# LEDSubMatrixHighDensity.net
KiCad netlist of a schematic drawn in EAGLE
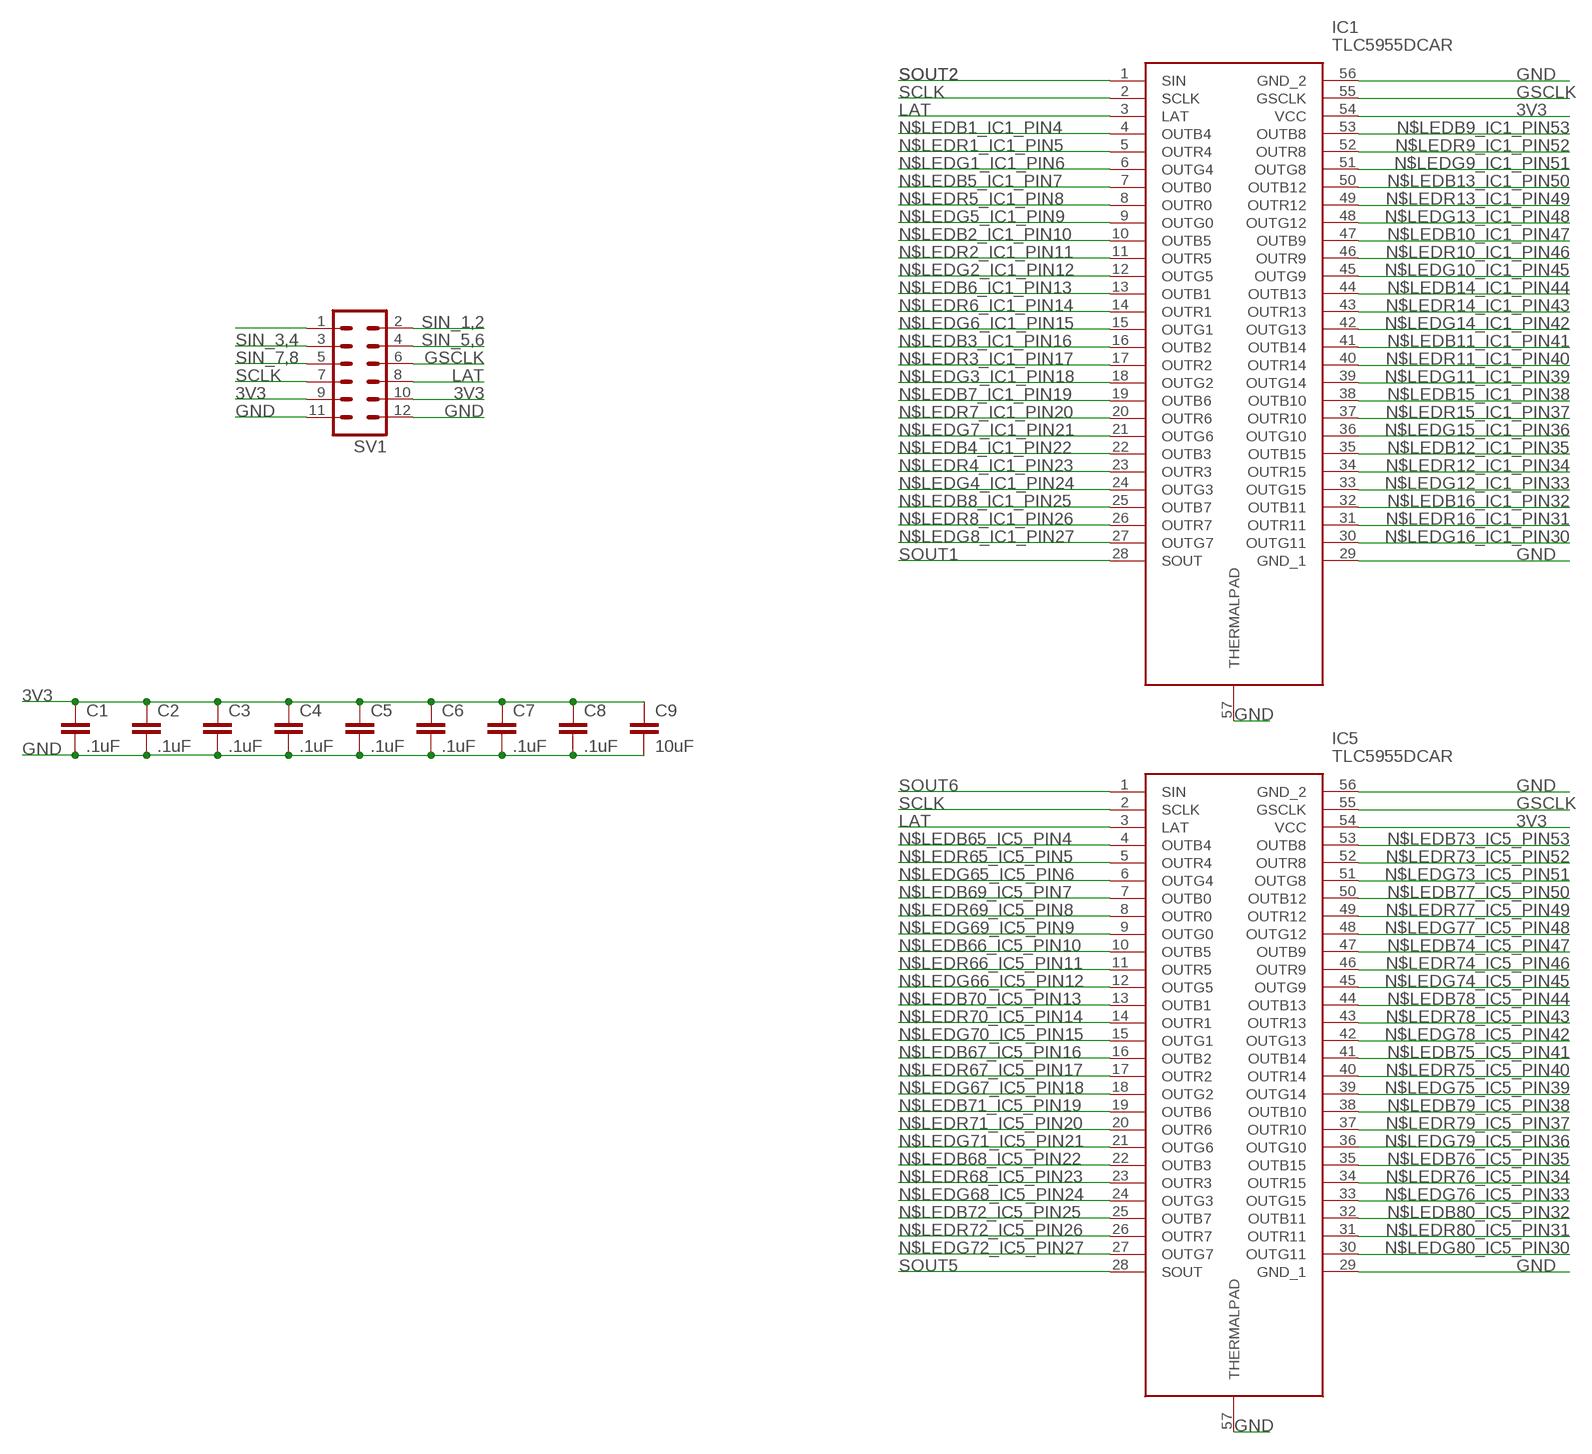
[diagram p0: schematic, sheet 1, part 1 of 3]
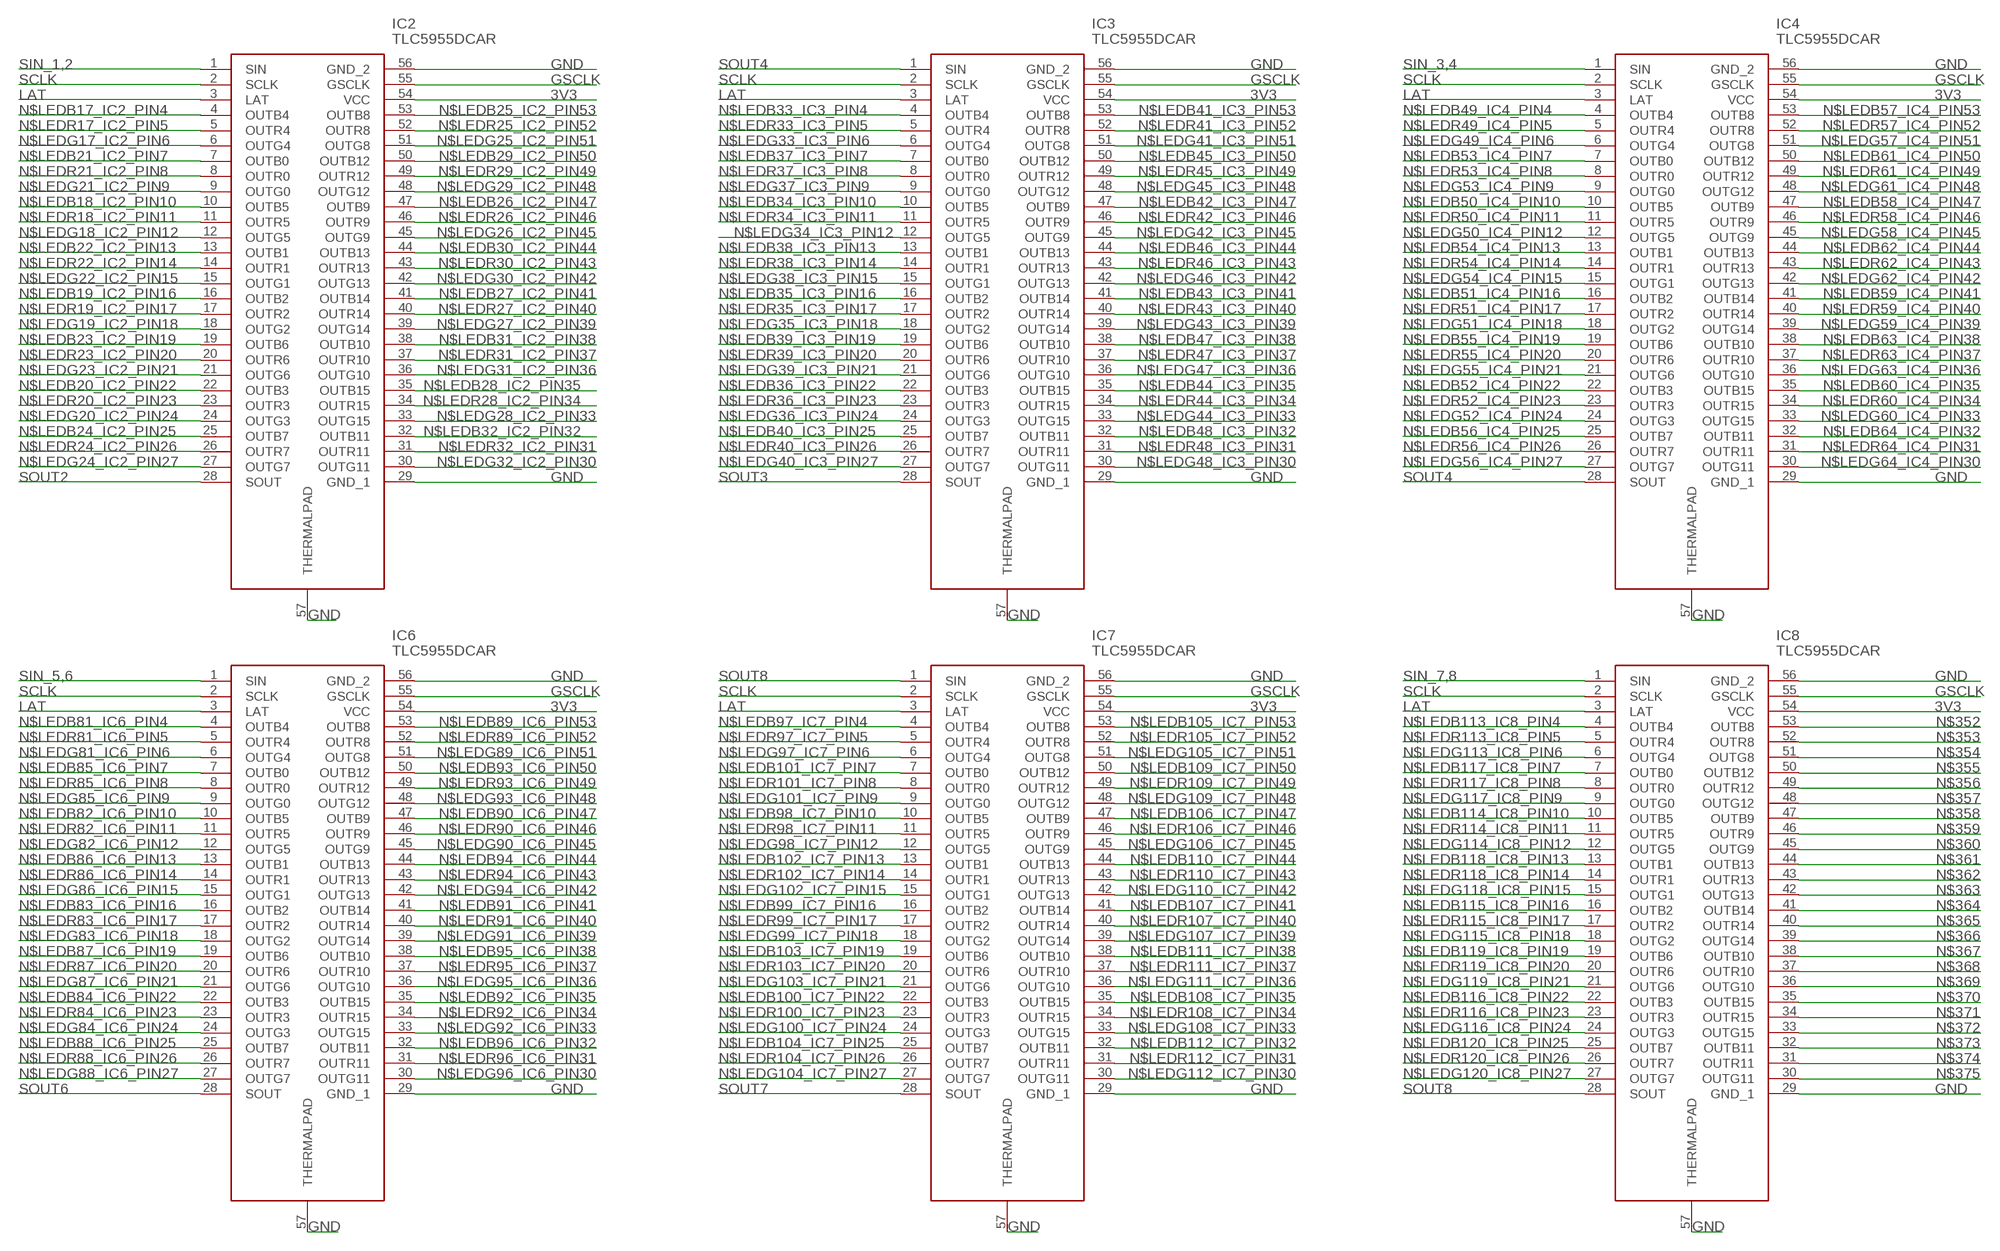
[diagram p1: schematic, sheet 1, part 2 of 3]
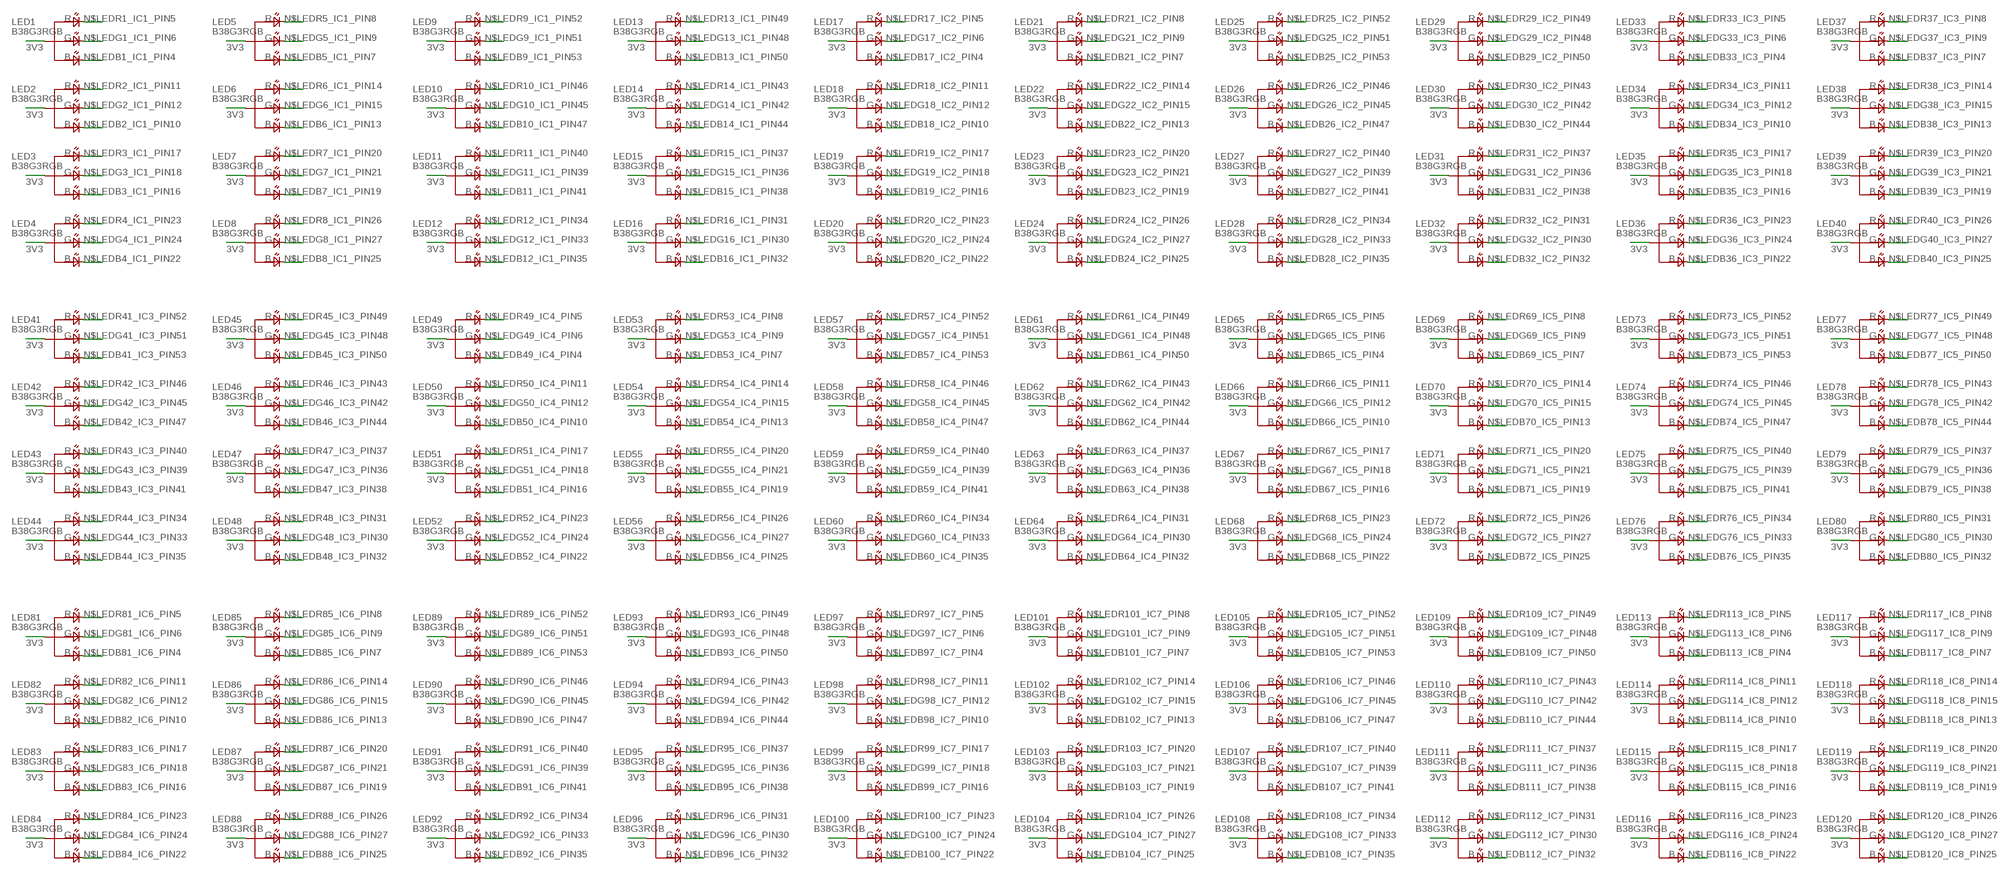
[diagram p2: schematic, sheet 1, part 3 of 3]

(export (version "E")
  (design (tool "Eeschema 10.0.6"))
  (components
    (comp (ref "C1")
      (value ".1uF")
      (footprint "eagle-import:C0603")
      (libsource (lib "eagle-import") (part "C-EUC0603"))
    )
    (comp (ref "C2")
      (value ".1uF")
      (footprint "eagle-import:C0603")
      (libsource (lib "eagle-import") (part "C-EUC0603"))
    )
    (comp (ref "C3")
      (value ".1uF")
      (footprint "eagle-import:C0603")
      (libsource (lib "eagle-import") (part "C-EUC0603"))
    )
    (comp (ref "C4")
      (value ".1uF")
      (footprint "eagle-import:C0603")
      (libsource (lib "eagle-import") (part "C-EUC0603"))
    )
    (comp (ref "C5")
      (value ".1uF")
      (footprint "eagle-import:C0603")
      (libsource (lib "eagle-import") (part "C-EUC0603"))
    )
    (comp (ref "C6")
      (value ".1uF")
      (footprint "eagle-import:C0603")
      (libsource (lib "eagle-import") (part "C-EUC0603"))
    )
    (comp (ref "C7")
      (value ".1uF")
      (footprint "eagle-import:C0603")
      (libsource (lib "eagle-import") (part "C-EUC0603"))
    )
    (comp (ref "C8")
      (value ".1uF")
      (footprint "eagle-import:C0603")
      (libsource (lib "eagle-import") (part "C-EUC0603"))
    )
    (comp (ref "C9")
      (value "10uF")
      (footprint "eagle-import:C0805")
      (libsource (lib "eagle-import") (part "C-EUC0805"))
    )
    (comp (ref "IC1")
      (value "TLC5955DCAR")
      (footprint "eagle-import:SOP50P810X120-57N")
      (fields (field (name "MOUSER_PART_NUMBER") "595-TLC5955DCAR"))
      (libsource (lib "eagle-import") (part "TLC5955DCAR"))
    )
    (comp (ref "IC2")
      (value "TLC5955DCAR")
      (footprint "eagle-import:SOP50P810X120-57N")
      (fields (field (name "MOUSER_PART_NUMBER") "595-TLC5955DCAR"))
      (libsource (lib "eagle-import") (part "TLC5955DCAR"))
    )
    (comp (ref "IC3")
      (value "TLC5955DCAR")
      (footprint "eagle-import:SOP50P810X120-57N")
      (fields (field (name "MOUSER_PART_NUMBER") "595-TLC5955DCAR"))
      (libsource (lib "eagle-import") (part "TLC5955DCAR"))
    )
    (comp (ref "IC4")
      (value "TLC5955DCAR")
      (footprint "eagle-import:SOP50P810X120-57N")
      (fields (field (name "MOUSER_PART_NUMBER") "595-TLC5955DCAR"))
      (libsource (lib "eagle-import") (part "TLC5955DCAR"))
    )
    (comp (ref "IC5")
      (value "TLC5955DCAR")
      (footprint "eagle-import:SOP50P810X120-57N")
      (fields (field (name "MOUSER_PART_NUMBER") "595-TLC5955DCAR"))
      (libsource (lib "eagle-import") (part "TLC5955DCAR"))
    )
    (comp (ref "IC6")
      (value "TLC5955DCAR")
      (footprint "eagle-import:SOP50P810X120-57N")
      (fields (field (name "MOUSER_PART_NUMBER") "595-TLC5955DCAR"))
      (libsource (lib "eagle-import") (part "TLC5955DCAR"))
    )
    (comp (ref "IC7")
      (value "TLC5955DCAR")
      (footprint "eagle-import:SOP50P810X120-57N")
      (fields (field (name "MOUSER_PART_NUMBER") "595-TLC5955DCAR"))
      (libsource (lib "eagle-import") (part "TLC5955DCAR"))
    )
    (comp (ref "IC8")
      (value "TLC5955DCAR")
      (footprint "eagle-import:SOP50P810X120-57N")
      (fields (field (name "MOUSER_PART_NUMBER") "595-TLC5955DCAR"))
      (libsource (lib "eagle-import") (part "TLC5955DCAR"))
    )
    (comp (ref "LED1")
      (value "B38G3RGB")
      (footprint "eagle-import:B38G3RGB")
      (fields
        (field (name "ARROW_PART_NUMBER") "SML-LX0606IGC-TR")
        (field (name "MOUSER_PART_NUMBER") "696-SML-0606IGCTR")
      )
      (libsource (lib "eagle-import") (part "B38G3RGB"))
    )
    (comp (ref "LED2")
      (value "B38G3RGB")
      (footprint "eagle-import:B38G3RGB")
      (fields
        (field (name "ARROW_PART_NUMBER") "SML-LX0606IGC-TR")
        (field (name "MOUSER_PART_NUMBER") "696-SML-0606IGCTR")
      )
      (libsource (lib "eagle-import") (part "B38G3RGB"))
    )
    (comp (ref "LED3")
      (value "B38G3RGB")
      (footprint "eagle-import:B38G3RGB")
      (fields
        (field (name "ARROW_PART_NUMBER") "SML-LX0606IGC-TR")
        (field (name "MOUSER_PART_NUMBER") "696-SML-0606IGCTR")
      )
      (libsource (lib "eagle-import") (part "B38G3RGB"))
    )
    (comp (ref "LED4")
      (value "B38G3RGB")
      (footprint "eagle-import:B38G3RGB")
      (fields
        (field (name "ARROW_PART_NUMBER") "SML-LX0606IGC-TR")
        (field (name "MOUSER_PART_NUMBER") "696-SML-0606IGCTR")
      )
      (libsource (lib "eagle-import") (part "B38G3RGB"))
    )
    (comp (ref "LED5")
      (value "B38G3RGB")
      (footprint "eagle-import:B38G3RGB")
      (fields
        (field (name "ARROW_PART_NUMBER") "SML-LX0606IGC-TR")
        (field (name "MOUSER_PART_NUMBER") "696-SML-0606IGCTR")
      )
      (libsource (lib "eagle-import") (part "B38G3RGB"))
    )
    (comp (ref "LED6")
      (value "B38G3RGB")
      (footprint "eagle-import:B38G3RGB")
      (fields
        (field (name "ARROW_PART_NUMBER") "SML-LX0606IGC-TR")
        (field (name "MOUSER_PART_NUMBER") "696-SML-0606IGCTR")
      )
      (libsource (lib "eagle-import") (part "B38G3RGB"))
    )
    (comp (ref "LED7")
      (value "B38G3RGB")
      (footprint "eagle-import:B38G3RGB")
      (fields
        (field (name "ARROW_PART_NUMBER") "SML-LX0606IGC-TR")
        (field (name "MOUSER_PART_NUMBER") "696-SML-0606IGCTR")
      )
      (libsource (lib "eagle-import") (part "B38G3RGB"))
    )
    (comp (ref "LED8")
      (value "B38G3RGB")
      (footprint "eagle-import:B38G3RGB")
      (fields
        (field (name "ARROW_PART_NUMBER") "SML-LX0606IGC-TR")
        (field (name "MOUSER_PART_NUMBER") "696-SML-0606IGCTR")
      )
      (libsource (lib "eagle-import") (part "B38G3RGB"))
    )
    (comp (ref "LED9")
      (value "B38G3RGB")
      (footprint "eagle-import:B38G3RGB")
      (fields
        (field (name "ARROW_PART_NUMBER") "SML-LX0606IGC-TR")
        (field (name "MOUSER_PART_NUMBER") "696-SML-0606IGCTR")
      )
      (libsource (lib "eagle-import") (part "B38G3RGB"))
    )
    (comp (ref "LED10")
      (value "B38G3RGB")
      (footprint "eagle-import:B38G3RGB")
      (fields
        (field (name "ARROW_PART_NUMBER") "SML-LX0606IGC-TR")
        (field (name "MOUSER_PART_NUMBER") "696-SML-0606IGCTR")
      )
      (libsource (lib "eagle-import") (part "B38G3RGB"))
    )
    (comp (ref "LED11")
      (value "B38G3RGB")
      (footprint "eagle-import:B38G3RGB")
      (fields
        (field (name "ARROW_PART_NUMBER") "SML-LX0606IGC-TR")
        (field (name "MOUSER_PART_NUMBER") "696-SML-0606IGCTR")
      )
      (libsource (lib "eagle-import") (part "B38G3RGB"))
    )
    (comp (ref "LED12")
      (value "B38G3RGB")
      (footprint "eagle-import:B38G3RGB")
      (fields
        (field (name "ARROW_PART_NUMBER") "SML-LX0606IGC-TR")
        (field (name "MOUSER_PART_NUMBER") "696-SML-0606IGCTR")
      )
      (libsource (lib "eagle-import") (part "B38G3RGB"))
    )
    (comp (ref "LED13")
      (value "B38G3RGB")
      (footprint "eagle-import:B38G3RGB")
      (fields
        (field (name "ARROW_PART_NUMBER") "SML-LX0606IGC-TR")
        (field (name "MOUSER_PART_NUMBER") "696-SML-0606IGCTR")
      )
      (libsource (lib "eagle-import") (part "B38G3RGB"))
    )
    (comp (ref "LED14")
      (value "B38G3RGB")
      (footprint "eagle-import:B38G3RGB")
      (fields
        (field (name "ARROW_PART_NUMBER") "SML-LX0606IGC-TR")
        (field (name "MOUSER_PART_NUMBER") "696-SML-0606IGCTR")
      )
      (libsource (lib "eagle-import") (part "B38G3RGB"))
    )
    (comp (ref "LED15")
      (value "B38G3RGB")
      (footprint "eagle-import:B38G3RGB")
      (fields
        (field (name "ARROW_PART_NUMBER") "SML-LX0606IGC-TR")
        (field (name "MOUSER_PART_NUMBER") "696-SML-0606IGCTR")
      )
      (libsource (lib "eagle-import") (part "B38G3RGB"))
    )
    (comp (ref "LED16")
      (value "B38G3RGB")
      (footprint "eagle-import:B38G3RGB")
      (fields
        (field (name "ARROW_PART_NUMBER") "SML-LX0606IGC-TR")
        (field (name "MOUSER_PART_NUMBER") "696-SML-0606IGCTR")
      )
      (libsource (lib "eagle-import") (part "B38G3RGB"))
    )
    (comp (ref "LED17")
      (value "B38G3RGB")
      (footprint "eagle-import:B38G3RGB")
      (fields
        (field (name "ARROW_PART_NUMBER") "SML-LX0606IGC-TR")
        (field (name "MOUSER_PART_NUMBER") "696-SML-0606IGCTR")
      )
      (libsource (lib "eagle-import") (part "B38G3RGB"))
    )
    (comp (ref "LED18")
      (value "B38G3RGB")
      (footprint "eagle-import:B38G3RGB")
      (fields
        (field (name "ARROW_PART_NUMBER") "SML-LX0606IGC-TR")
        (field (name "MOUSER_PART_NUMBER") "696-SML-0606IGCTR")
      )
      (libsource (lib "eagle-import") (part "B38G3RGB"))
    )
    (comp (ref "LED19")
      (value "B38G3RGB")
      (footprint "eagle-import:B38G3RGB")
      (fields
        (field (name "ARROW_PART_NUMBER") "SML-LX0606IGC-TR")
        (field (name "MOUSER_PART_NUMBER") "696-SML-0606IGCTR")
      )
      (libsource (lib "eagle-import") (part "B38G3RGB"))
    )
    (comp (ref "LED20")
      (value "B38G3RGB")
      (footprint "eagle-import:B38G3RGB")
      (fields
        (field (name "ARROW_PART_NUMBER") "SML-LX0606IGC-TR")
        (field (name "MOUSER_PART_NUMBER") "696-SML-0606IGCTR")
      )
      (libsource (lib "eagle-import") (part "B38G3RGB"))
    )
    (comp (ref "LED21")
      (value "B38G3RGB")
      (footprint "eagle-import:B38G3RGB")
      (fields
        (field (name "ARROW_PART_NUMBER") "SML-LX0606IGC-TR")
        (field (name "MOUSER_PART_NUMBER") "696-SML-0606IGCTR")
      )
      (libsource (lib "eagle-import") (part "B38G3RGB"))
    )
    (comp (ref "LED22")
      (value "B38G3RGB")
      (footprint "eagle-import:B38G3RGB")
      (fields
        (field (name "ARROW_PART_NUMBER") "SML-LX0606IGC-TR")
        (field (name "MOUSER_PART_NUMBER") "696-SML-0606IGCTR")
      )
      (libsource (lib "eagle-import") (part "B38G3RGB"))
    )
    (comp (ref "LED23")
      (value "B38G3RGB")
      (footprint "eagle-import:B38G3RGB")
      (fields
        (field (name "ARROW_PART_NUMBER") "SML-LX0606IGC-TR")
        (field (name "MOUSER_PART_NUMBER") "696-SML-0606IGCTR")
      )
      (libsource (lib "eagle-import") (part "B38G3RGB"))
    )
    (comp (ref "LED24")
      (value "B38G3RGB")
      (footprint "eagle-import:B38G3RGB")
      (fields
        (field (name "ARROW_PART_NUMBER") "SML-LX0606IGC-TR")
        (field (name "MOUSER_PART_NUMBER") "696-SML-0606IGCTR")
      )
      (libsource (lib "eagle-import") (part "B38G3RGB"))
    )
    (comp (ref "LED25")
      (value "B38G3RGB")
      (footprint "eagle-import:B38G3RGB")
      (fields
        (field (name "ARROW_PART_NUMBER") "SML-LX0606IGC-TR")
        (field (name "MOUSER_PART_NUMBER") "696-SML-0606IGCTR")
      )
      (libsource (lib "eagle-import") (part "B38G3RGB"))
    )
    (comp (ref "LED26")
      (value "B38G3RGB")
      (footprint "eagle-import:B38G3RGB")
      (fields
        (field (name "ARROW_PART_NUMBER") "SML-LX0606IGC-TR")
        (field (name "MOUSER_PART_NUMBER") "696-SML-0606IGCTR")
      )
      (libsource (lib "eagle-import") (part "B38G3RGB"))
    )
    (comp (ref "LED27")
      (value "B38G3RGB")
      (footprint "eagle-import:B38G3RGB")
      (fields
        (field (name "ARROW_PART_NUMBER") "SML-LX0606IGC-TR")
        (field (name "MOUSER_PART_NUMBER") "696-SML-0606IGCTR")
      )
      (libsource (lib "eagle-import") (part "B38G3RGB"))
    )
    (comp (ref "LED28")
      (value "B38G3RGB")
      (footprint "eagle-import:B38G3RGB")
      (fields
        (field (name "ARROW_PART_NUMBER") "SML-LX0606IGC-TR")
        (field (name "MOUSER_PART_NUMBER") "696-SML-0606IGCTR")
      )
      (libsource (lib "eagle-import") (part "B38G3RGB"))
    )
    (comp (ref "LED29")
      (value "B38G3RGB")
      (footprint "eagle-import:B38G3RGB")
      (fields
        (field (name "ARROW_PART_NUMBER") "SML-LX0606IGC-TR")
        (field (name "MOUSER_PART_NUMBER") "696-SML-0606IGCTR")
      )
      (libsource (lib "eagle-import") (part "B38G3RGB"))
    )
    (comp (ref "LED30")
      (value "B38G3RGB")
      (footprint "eagle-import:B38G3RGB")
      (fields
        (field (name "ARROW_PART_NUMBER") "SML-LX0606IGC-TR")
        (field (name "MOUSER_PART_NUMBER") "696-SML-0606IGCTR")
      )
      (libsource (lib "eagle-import") (part "B38G3RGB"))
    )
    (comp (ref "LED31")
      (value "B38G3RGB")
      (footprint "eagle-import:B38G3RGB")
      (fields
        (field (name "ARROW_PART_NUMBER") "SML-LX0606IGC-TR")
        (field (name "MOUSER_PART_NUMBER") "696-SML-0606IGCTR")
      )
      (libsource (lib "eagle-import") (part "B38G3RGB"))
    )
    (comp (ref "LED32")
      (value "B38G3RGB")
      (footprint "eagle-import:B38G3RGB")
      (fields
        (field (name "ARROW_PART_NUMBER") "SML-LX0606IGC-TR")
        (field (name "MOUSER_PART_NUMBER") "696-SML-0606IGCTR")
      )
      (libsource (lib "eagle-import") (part "B38G3RGB"))
    )
    (comp (ref "LED33")
      (value "B38G3RGB")
      (footprint "eagle-import:B38G3RGB")
      (fields
        (field (name "ARROW_PART_NUMBER") "SML-LX0606IGC-TR")
        (field (name "MOUSER_PART_NUMBER") "696-SML-0606IGCTR")
      )
      (libsource (lib "eagle-import") (part "B38G3RGB"))
    )
    (comp (ref "LED34")
      (value "B38G3RGB")
      (footprint "eagle-import:B38G3RGB")
      (fields
        (field (name "ARROW_PART_NUMBER") "SML-LX0606IGC-TR")
        (field (name "MOUSER_PART_NUMBER") "696-SML-0606IGCTR")
      )
      (libsource (lib "eagle-import") (part "B38G3RGB"))
    )
    (comp (ref "LED35")
      (value "B38G3RGB")
      (footprint "eagle-import:B38G3RGB")
      (fields
        (field (name "ARROW_PART_NUMBER") "SML-LX0606IGC-TR")
        (field (name "MOUSER_PART_NUMBER") "696-SML-0606IGCTR")
      )
      (libsource (lib "eagle-import") (part "B38G3RGB"))
    )
    (comp (ref "LED36")
      (value "B38G3RGB")
      (footprint "eagle-import:B38G3RGB")
      (fields
        (field (name "ARROW_PART_NUMBER") "SML-LX0606IGC-TR")
        (field (name "MOUSER_PART_NUMBER") "696-SML-0606IGCTR")
      )
      (libsource (lib "eagle-import") (part "B38G3RGB"))
    )
    (comp (ref "LED37")
      (value "B38G3RGB")
      (footprint "eagle-import:B38G3RGB")
      (fields
        (field (name "ARROW_PART_NUMBER") "SML-LX0606IGC-TR")
        (field (name "MOUSER_PART_NUMBER") "696-SML-0606IGCTR")
      )
      (libsource (lib "eagle-import") (part "B38G3RGB"))
    )
    (comp (ref "LED38")
      (value "B38G3RGB")
      (footprint "eagle-import:B38G3RGB")
      (fields
        (field (name "ARROW_PART_NUMBER") "SML-LX0606IGC-TR")
        (field (name "MOUSER_PART_NUMBER") "696-SML-0606IGCTR")
      )
      (libsource (lib "eagle-import") (part "B38G3RGB"))
    )
    (comp (ref "LED39")
      (value "B38G3RGB")
      (footprint "eagle-import:B38G3RGB")
      (fields
        (field (name "ARROW_PART_NUMBER") "SML-LX0606IGC-TR")
        (field (name "MOUSER_PART_NUMBER") "696-SML-0606IGCTR")
      )
      (libsource (lib "eagle-import") (part "B38G3RGB"))
    )
    (comp (ref "LED40")
      (value "B38G3RGB")
      (footprint "eagle-import:B38G3RGB")
      (fields
        (field (name "ARROW_PART_NUMBER") "SML-LX0606IGC-TR")
        (field (name "MOUSER_PART_NUMBER") "696-SML-0606IGCTR")
      )
      (libsource (lib "eagle-import") (part "B38G3RGB"))
    )
    (comp (ref "LED41")
      (value "B38G3RGB")
      (footprint "eagle-import:B38G3RGB")
      (fields
        (field (name "ARROW_PART_NUMBER") "SML-LX0606IGC-TR")
        (field (name "MOUSER_PART_NUMBER") "696-SML-0606IGCTR")
      )
      (libsource (lib "eagle-import") (part "B38G3RGB"))
    )
    (comp (ref "LED42")
      (value "B38G3RGB")
      (footprint "eagle-import:B38G3RGB")
      (fields
        (field (name "ARROW_PART_NUMBER") "SML-LX0606IGC-TR")
        (field (name "MOUSER_PART_NUMBER") "696-SML-0606IGCTR")
      )
      (libsource (lib "eagle-import") (part "B38G3RGB"))
    )
    (comp (ref "LED43")
      (value "B38G3RGB")
      (footprint "eagle-import:B38G3RGB")
      (fields
        (field (name "ARROW_PART_NUMBER") "SML-LX0606IGC-TR")
        (field (name "MOUSER_PART_NUMBER") "696-SML-0606IGCTR")
      )
      (libsource (lib "eagle-import") (part "B38G3RGB"))
    )
    (comp (ref "LED44")
      (value "B38G3RGB")
      (footprint "eagle-import:B38G3RGB")
      (fields
        (field (name "ARROW_PART_NUMBER") "SML-LX0606IGC-TR")
        (field (name "MOUSER_PART_NUMBER") "696-SML-0606IGCTR")
      )
      (libsource (lib "eagle-import") (part "B38G3RGB"))
    )
    (comp (ref "LED45")
      (value "B38G3RGB")
      (footprint "eagle-import:B38G3RGB")
      (fields
        (field (name "ARROW_PART_NUMBER") "SML-LX0606IGC-TR")
        (field (name "MOUSER_PART_NUMBER") "696-SML-0606IGCTR")
      )
      (libsource (lib "eagle-import") (part "B38G3RGB"))
    )
    (comp (ref "LED46")
      (value "B38G3RGB")
      (footprint "eagle-import:B38G3RGB")
      (fields
        (field (name "ARROW_PART_NUMBER") "SML-LX0606IGC-TR")
        (field (name "MOUSER_PART_NUMBER") "696-SML-0606IGCTR")
      )
      (libsource (lib "eagle-import") (part "B38G3RGB"))
    )
    (comp (ref "LED47")
      (value "B38G3RGB")
      (footprint "eagle-import:B38G3RGB")
      (fields
        (field (name "ARROW_PART_NUMBER") "SML-LX0606IGC-TR")
        (field (name "MOUSER_PART_NUMBER") "696-SML-0606IGCTR")
      )
      (libsource (lib "eagle-import") (part "B38G3RGB"))
    )
    (comp (ref "LED48")
      (value "B38G3RGB")
      (footprint "eagle-import:B38G3RGB")
      (fields
        (field (name "ARROW_PART_NUMBER") "SML-LX0606IGC-TR")
        (field (name "MOUSER_PART_NUMBER") "696-SML-0606IGCTR")
      )
      (libsource (lib "eagle-import") (part "B38G3RGB"))
    )
    (comp (ref "LED49")
      (value "B38G3RGB")
      (footprint "eagle-import:B38G3RGB")
      (fields
        (field (name "ARROW_PART_NUMBER") "SML-LX0606IGC-TR")
        (field (name "MOUSER_PART_NUMBER") "696-SML-0606IGCTR")
      )
      (libsource (lib "eagle-import") (part "B38G3RGB"))
    )
    (comp (ref "LED50")
      (value "B38G3RGB")
      (footprint "eagle-import:B38G3RGB")
      (fields
        (field (name "ARROW_PART_NUMBER") "SML-LX0606IGC-TR")
        (field (name "MOUSER_PART_NUMBER") "696-SML-0606IGCTR")
      )
      (libsource (lib "eagle-import") (part "B38G3RGB"))
    )
    (comp (ref "LED51")
      (value "B38G3RGB")
      (footprint "eagle-import:B38G3RGB")
      (fields
        (field (name "ARROW_PART_NUMBER") "SML-LX0606IGC-TR")
        (field (name "MOUSER_PART_NUMBER") "696-SML-0606IGCTR")
      )
      (libsource (lib "eagle-import") (part "B38G3RGB"))
    )
    (comp (ref "LED52")
      (value "B38G3RGB")
      (footprint "eagle-import:B38G3RGB")
      (fields
        (field (name "ARROW_PART_NUMBER") "SML-LX0606IGC-TR")
        (field (name "MOUSER_PART_NUMBER") "696-SML-0606IGCTR")
      )
      (libsource (lib "eagle-import") (part "B38G3RGB"))
    )
    (comp (ref "LED53")
      (value "B38G3RGB")
      (footprint "eagle-import:B38G3RGB")
      (fields
        (field (name "ARROW_PART_NUMBER") "SML-LX0606IGC-TR")
        (field (name "MOUSER_PART_NUMBER") "696-SML-0606IGCTR")
      )
      (libsource (lib "eagle-import") (part "B38G3RGB"))
    )
    (comp (ref "LED54")
      (value "B38G3RGB")
      (footprint "eagle-import:B38G3RGB")
      (fields
        (field (name "ARROW_PART_NUMBER") "SML-LX0606IGC-TR")
        (field (name "MOUSER_PART_NUMBER") "696-SML-0606IGCTR")
      )
      (libsource (lib "eagle-import") (part "B38G3RGB"))
    )
    (comp (ref "LED55")
      (value "B38G3RGB")
      (footprint "eagle-import:B38G3RGB")
      (fields
        (field (name "ARROW_PART_NUMBER") "SML-LX0606IGC-TR")
        (field (name "MOUSER_PART_NUMBER") "696-SML-0606IGCTR")
      )
      (libsource (lib "eagle-import") (part "B38G3RGB"))
    )
    (comp (ref "LED56")
      (value "B38G3RGB")
      (footprint "eagle-import:B38G3RGB")
      (fields
        (field (name "ARROW_PART_NUMBER") "SML-LX0606IGC-TR")
        (field (name "MOUSER_PART_NUMBER") "696-SML-0606IGCTR")
      )
      (libsource (lib "eagle-import") (part "B38G3RGB"))
    )
    (comp (ref "LED57")
      (value "B38G3RGB")
      (footprint "eagle-import:B38G3RGB")
      (fields
        (field (name "ARROW_PART_NUMBER") "SML-LX0606IGC-TR")
        (field (name "MOUSER_PART_NUMBER") "696-SML-0606IGCTR")
      )
      (libsource (lib "eagle-import") (part "B38G3RGB"))
    )
    (comp (ref "LED58")
      (value "B38G3RGB")
      (footprint "eagle-import:B38G3RGB")
      (fields
        (field (name "ARROW_PART_NUMBER") "SML-LX0606IGC-TR")
        (field (name "MOUSER_PART_NUMBER") "696-SML-0606IGCTR")
      )
      (libsource (lib "eagle-import") (part "B38G3RGB"))
    )
    (comp (ref "LED59")
      (value "B38G3RGB")
      (footprint "eagle-import:B38G3RGB")
      (fields
        (field (name "ARROW_PART_NUMBER") "SML-LX0606IGC-TR")
        (field (name "MOUSER_PART_NUMBER") "696-SML-0606IGCTR")
      )
      (libsource (lib "eagle-import") (part "B38G3RGB"))
    )
    (comp (ref "LED60")
      (value "B38G3RGB")
      (footprint "eagle-import:B38G3RGB")
      (fields
        (field (name "ARROW_PART_NUMBER") "SML-LX0606IGC-TR")
        (field (name "MOUSER_PART_NUMBER") "696-SML-0606IGCTR")
      )
      (libsource (lib "eagle-import") (part "B38G3RGB"))
    )
    (comp (ref "LED61")
      (value "B38G3RGB")
      (footprint "eagle-import:B38G3RGB")
      (fields
        (field (name "ARROW_PART_NUMBER") "SML-LX0606IGC-TR")
        (field (name "MOUSER_PART_NUMBER") "696-SML-0606IGCTR")
      )
      (libsource (lib "eagle-import") (part "B38G3RGB"))
    )
    (comp (ref "LED62")
      (value "B38G3RGB")
      (footprint "eagle-import:B38G3RGB")
      (fields
        (field (name "ARROW_PART_NUMBER") "SML-LX0606IGC-TR")
        (field (name "MOUSER_PART_NUMBER") "696-SML-0606IGCTR")
      )
      (libsource (lib "eagle-import") (part "B38G3RGB"))
    )
    (comp (ref "LED63")
      (value "B38G3RGB")
      (footprint "eagle-import:B38G3RGB")
      (fields
        (field (name "ARROW_PART_NUMBER") "SML-LX0606IGC-TR")
        (field (name "MOUSER_PART_NUMBER") "696-SML-0606IGCTR")
      )
      (libsource (lib "eagle-import") (part "B38G3RGB"))
    )
    (comp (ref "LED64")
      (value "B38G3RGB")
      (footprint "eagle-import:B38G3RGB")
      (fields
        (field (name "ARROW_PART_NUMBER") "SML-LX0606IGC-TR")
        (field (name "MOUSER_PART_NUMBER") "696-SML-0606IGCTR")
      )
      (libsource (lib "eagle-import") (part "B38G3RGB"))
    )
    (comp (ref "LED65")
      (value "B38G3RGB")
      (footprint "eagle-import:B38G3RGB")
      (fields
        (field (name "ARROW_PART_NUMBER") "SML-LX0606IGC-TR")
        (field (name "MOUSER_PART_NUMBER") "696-SML-0606IGCTR")
      )
      (libsource (lib "eagle-import") (part "B38G3RGB"))
    )
    (comp (ref "LED66")
      (value "B38G3RGB")
      (footprint "eagle-import:B38G3RGB")
      (fields
        (field (name "ARROW_PART_NUMBER") "SML-LX0606IGC-TR")
        (field (name "MOUSER_PART_NUMBER") "696-SML-0606IGCTR")
      )
      (libsource (lib "eagle-import") (part "B38G3RGB"))
    )
    (comp (ref "LED67")
      (value "B38G3RGB")
      (footprint "eagle-import:B38G3RGB")
      (fields
        (field (name "ARROW_PART_NUMBER") "SML-LX0606IGC-TR")
        (field (name "MOUSER_PART_NUMBER") "696-SML-0606IGCTR")
      )
      (libsource (lib "eagle-import") (part "B38G3RGB"))
    )
    (comp (ref "LED68")
      (value "B38G3RGB")
      (footprint "eagle-import:B38G3RGB")
      (fields
        (field (name "ARROW_PART_NUMBER") "SML-LX0606IGC-TR")
        (field (name "MOUSER_PART_NUMBER") "696-SML-0606IGCTR")
      )
      (libsource (lib "eagle-import") (part "B38G3RGB"))
    )
    (comp (ref "LED69")
      (value "B38G3RGB")
      (footprint "eagle-import:B38G3RGB")
      (fields
        (field (name "ARROW_PART_NUMBER") "SML-LX0606IGC-TR")
        (field (name "MOUSER_PART_NUMBER") "696-SML-0606IGCTR")
      )
      (libsource (lib "eagle-import") (part "B38G3RGB"))
    )
    (comp (ref "LED70")
      (value "B38G3RGB")
      (footprint "eagle-import:B38G3RGB")
      (fields
        (field (name "ARROW_PART_NUMBER") "SML-LX0606IGC-TR")
        (field (name "MOUSER_PART_NUMBER") "696-SML-0606IGCTR")
      )
      (libsource (lib "eagle-import") (part "B38G3RGB"))
    )
    (comp (ref "LED71")
      (value "B38G3RGB")
      (footprint "eagle-import:B38G3RGB")
      (fields
        (field (name "ARROW_PART_NUMBER") "SML-LX0606IGC-TR")
        (field (name "MOUSER_PART_NUMBER") "696-SML-0606IGCTR")
      )
      (libsource (lib "eagle-import") (part "B38G3RGB"))
    )
    (comp (ref "LED72")
      (value "B38G3RGB")
      (footprint "eagle-import:B38G3RGB")
      (fields
        (field (name "ARROW_PART_NUMBER") "SML-LX0606IGC-TR")
        (field (name "MOUSER_PART_NUMBER") "696-SML-0606IGCTR")
      )
      (libsource (lib "eagle-import") (part "B38G3RGB"))
    )
    (comp (ref "LED73")
      (value "B38G3RGB")
      (footprint "eagle-import:B38G3RGB")
      (fields
        (field (name "ARROW_PART_NUMBER") "SML-LX0606IGC-TR")
        (field (name "MOUSER_PART_NUMBER") "696-SML-0606IGCTR")
      )
      (libsource (lib "eagle-import") (part "B38G3RGB"))
    )
    (comp (ref "LED74")
      (value "B38G3RGB")
      (footprint "eagle-import:B38G3RGB")
      (fields
        (field (name "ARROW_PART_NUMBER") "SML-LX0606IGC-TR")
        (field (name "MOUSER_PART_NUMBER") "696-SML-0606IGCTR")
      )
      (libsource (lib "eagle-import") (part "B38G3RGB"))
    )
    (comp (ref "LED75")
      (value "B38G3RGB")
      (footprint "eagle-import:B38G3RGB")
      (fields
        (field (name "ARROW_PART_NUMBER") "SML-LX0606IGC-TR")
        (field (name "MOUSER_PART_NUMBER") "696-SML-0606IGCTR")
      )
      (libsource (lib "eagle-import") (part "B38G3RGB"))
    )
    (comp (ref "LED76")
      (value "B38G3RGB")
      (footprint "eagle-import:B38G3RGB")
      (fields
        (field (name "ARROW_PART_NUMBER") "SML-LX0606IGC-TR")
        (field (name "MOUSER_PART_NUMBER") "696-SML-0606IGCTR")
      )
      (libsource (lib "eagle-import") (part "B38G3RGB"))
    )
    (comp (ref "LED77")
      (value "B38G3RGB")
      (footprint "eagle-import:B38G3RGB")
      (fields
        (field (name "ARROW_PART_NUMBER") "SML-LX0606IGC-TR")
        (field (name "MOUSER_PART_NUMBER") "696-SML-0606IGCTR")
      )
      (libsource (lib "eagle-import") (part "B38G3RGB"))
    )
    (comp (ref "LED78")
      (value "B38G3RGB")
      (footprint "eagle-import:B38G3RGB")
      (fields
        (field (name "ARROW_PART_NUMBER") "SML-LX0606IGC-TR")
        (field (name "MOUSER_PART_NUMBER") "696-SML-0606IGCTR")
      )
      (libsource (lib "eagle-import") (part "B38G3RGB"))
    )
    (comp (ref "LED79")
      (value "B38G3RGB")
      (footprint "eagle-import:B38G3RGB")
      (fields
        (field (name "ARROW_PART_NUMBER") "SML-LX0606IGC-TR")
        (field (name "MOUSER_PART_NUMBER") "696-SML-0606IGCTR")
      )
      (libsource (lib "eagle-import") (part "B38G3RGB"))
    )
    (comp (ref "LED80")
      (value "B38G3RGB")
      (footprint "eagle-import:B38G3RGB")
      (fields
        (field (name "ARROW_PART_NUMBER") "SML-LX0606IGC-TR")
        (field (name "MOUSER_PART_NUMBER") "696-SML-0606IGCTR")
      )
      (libsource (lib "eagle-import") (part "B38G3RGB"))
    )
    (comp (ref "LED81")
      (value "B38G3RGB")
      (footprint "eagle-import:B38G3RGB")
      (fields
        (field (name "ARROW_PART_NUMBER") "SML-LX0606IGC-TR")
        (field (name "MOUSER_PART_NUMBER") "696-SML-0606IGCTR")
      )
      (libsource (lib "eagle-import") (part "B38G3RGB"))
    )
    (comp (ref "LED82")
      (value "B38G3RGB")
      (footprint "eagle-import:B38G3RGB")
      (fields
        (field (name "ARROW_PART_NUMBER") "SML-LX0606IGC-TR")
        (field (name "MOUSER_PART_NUMBER") "696-SML-0606IGCTR")
      )
      (libsource (lib "eagle-import") (part "B38G3RGB"))
    )
    (comp (ref "LED83")
      (value "B38G3RGB")
      (footprint "eagle-import:B38G3RGB")
      (fields
        (field (name "ARROW_PART_NUMBER") "SML-LX0606IGC-TR")
        (field (name "MOUSER_PART_NUMBER") "696-SML-0606IGCTR")
      )
      (libsource (lib "eagle-import") (part "B38G3RGB"))
    )
    (comp (ref "LED84")
      (value "B38G3RGB")
      (footprint "eagle-import:B38G3RGB")
      (fields
        (field (name "ARROW_PART_NUMBER") "SML-LX0606IGC-TR")
        (field (name "MOUSER_PART_NUMBER") "696-SML-0606IGCTR")
      )
      (libsource (lib "eagle-import") (part "B38G3RGB"))
    )
    (comp (ref "LED85")
      (value "B38G3RGB")
      (footprint "eagle-import:B38G3RGB")
      (fields
        (field (name "ARROW_PART_NUMBER") "SML-LX0606IGC-TR")
        (field (name "MOUSER_PART_NUMBER") "696-SML-0606IGCTR")
      )
      (libsource (lib "eagle-import") (part "B38G3RGB"))
    )
    (comp (ref "LED86")
      (value "B38G3RGB")
      (footprint "eagle-import:B38G3RGB")
      (fields
        (field (name "ARROW_PART_NUMBER") "SML-LX0606IGC-TR")
        (field (name "MOUSER_PART_NUMBER") "696-SML-0606IGCTR")
      )
      (libsource (lib "eagle-import") (part "B38G3RGB"))
    )
    (comp (ref "LED87")
      (value "B38G3RGB")
      (footprint "eagle-import:B38G3RGB")
      (fields
        (field (name "ARROW_PART_NUMBER") "SML-LX0606IGC-TR")
        (field (name "MOUSER_PART_NUMBER") "696-SML-0606IGCTR")
      )
      (libsource (lib "eagle-import") (part "B38G3RGB"))
    )
    (comp (ref "LED88")
      (value "B38G3RGB")
      (footprint "eagle-import:B38G3RGB")
      (fields
        (field (name "ARROW_PART_NUMBER") "SML-LX0606IGC-TR")
        (field (name "MOUSER_PART_NUMBER") "696-SML-0606IGCTR")
      )
      (libsource (lib "eagle-import") (part "B38G3RGB"))
    )
    (comp (ref "LED89")
      (value "B38G3RGB")
      (footprint "eagle-import:B38G3RGB")
      (fields
        (field (name "ARROW_PART_NUMBER") "SML-LX0606IGC-TR")
        (field (name "MOUSER_PART_NUMBER") "696-SML-0606IGCTR")
      )
      (libsource (lib "eagle-import") (part "B38G3RGB"))
    )
    (comp (ref "LED90")
      (value "B38G3RGB")
      (footprint "eagle-import:B38G3RGB")
      (fields
        (field (name "ARROW_PART_NUMBER") "SML-LX0606IGC-TR")
        (field (name "MOUSER_PART_NUMBER") "696-SML-0606IGCTR")
      )
      (libsource (lib "eagle-import") (part "B38G3RGB"))
    )
    (comp (ref "LED91")
      (value "B38G3RGB")
      (footprint "eagle-import:B38G3RGB")
      (fields
        (field (name "ARROW_PART_NUMBER") "SML-LX0606IGC-TR")
        (field (name "MOUSER_PART_NUMBER") "696-SML-0606IGCTR")
      )
      (libsource (lib "eagle-import") (part "B38G3RGB"))
    )
    (comp (ref "LED92")
      (value "B38G3RGB")
      (footprint "eagle-import:B38G3RGB")
      (fields
        (field (name "ARROW_PART_NUMBER") "SML-LX0606IGC-TR")
        (field (name "MOUSER_PART_NUMBER") "696-SML-0606IGCTR")
      )
      (libsource (lib "eagle-import") (part "B38G3RGB"))
    )
    (comp (ref "LED93")
      (value "B38G3RGB")
      (footprint "eagle-import:B38G3RGB")
      (fields
        (field (name "ARROW_PART_NUMBER") "SML-LX0606IGC-TR")
        (field (name "MOUSER_PART_NUMBER") "696-SML-0606IGCTR")
      )
      (libsource (lib "eagle-import") (part "B38G3RGB"))
    )
    (comp (ref "LED94")
      (value "B38G3RGB")
      (footprint "eagle-import:B38G3RGB")
      (fields
        (field (name "ARROW_PART_NUMBER") "SML-LX0606IGC-TR")
        (field (name "MOUSER_PART_NUMBER") "696-SML-0606IGCTR")
      )
      (libsource (lib "eagle-import") (part "B38G3RGB"))
    )
    (comp (ref "LED95")
      (value "B38G3RGB")
      (footprint "eagle-import:B38G3RGB")
      (fields
        (field (name "ARROW_PART_NUMBER") "SML-LX0606IGC-TR")
        (field (name "MOUSER_PART_NUMBER") "696-SML-0606IGCTR")
      )
      (libsource (lib "eagle-import") (part "B38G3RGB"))
    )
    (comp (ref "LED96")
      (value "B38G3RGB")
      (footprint "eagle-import:B38G3RGB")
      (fields
        (field (name "ARROW_PART_NUMBER") "SML-LX0606IGC-TR")
        (field (name "MOUSER_PART_NUMBER") "696-SML-0606IGCTR")
      )
      (libsource (lib "eagle-import") (part "B38G3RGB"))
    )
    (comp (ref "LED97")
      (value "B38G3RGB")
      (footprint "eagle-import:B38G3RGB")
      (fields
        (field (name "ARROW_PART_NUMBER") "SML-LX0606IGC-TR")
        (field (name "MOUSER_PART_NUMBER") "696-SML-0606IGCTR")
      )
      (libsource (lib "eagle-import") (part "B38G3RGB"))
    )
    (comp (ref "LED98")
      (value "B38G3RGB")
      (footprint "eagle-import:B38G3RGB")
      (fields
        (field (name "ARROW_PART_NUMBER") "SML-LX0606IGC-TR")
        (field (name "MOUSER_PART_NUMBER") "696-SML-0606IGCTR")
      )
      (libsource (lib "eagle-import") (part "B38G3RGB"))
    )
    (comp (ref "LED99")
      (value "B38G3RGB")
      (footprint "eagle-import:B38G3RGB")
      (fields
        (field (name "ARROW_PART_NUMBER") "SML-LX0606IGC-TR")
        (field (name "MOUSER_PART_NUMBER") "696-SML-0606IGCTR")
      )
      (libsource (lib "eagle-import") (part "B38G3RGB"))
    )
    (comp (ref "LED100")
      (value "B38G3RGB")
      (footprint "eagle-import:B38G3RGB")
      (fields
        (field (name "ARROW_PART_NUMBER") "SML-LX0606IGC-TR")
        (field (name "MOUSER_PART_NUMBER") "696-SML-0606IGCTR")
      )
      (libsource (lib "eagle-import") (part "B38G3RGB"))
    )
    (comp (ref "LED101")
      (value "B38G3RGB")
      (footprint "eagle-import:B38G3RGB")
      (fields
        (field (name "ARROW_PART_NUMBER") "SML-LX0606IGC-TR")
        (field (name "MOUSER_PART_NUMBER") "696-SML-0606IGCTR")
      )
      (libsource (lib "eagle-import") (part "B38G3RGB"))
    )
    (comp (ref "LED102")
      (value "B38G3RGB")
      (footprint "eagle-import:B38G3RGB")
      (fields
        (field (name "ARROW_PART_NUMBER") "SML-LX0606IGC-TR")
        (field (name "MOUSER_PART_NUMBER") "696-SML-0606IGCTR")
      )
      (libsource (lib "eagle-import") (part "B38G3RGB"))
    )
    (comp (ref "LED103")
      (value "B38G3RGB")
      (footprint "eagle-import:B38G3RGB")
      (fields
        (field (name "ARROW_PART_NUMBER") "SML-LX0606IGC-TR")
        (field (name "MOUSER_PART_NUMBER") "696-SML-0606IGCTR")
      )
      (libsource (lib "eagle-import") (part "B38G3RGB"))
    )
    (comp (ref "LED104")
      (value "B38G3RGB")
      (footprint "eagle-import:B38G3RGB")
      (fields
        (field (name "ARROW_PART_NUMBER") "SML-LX0606IGC-TR")
        (field (name "MOUSER_PART_NUMBER") "696-SML-0606IGCTR")
      )
      (libsource (lib "eagle-import") (part "B38G3RGB"))
    )
    (comp (ref "LED105")
      (value "B38G3RGB")
      (footprint "eagle-import:B38G3RGB")
      (fields
        (field (name "ARROW_PART_NUMBER") "SML-LX0606IGC-TR")
        (field (name "MOUSER_PART_NUMBER") "696-SML-0606IGCTR")
      )
      (libsource (lib "eagle-import") (part "B38G3RGB"))
    )
    (comp (ref "LED106")
      (value "B38G3RGB")
      (footprint "eagle-import:B38G3RGB")
      (fields
        (field (name "ARROW_PART_NUMBER") "SML-LX0606IGC-TR")
        (field (name "MOUSER_PART_NUMBER") "696-SML-0606IGCTR")
      )
      (libsource (lib "eagle-import") (part "B38G3RGB"))
    )
    (comp (ref "LED107")
      (value "B38G3RGB")
      (footprint "eagle-import:B38G3RGB")
      (fields
        (field (name "ARROW_PART_NUMBER") "SML-LX0606IGC-TR")
        (field (name "MOUSER_PART_NUMBER") "696-SML-0606IGCTR")
      )
      (libsource (lib "eagle-import") (part "B38G3RGB"))
    )
    (comp (ref "LED108")
      (value "B38G3RGB")
      (footprint "eagle-import:B38G3RGB")
      (fields
        (field (name "ARROW_PART_NUMBER") "SML-LX0606IGC-TR")
        (field (name "MOUSER_PART_NUMBER") "696-SML-0606IGCTR")
      )
      (libsource (lib "eagle-import") (part "B38G3RGB"))
    )
    (comp (ref "LED109")
      (value "B38G3RGB")
      (footprint "eagle-import:B38G3RGB")
      (fields
        (field (name "ARROW_PART_NUMBER") "SML-LX0606IGC-TR")
        (field (name "MOUSER_PART_NUMBER") "696-SML-0606IGCTR")
      )
      (libsource (lib "eagle-import") (part "B38G3RGB"))
    )
    (comp (ref "LED110")
      (value "B38G3RGB")
      (footprint "eagle-import:B38G3RGB")
      (fields
        (field (name "ARROW_PART_NUMBER") "SML-LX0606IGC-TR")
        (field (name "MOUSER_PART_NUMBER") "696-SML-0606IGCTR")
      )
      (libsource (lib "eagle-import") (part "B38G3RGB"))
    )
    (comp (ref "LED111")
      (value "B38G3RGB")
      (footprint "eagle-import:B38G3RGB")
      (fields
        (field (name "ARROW_PART_NUMBER") "SML-LX0606IGC-TR")
        (field (name "MOUSER_PART_NUMBER") "696-SML-0606IGCTR")
      )
      (libsource (lib "eagle-import") (part "B38G3RGB"))
    )
    (comp (ref "LED112")
      (value "B38G3RGB")
      (footprint "eagle-import:B38G3RGB")
      (fields
        (field (name "ARROW_PART_NUMBER") "SML-LX0606IGC-TR")
        (field (name "MOUSER_PART_NUMBER") "696-SML-0606IGCTR")
      )
      (libsource (lib "eagle-import") (part "B38G3RGB"))
    )
    (comp (ref "LED113")
      (value "B38G3RGB")
      (footprint "eagle-import:B38G3RGB")
      (fields
        (field (name "ARROW_PART_NUMBER") "SML-LX0606IGC-TR")
        (field (name "MOUSER_PART_NUMBER") "696-SML-0606IGCTR")
      )
      (libsource (lib "eagle-import") (part "B38G3RGB"))
    )
    (comp (ref "LED114")
      (value "B38G3RGB")
      (footprint "eagle-import:B38G3RGB")
      (fields
        (field (name "ARROW_PART_NUMBER") "SML-LX0606IGC-TR")
        (field (name "MOUSER_PART_NUMBER") "696-SML-0606IGCTR")
      )
      (libsource (lib "eagle-import") (part "B38G3RGB"))
    )
    (comp (ref "LED115")
      (value "B38G3RGB")
      (footprint "eagle-import:B38G3RGB")
      (fields
        (field (name "ARROW_PART_NUMBER") "SML-LX0606IGC-TR")
        (field (name "MOUSER_PART_NUMBER") "696-SML-0606IGCTR")
      )
      (libsource (lib "eagle-import") (part "B38G3RGB"))
    )
    (comp (ref "LED116")
      (value "B38G3RGB")
      (footprint "eagle-import:B38G3RGB")
      (fields
        (field (name "ARROW_PART_NUMBER") "SML-LX0606IGC-TR")
        (field (name "MOUSER_PART_NUMBER") "696-SML-0606IGCTR")
      )
      (libsource (lib "eagle-import") (part "B38G3RGB"))
    )
    (comp (ref "LED117")
      (value "B38G3RGB")
      (footprint "eagle-import:B38G3RGB")
      (fields
        (field (name "ARROW_PART_NUMBER") "SML-LX0606IGC-TR")
        (field (name "MOUSER_PART_NUMBER") "696-SML-0606IGCTR")
      )
      (libsource (lib "eagle-import") (part "B38G3RGB"))
    )
    (comp (ref "LED118")
      (value "B38G3RGB")
      (footprint "eagle-import:B38G3RGB")
      (fields
        (field (name "ARROW_PART_NUMBER") "SML-LX0606IGC-TR")
        (field (name "MOUSER_PART_NUMBER") "696-SML-0606IGCTR")
      )
      (libsource (lib "eagle-import") (part "B38G3RGB"))
    )
    (comp (ref "LED119")
      (value "B38G3RGB")
      (footprint "eagle-import:B38G3RGB")
      (fields
        (field (name "ARROW_PART_NUMBER") "SML-LX0606IGC-TR")
        (field (name "MOUSER_PART_NUMBER") "696-SML-0606IGCTR")
      )
      (libsource (lib "eagle-import") (part "B38G3RGB"))
    )
    (comp (ref "LED120")
      (value "B38G3RGB")
      (footprint "eagle-import:B38G3RGB")
      (fields
        (field (name "ARROW_PART_NUMBER") "SML-LX0606IGC-TR")
        (field (name "MOUSER_PART_NUMBER") "696-SML-0606IGCTR")
      )
      (libsource (lib "eagle-import") (part "B38G3RGB"))
    )
    (comp (ref "SV1")
      (value "MA06-2")
      (footprint "eagle-import:MA06-2")
      (libsource (lib "eagle-import") (part "MA06-2"))
    )
  )
  (nets
    (net (code "1") (name "/3V3") (class "Default")
      (node (ref "C1") (pin "1") (pinfunction "1_1") (pintype "passive"))
      (node (ref "C2") (pin "1") (pinfunction "1_1") (pintype "passive"))
      (node (ref "C3") (pin "1") (pinfunction "1_1") (pintype "passive"))
      (node (ref "C4") (pin "1") (pinfunction "1_1") (pintype "passive"))
      (node (ref "C5") (pin "1") (pinfunction "1_1") (pintype "passive"))
      (node (ref "C6") (pin "1") (pinfunction "1_1") (pintype "passive"))
      (node (ref "C7") (pin "1") (pinfunction "1_1") (pintype "passive"))
      (node (ref "C8") (pin "1") (pinfunction "1_1") (pintype "passive"))
      (node (ref "C9") (pin "1") (pinfunction "1_1") (pintype "passive"))
      (node (ref "IC1") (pin "54") (pinfunction "VCC_54") (pintype "bidirectional"))
      (node (ref "IC2") (pin "54") (pinfunction "VCC_54") (pintype "bidirectional"))
      (node (ref "IC3") (pin "54") (pinfunction "VCC_54") (pintype "bidirectional"))
      (node (ref "IC4") (pin "54") (pinfunction "VCC_54") (pintype "bidirectional"))
      (node (ref "IC5") (pin "54") (pinfunction "VCC_54") (pintype "bidirectional"))
      (node (ref "IC6") (pin "54") (pinfunction "VCC_54") (pintype "bidirectional"))
      (node (ref "IC7") (pin "54") (pinfunction "VCC_54") (pintype "bidirectional"))
      (node (ref "IC8") (pin "54") (pinfunction "VCC_54") (pintype "bidirectional"))
      (node (ref "LED1") (pin "3") (pinfunction "COM_3") (pintype "bidirectional"))
      (node (ref "LED10") (pin "3") (pinfunction "COM_3") (pintype "bidirectional"))
      (node (ref "LED100") (pin "3") (pinfunction "COM_3") (pintype "bidirectional"))
      (node (ref "LED101") (pin "3") (pinfunction "COM_3") (pintype "bidirectional"))
      (node (ref "LED102") (pin "3") (pinfunction "COM_3") (pintype "bidirectional"))
      (node (ref "LED103") (pin "3") (pinfunction "COM_3") (pintype "bidirectional"))
      (node (ref "LED104") (pin "3") (pinfunction "COM_3") (pintype "bidirectional"))
      (node (ref "LED105") (pin "3") (pinfunction "COM_3") (pintype "bidirectional"))
      (node (ref "LED106") (pin "3") (pinfunction "COM_3") (pintype "bidirectional"))
      (node (ref "LED107") (pin "3") (pinfunction "COM_3") (pintype "bidirectional"))
      (node (ref "LED108") (pin "3") (pinfunction "COM_3") (pintype "bidirectional"))
      (node (ref "LED109") (pin "3") (pinfunction "COM_3") (pintype "bidirectional"))
      (node (ref "LED11") (pin "3") (pinfunction "COM_3") (pintype "bidirectional"))
      (node (ref "LED110") (pin "3") (pinfunction "COM_3") (pintype "bidirectional"))
      (node (ref "LED111") (pin "3") (pinfunction "COM_3") (pintype "bidirectional"))
      (node (ref "LED112") (pin "3") (pinfunction "COM_3") (pintype "bidirectional"))
      (node (ref "LED113") (pin "3") (pinfunction "COM_3") (pintype "bidirectional"))
      (node (ref "LED114") (pin "3") (pinfunction "COM_3") (pintype "bidirectional"))
      (node (ref "LED115") (pin "3") (pinfunction "COM_3") (pintype "bidirectional"))
      (node (ref "LED116") (pin "3") (pinfunction "COM_3") (pintype "bidirectional"))
      (node (ref "LED117") (pin "3") (pinfunction "COM_3") (pintype "bidirectional"))
      (node (ref "LED118") (pin "3") (pinfunction "COM_3") (pintype "bidirectional"))
      (node (ref "LED119") (pin "3") (pinfunction "COM_3") (pintype "bidirectional"))
      (node (ref "LED12") (pin "3") (pinfunction "COM_3") (pintype "bidirectional"))
      (node (ref "LED120") (pin "3") (pinfunction "COM_3") (pintype "bidirectional"))
      (node (ref "LED13") (pin "3") (pinfunction "COM_3") (pintype "bidirectional"))
      (node (ref "LED14") (pin "3") (pinfunction "COM_3") (pintype "bidirectional"))
      (node (ref "LED15") (pin "3") (pinfunction "COM_3") (pintype "bidirectional"))
      (node (ref "LED16") (pin "3") (pinfunction "COM_3") (pintype "bidirectional"))
      (node (ref "LED17") (pin "3") (pinfunction "COM_3") (pintype "bidirectional"))
      (node (ref "LED18") (pin "3") (pinfunction "COM_3") (pintype "bidirectional"))
      (node (ref "LED19") (pin "3") (pinfunction "COM_3") (pintype "bidirectional"))
      (node (ref "LED2") (pin "3") (pinfunction "COM_3") (pintype "bidirectional"))
      (node (ref "LED20") (pin "3") (pinfunction "COM_3") (pintype "bidirectional"))
      (node (ref "LED21") (pin "3") (pinfunction "COM_3") (pintype "bidirectional"))
      (node (ref "LED22") (pin "3") (pinfunction "COM_3") (pintype "bidirectional"))
      (node (ref "LED23") (pin "3") (pinfunction "COM_3") (pintype "bidirectional"))
      (node (ref "LED24") (pin "3") (pinfunction "COM_3") (pintype "bidirectional"))
      (node (ref "LED25") (pin "3") (pinfunction "COM_3") (pintype "bidirectional"))
      (node (ref "LED26") (pin "3") (pinfunction "COM_3") (pintype "bidirectional"))
      (node (ref "LED27") (pin "3") (pinfunction "COM_3") (pintype "bidirectional"))
      (node (ref "LED28") (pin "3") (pinfunction "COM_3") (pintype "bidirectional"))
      (node (ref "LED29") (pin "3") (pinfunction "COM_3") (pintype "bidirectional"))
      (node (ref "LED3") (pin "3") (pinfunction "COM_3") (pintype "bidirectional"))
      (node (ref "LED30") (pin "3") (pinfunction "COM_3") (pintype "bidirectional"))
      (node (ref "LED31") (pin "3") (pinfunction "COM_3") (pintype "bidirectional"))
      (node (ref "LED32") (pin "3") (pinfunction "COM_3") (pintype "bidirectional"))
      (node (ref "LED33") (pin "3") (pinfunction "COM_3") (pintype "bidirectional"))
      (node (ref "LED34") (pin "3") (pinfunction "COM_3") (pintype "bidirectional"))
      (node (ref "LED35") (pin "3") (pinfunction "COM_3") (pintype "bidirectional"))
      (node (ref "LED36") (pin "3") (pinfunction "COM_3") (pintype "bidirectional"))
      (node (ref "LED37") (pin "3") (pinfunction "COM_3") (pintype "bidirectional"))
      (node (ref "LED38") (pin "3") (pinfunction "COM_3") (pintype "bidirectional"))
      (node (ref "LED39") (pin "3") (pinfunction "COM_3") (pintype "bidirectional"))
      (node (ref "LED4") (pin "3") (pinfunction "COM_3") (pintype "bidirectional"))
      (node (ref "LED40") (pin "3") (pinfunction "COM_3") (pintype "bidirectional"))
      (node (ref "LED41") (pin "3") (pinfunction "COM_3") (pintype "bidirectional"))
      (node (ref "LED42") (pin "3") (pinfunction "COM_3") (pintype "bidirectional"))
      (node (ref "LED43") (pin "3") (pinfunction "COM_3") (pintype "bidirectional"))
      (node (ref "LED44") (pin "3") (pinfunction "COM_3") (pintype "bidirectional"))
      (node (ref "LED45") (pin "3") (pinfunction "COM_3") (pintype "bidirectional"))
      (node (ref "LED46") (pin "3") (pinfunction "COM_3") (pintype "bidirectional"))
      (node (ref "LED47") (pin "3") (pinfunction "COM_3") (pintype "bidirectional"))
      (node (ref "LED48") (pin "3") (pinfunction "COM_3") (pintype "bidirectional"))
      (node (ref "LED49") (pin "3") (pinfunction "COM_3") (pintype "bidirectional"))
      (node (ref "LED5") (pin "3") (pinfunction "COM_3") (pintype "bidirectional"))
      (node (ref "LED50") (pin "3") (pinfunction "COM_3") (pintype "bidirectional"))
      (node (ref "LED51") (pin "3") (pinfunction "COM_3") (pintype "bidirectional"))
      (node (ref "LED52") (pin "3") (pinfunction "COM_3") (pintype "bidirectional"))
      (node (ref "LED53") (pin "3") (pinfunction "COM_3") (pintype "bidirectional"))
      (node (ref "LED54") (pin "3") (pinfunction "COM_3") (pintype "bidirectional"))
      (node (ref "LED55") (pin "3") (pinfunction "COM_3") (pintype "bidirectional"))
      (node (ref "LED56") (pin "3") (pinfunction "COM_3") (pintype "bidirectional"))
      (node (ref "LED57") (pin "3") (pinfunction "COM_3") (pintype "bidirectional"))
      (node (ref "LED58") (pin "3") (pinfunction "COM_3") (pintype "bidirectional"))
      (node (ref "LED59") (pin "3") (pinfunction "COM_3") (pintype "bidirectional"))
      (node (ref "LED6") (pin "3") (pinfunction "COM_3") (pintype "bidirectional"))
      (node (ref "LED60") (pin "3") (pinfunction "COM_3") (pintype "bidirectional"))
      (node (ref "LED61") (pin "3") (pinfunction "COM_3") (pintype "bidirectional"))
      (node (ref "LED62") (pin "3") (pinfunction "COM_3") (pintype "bidirectional"))
      (node (ref "LED63") (pin "3") (pinfunction "COM_3") (pintype "bidirectional"))
      (node (ref "LED64") (pin "3") (pinfunction "COM_3") (pintype "bidirectional"))
      (node (ref "LED65") (pin "3") (pinfunction "COM_3") (pintype "bidirectional"))
      (node (ref "LED66") (pin "3") (pinfunction "COM_3") (pintype "bidirectional"))
      (node (ref "LED67") (pin "3") (pinfunction "COM_3") (pintype "bidirectional"))
      (node (ref "LED68") (pin "3") (pinfunction "COM_3") (pintype "bidirectional"))
      (node (ref "LED69") (pin "3") (pinfunction "COM_3") (pintype "bidirectional"))
      (node (ref "LED7") (pin "3") (pinfunction "COM_3") (pintype "bidirectional"))
      (node (ref "LED70") (pin "3") (pinfunction "COM_3") (pintype "bidirectional"))
      (node (ref "LED71") (pin "3") (pinfunction "COM_3") (pintype "bidirectional"))
      (node (ref "LED72") (pin "3") (pinfunction "COM_3") (pintype "bidirectional"))
      (node (ref "LED73") (pin "3") (pinfunction "COM_3") (pintype "bidirectional"))
      (node (ref "LED74") (pin "3") (pinfunction "COM_3") (pintype "bidirectional"))
      (node (ref "LED75") (pin "3") (pinfunction "COM_3") (pintype "bidirectional"))
      (node (ref "LED76") (pin "3") (pinfunction "COM_3") (pintype "bidirectional"))
      (node (ref "LED77") (pin "3") (pinfunction "COM_3") (pintype "bidirectional"))
      (node (ref "LED78") (pin "3") (pinfunction "COM_3") (pintype "bidirectional"))
      (node (ref "LED79") (pin "3") (pinfunction "COM_3") (pintype "bidirectional"))
      (node (ref "LED8") (pin "3") (pinfunction "COM_3") (pintype "bidirectional"))
      (node (ref "LED80") (pin "3") (pinfunction "COM_3") (pintype "bidirectional"))
      (node (ref "LED81") (pin "3") (pinfunction "COM_3") (pintype "bidirectional"))
      (node (ref "LED82") (pin "3") (pinfunction "COM_3") (pintype "bidirectional"))
      (node (ref "LED83") (pin "3") (pinfunction "COM_3") (pintype "bidirectional"))
      (node (ref "LED84") (pin "3") (pinfunction "COM_3") (pintype "bidirectional"))
      (node (ref "LED85") (pin "3") (pinfunction "COM_3") (pintype "bidirectional"))
      (node (ref "LED86") (pin "3") (pinfunction "COM_3") (pintype "bidirectional"))
      (node (ref "LED87") (pin "3") (pinfunction "COM_3") (pintype "bidirectional"))
      (node (ref "LED88") (pin "3") (pinfunction "COM_3") (pintype "bidirectional"))
      (node (ref "LED89") (pin "3") (pinfunction "COM_3") (pintype "bidirectional"))
      (node (ref "LED9") (pin "3") (pinfunction "COM_3") (pintype "bidirectional"))
      (node (ref "LED90") (pin "3") (pinfunction "COM_3") (pintype "bidirectional"))
      (node (ref "LED91") (pin "3") (pinfunction "COM_3") (pintype "bidirectional"))
      (node (ref "LED92") (pin "3") (pinfunction "COM_3") (pintype "bidirectional"))
      (node (ref "LED93") (pin "3") (pinfunction "COM_3") (pintype "bidirectional"))
      (node (ref "LED94") (pin "3") (pinfunction "COM_3") (pintype "bidirectional"))
      (node (ref "LED95") (pin "3") (pinfunction "COM_3") (pintype "bidirectional"))
      (node (ref "LED96") (pin "3") (pinfunction "COM_3") (pintype "bidirectional"))
      (node (ref "LED97") (pin "3") (pinfunction "COM_3") (pintype "bidirectional"))
      (node (ref "LED98") (pin "3") (pinfunction "COM_3") (pintype "bidirectional"))
      (node (ref "LED99") (pin "3") (pinfunction "COM_3") (pintype "bidirectional"))
      (node (ref "SV1") (pin "10") (pinfunction "10_10") (pintype "passive"))
      (node (ref "SV1") (pin "9") (pinfunction "9_9") (pintype "passive"))
    )
    (net (code "2") (name "/GND") (class "Default")
      (node (ref "C1") (pin "2") (pinfunction "2_2") (pintype "passive"))
      (node (ref "C2") (pin "2") (pinfunction "2_2") (pintype "passive"))
      (node (ref "C3") (pin "2") (pinfunction "2_2") (pintype "passive"))
      (node (ref "C4") (pin "2") (pinfunction "2_2") (pintype "passive"))
      (node (ref "C5") (pin "2") (pinfunction "2_2") (pintype "passive"))
      (node (ref "C6") (pin "2") (pinfunction "2_2") (pintype "passive"))
      (node (ref "C7") (pin "2") (pinfunction "2_2") (pintype "passive"))
      (node (ref "C8") (pin "2") (pinfunction "2_2") (pintype "passive"))
      (node (ref "C9") (pin "2") (pinfunction "2_2") (pintype "passive"))
      (node (ref "IC1") (pin "29") (pinfunction "GND_1_29") (pintype "bidirectional"))
      (node (ref "IC1") (pin "56") (pinfunction "GND_2_56") (pintype "bidirectional"))
      (node (ref "IC1") (pin "57") (pinfunction "THERMALPAD_57") (pintype "bidirectional"))
      (node (ref "IC2") (pin "29") (pinfunction "GND_1_29") (pintype "bidirectional"))
      (node (ref "IC2") (pin "56") (pinfunction "GND_2_56") (pintype "bidirectional"))
      (node (ref "IC2") (pin "57") (pinfunction "THERMALPAD_57") (pintype "bidirectional"))
      (node (ref "IC3") (pin "29") (pinfunction "GND_1_29") (pintype "bidirectional"))
      (node (ref "IC3") (pin "56") (pinfunction "GND_2_56") (pintype "bidirectional"))
      (node (ref "IC3") (pin "57") (pinfunction "THERMALPAD_57") (pintype "bidirectional"))
      (node (ref "IC4") (pin "29") (pinfunction "GND_1_29") (pintype "bidirectional"))
      (node (ref "IC4") (pin "56") (pinfunction "GND_2_56") (pintype "bidirectional"))
      (node (ref "IC4") (pin "57") (pinfunction "THERMALPAD_57") (pintype "bidirectional"))
      (node (ref "IC5") (pin "29") (pinfunction "GND_1_29") (pintype "bidirectional"))
      (node (ref "IC5") (pin "56") (pinfunction "GND_2_56") (pintype "bidirectional"))
      (node (ref "IC5") (pin "57") (pinfunction "THERMALPAD_57") (pintype "bidirectional"))
      (node (ref "IC6") (pin "29") (pinfunction "GND_1_29") (pintype "bidirectional"))
      (node (ref "IC6") (pin "56") (pinfunction "GND_2_56") (pintype "bidirectional"))
      (node (ref "IC6") (pin "57") (pinfunction "THERMALPAD_57") (pintype "bidirectional"))
      (node (ref "IC7") (pin "29") (pinfunction "GND_1_29") (pintype "bidirectional"))
      (node (ref "IC7") (pin "56") (pinfunction "GND_2_56") (pintype "bidirectional"))
      (node (ref "IC7") (pin "57") (pinfunction "THERMALPAD_57") (pintype "bidirectional"))
      (node (ref "IC8") (pin "29") (pinfunction "GND_1_29") (pintype "bidirectional"))
      (node (ref "IC8") (pin "56") (pinfunction "GND_2_56") (pintype "bidirectional"))
      (node (ref "IC8") (pin "57") (pinfunction "THERMALPAD_57") (pintype "bidirectional"))
      (node (ref "SV1") (pin "11") (pinfunction "11_11") (pintype "passive"))
      (node (ref "SV1") (pin "12") (pinfunction "12_12") (pintype "passive"))
    )
    (net (code "3") (name "/GSCLK") (class "Default")
      (node (ref "IC1") (pin "55") (pinfunction "GSCLK_55") (pintype "bidirectional"))
      (node (ref "IC2") (pin "55") (pinfunction "GSCLK_55") (pintype "bidirectional"))
      (node (ref "IC3") (pin "55") (pinfunction "GSCLK_55") (pintype "bidirectional"))
      (node (ref "IC4") (pin "55") (pinfunction "GSCLK_55") (pintype "bidirectional"))
      (node (ref "IC5") (pin "55") (pinfunction "GSCLK_55") (pintype "bidirectional"))
      (node (ref "IC6") (pin "55") (pinfunction "GSCLK_55") (pintype "bidirectional"))
      (node (ref "IC7") (pin "55") (pinfunction "GSCLK_55") (pintype "bidirectional"))
      (node (ref "IC8") (pin "55") (pinfunction "GSCLK_55") (pintype "bidirectional"))
      (node (ref "SV1") (pin "6") (pinfunction "6_6") (pintype "passive"))
    )
    (net (code "4") (name "/LAT") (class "Default")
      (node (ref "IC1") (pin "3") (pinfunction "LAT_3") (pintype "bidirectional"))
      (node (ref "IC2") (pin "3") (pinfunction "LAT_3") (pintype "bidirectional"))
      (node (ref "IC3") (pin "3") (pinfunction "LAT_3") (pintype "bidirectional"))
      (node (ref "IC4") (pin "3") (pinfunction "LAT_3") (pintype "bidirectional"))
      (node (ref "IC5") (pin "3") (pinfunction "LAT_3") (pintype "bidirectional"))
      (node (ref "IC6") (pin "3") (pinfunction "LAT_3") (pintype "bidirectional"))
      (node (ref "IC7") (pin "3") (pinfunction "LAT_3") (pintype "bidirectional"))
      (node (ref "IC8") (pin "3") (pinfunction "LAT_3") (pintype "bidirectional"))
      (node (ref "SV1") (pin "8") (pinfunction "8_8") (pintype "passive"))
    )
    (net (code "5") (name "/N$352") (class "Default")
      (node (ref "IC8") (pin "53") (pinfunction "OUTB8_53") (pintype "bidirectional"))
    )
    (net (code "6") (name "/N$353") (class "Default")
      (node (ref "IC8") (pin "52") (pinfunction "OUTR8_52") (pintype "bidirectional"))
    )
    (net (code "7") (name "/N$354") (class "Default")
      (node (ref "IC8") (pin "51") (pinfunction "OUTG8_51") (pintype "bidirectional"))
    )
    (net (code "8") (name "/N$355") (class "Default")
      (node (ref "IC8") (pin "50") (pinfunction "OUTB12_50") (pintype "bidirectional"))
    )
    (net (code "9") (name "/N$356") (class "Default")
      (node (ref "IC8") (pin "49") (pinfunction "OUTR12_49") (pintype "bidirectional"))
    )
    (net (code "10") (name "/N$357") (class "Default")
      (node (ref "IC8") (pin "48") (pinfunction "OUTG12_48") (pintype "bidirectional"))
    )
    (net (code "11") (name "/N$358") (class "Default")
      (node (ref "IC8") (pin "47") (pinfunction "OUTB9_47") (pintype "bidirectional"))
    )
    (net (code "12") (name "/N$359") (class "Default")
      (node (ref "IC8") (pin "46") (pinfunction "OUTR9_46") (pintype "bidirectional"))
    )
    (net (code "13") (name "/N$360") (class "Default")
      (node (ref "IC8") (pin "45") (pinfunction "OUTG9_45") (pintype "bidirectional"))
    )
    (net (code "14") (name "/N$361") (class "Default")
      (node (ref "IC8") (pin "44") (pinfunction "OUTB13_44") (pintype "bidirectional"))
    )
    (net (code "15") (name "/N$362") (class "Default")
      (node (ref "IC8") (pin "43") (pinfunction "OUTR13_43") (pintype "bidirectional"))
    )
    (net (code "16") (name "/N$363") (class "Default")
      (node (ref "IC8") (pin "42") (pinfunction "OUTG13_42") (pintype "bidirectional"))
    )
    (net (code "17") (name "/N$364") (class "Default")
      (node (ref "IC8") (pin "41") (pinfunction "OUTB14_41") (pintype "bidirectional"))
    )
    (net (code "18") (name "/N$365") (class "Default")
      (node (ref "IC8") (pin "40") (pinfunction "OUTR14_40") (pintype "bidirectional"))
    )
    (net (code "19") (name "/N$366") (class "Default")
      (node (ref "IC8") (pin "39") (pinfunction "OUTG14_39") (pintype "bidirectional"))
    )
    (net (code "20") (name "/N$367") (class "Default")
      (node (ref "IC8") (pin "38") (pinfunction "OUTB10_38") (pintype "bidirectional"))
    )
    (net (code "21") (name "/N$368") (class "Default")
      (node (ref "IC8") (pin "37") (pinfunction "OUTR10_37") (pintype "bidirectional"))
    )
    (net (code "22") (name "/N$369") (class "Default")
      (node (ref "IC8") (pin "36") (pinfunction "OUTG10_36") (pintype "bidirectional"))
    )
    (net (code "23") (name "/N$370") (class "Default")
      (node (ref "IC8") (pin "35") (pinfunction "OUTB15_35") (pintype "bidirectional"))
    )
    (net (code "24") (name "/N$371") (class "Default")
      (node (ref "IC8") (pin "34") (pinfunction "OUTR15_34") (pintype "bidirectional"))
    )
    (net (code "25") (name "/N$372") (class "Default")
      (node (ref "IC8") (pin "33") (pinfunction "OUTG15_33") (pintype "bidirectional"))
    )
    (net (code "26") (name "/N$373") (class "Default")
      (node (ref "IC8") (pin "32") (pinfunction "OUTB11_32") (pintype "bidirectional"))
    )
    (net (code "27") (name "/N$374") (class "Default")
      (node (ref "IC8") (pin "31") (pinfunction "OUTR11_31") (pintype "bidirectional"))
    )
    (net (code "28") (name "/N$375") (class "Default")
      (node (ref "IC8") (pin "30") (pinfunction "OUTG11_30") (pintype "bidirectional"))
    )
    (net (code "29") (name "/N$LEDB1_IC1_PIN4") (class "Default")
      (node (ref "IC1") (pin "4") (pinfunction "OUTB4_4") (pintype "bidirectional"))
      (node (ref "LED1") (pin "2") (pinfunction "BLUE_2") (pintype "bidirectional"))
    )
    (net (code "30") (name "/N$LEDB2_IC1_PIN10") (class "Default")
      (node (ref "IC1") (pin "10") (pinfunction "OUTB5_10") (pintype "bidirectional"))
      (node (ref "LED2") (pin "2") (pinfunction "BLUE_2") (pintype "bidirectional"))
    )
    (net (code "31") (name "/N$LEDB3_IC1_PIN16") (class "Default")
      (node (ref "IC1") (pin "16") (pinfunction "OUTB2_16") (pintype "bidirectional"))
      (node (ref "LED3") (pin "2") (pinfunction "BLUE_2") (pintype "bidirectional"))
    )
    (net (code "32") (name "/N$LEDB4_IC1_PIN22") (class "Default")
      (node (ref "IC1") (pin "22") (pinfunction "OUTB3_22") (pintype "bidirectional"))
      (node (ref "LED4") (pin "2") (pinfunction "BLUE_2") (pintype "bidirectional"))
    )
    (net (code "33") (name "/N$LEDB5_IC1_PIN7") (class "Default")
      (node (ref "IC1") (pin "7") (pinfunction "OUTB0_7") (pintype "bidirectional"))
      (node (ref "LED5") (pin "2") (pinfunction "BLUE_2") (pintype "bidirectional"))
    )
    (net (code "34") (name "/N$LEDB6_IC1_PIN13") (class "Default")
      (node (ref "IC1") (pin "13") (pinfunction "OUTB1_13") (pintype "bidirectional"))
      (node (ref "LED6") (pin "2") (pinfunction "BLUE_2") (pintype "bidirectional"))
    )
    (net (code "35") (name "/N$LEDB7_IC1_PIN19") (class "Default")
      (node (ref "IC1") (pin "19") (pinfunction "OUTB6_19") (pintype "bidirectional"))
      (node (ref "LED7") (pin "2") (pinfunction "BLUE_2") (pintype "bidirectional"))
    )
    (net (code "36") (name "/N$LEDB8_IC1_PIN25") (class "Default")
      (node (ref "IC1") (pin "25") (pinfunction "OUTB7_25") (pintype "bidirectional"))
      (node (ref "LED8") (pin "2") (pinfunction "BLUE_2") (pintype "bidirectional"))
    )
    (net (code "37") (name "/N$LEDB9_IC1_PIN53") (class "Default")
      (node (ref "IC1") (pin "53") (pinfunction "OUTB8_53") (pintype "bidirectional"))
      (node (ref "LED9") (pin "2") (pinfunction "BLUE_2") (pintype "bidirectional"))
    )
    (net (code "38") (name "/N$LEDB10_IC1_PIN47") (class "Default")
      (node (ref "IC1") (pin "47") (pinfunction "OUTB9_47") (pintype "bidirectional"))
      (node (ref "LED10") (pin "2") (pinfunction "BLUE_2") (pintype "bidirectional"))
    )
    (net (code "39") (name "/N$LEDB11_IC1_PIN41") (class "Default")
      (node (ref "IC1") (pin "41") (pinfunction "OUTB14_41") (pintype "bidirectional"))
      (node (ref "LED11") (pin "2") (pinfunction "BLUE_2") (pintype "bidirectional"))
    )
    (net (code "40") (name "/N$LEDB12_IC1_PIN35") (class "Default")
      (node (ref "IC1") (pin "35") (pinfunction "OUTB15_35") (pintype "bidirectional"))
      (node (ref "LED12") (pin "2") (pinfunction "BLUE_2") (pintype "bidirectional"))
    )
    (net (code "41") (name "/N$LEDB13_IC1_PIN50") (class "Default")
      (node (ref "IC1") (pin "50") (pinfunction "OUTB12_50") (pintype "bidirectional"))
      (node (ref "LED13") (pin "2") (pinfunction "BLUE_2") (pintype "bidirectional"))
    )
    (net (code "42") (name "/N$LEDB14_IC1_PIN44") (class "Default")
      (node (ref "IC1") (pin "44") (pinfunction "OUTB13_44") (pintype "bidirectional"))
      (node (ref "LED14") (pin "2") (pinfunction "BLUE_2") (pintype "bidirectional"))
    )
    (net (code "43") (name "/N$LEDB15_IC1_PIN38") (class "Default")
      (node (ref "IC1") (pin "38") (pinfunction "OUTB10_38") (pintype "bidirectional"))
      (node (ref "LED15") (pin "2") (pinfunction "BLUE_2") (pintype "bidirectional"))
    )
    (net (code "44") (name "/N$LEDB16_IC1_PIN32") (class "Default")
      (node (ref "IC1") (pin "32") (pinfunction "OUTB11_32") (pintype "bidirectional"))
      (node (ref "LED16") (pin "2") (pinfunction "BLUE_2") (pintype "bidirectional"))
    )
    (net (code "45") (name "/N$LEDB17_IC2_PIN4") (class "Default")
      (node (ref "IC2") (pin "4") (pinfunction "OUTB4_4") (pintype "bidirectional"))
      (node (ref "LED17") (pin "2") (pinfunction "BLUE_2") (pintype "bidirectional"))
    )
    (net (code "46") (name "/N$LEDB18_IC2_PIN10") (class "Default")
      (node (ref "IC2") (pin "10") (pinfunction "OUTB5_10") (pintype "bidirectional"))
      (node (ref "LED18") (pin "2") (pinfunction "BLUE_2") (pintype "bidirectional"))
    )
    (net (code "47") (name "/N$LEDB19_IC2_PIN16") (class "Default")
      (node (ref "IC2") (pin "16") (pinfunction "OUTB2_16") (pintype "bidirectional"))
      (node (ref "LED19") (pin "2") (pinfunction "BLUE_2") (pintype "bidirectional"))
    )
    (net (code "48") (name "/N$LEDB20_IC2_PIN22") (class "Default")
      (node (ref "IC2") (pin "22") (pinfunction "OUTB3_22") (pintype "bidirectional"))
      (node (ref "LED20") (pin "2") (pinfunction "BLUE_2") (pintype "bidirectional"))
    )
    (net (code "49") (name "/N$LEDB21_IC2_PIN7") (class "Default")
      (node (ref "IC2") (pin "7") (pinfunction "OUTB0_7") (pintype "bidirectional"))
      (node (ref "LED21") (pin "2") (pinfunction "BLUE_2") (pintype "bidirectional"))
    )
    (net (code "50") (name "/N$LEDB22_IC2_PIN13") (class "Default")
      (node (ref "IC2") (pin "13") (pinfunction "OUTB1_13") (pintype "bidirectional"))
      (node (ref "LED22") (pin "2") (pinfunction "BLUE_2") (pintype "bidirectional"))
    )
    (net (code "51") (name "/N$LEDB23_IC2_PIN19") (class "Default")
      (node (ref "IC2") (pin "19") (pinfunction "OUTB6_19") (pintype "bidirectional"))
      (node (ref "LED23") (pin "2") (pinfunction "BLUE_2") (pintype "bidirectional"))
    )
    (net (code "52") (name "/N$LEDB24_IC2_PIN25") (class "Default")
      (node (ref "IC2") (pin "25") (pinfunction "OUTB7_25") (pintype "bidirectional"))
      (node (ref "LED24") (pin "2") (pinfunction "BLUE_2") (pintype "bidirectional"))
    )
    (net (code "53") (name "/N$LEDB25_IC2_PIN53") (class "Default")
      (node (ref "IC2") (pin "53") (pinfunction "OUTB8_53") (pintype "bidirectional"))
      (node (ref "LED25") (pin "2") (pinfunction "BLUE_2") (pintype "bidirectional"))
    )
    (net (code "54") (name "/N$LEDB26_IC2_PIN47") (class "Default")
      (node (ref "IC2") (pin "47") (pinfunction "OUTB9_47") (pintype "bidirectional"))
      (node (ref "LED26") (pin "2") (pinfunction "BLUE_2") (pintype "bidirectional"))
    )
    (net (code "55") (name "/N$LEDB27_IC2_PIN41") (class "Default")
      (node (ref "IC2") (pin "41") (pinfunction "OUTB14_41") (pintype "bidirectional"))
      (node (ref "LED27") (pin "2") (pinfunction "BLUE_2") (pintype "bidirectional"))
    )
    (net (code "56") (name "/N$LEDB28_IC2_PIN35") (class "Default")
      (node (ref "IC2") (pin "35") (pinfunction "OUTB15_35") (pintype "bidirectional"))
      (node (ref "LED28") (pin "2") (pinfunction "BLUE_2") (pintype "bidirectional"))
    )
    (net (code "57") (name "/N$LEDB29_IC2_PIN50") (class "Default")
      (node (ref "IC2") (pin "50") (pinfunction "OUTB12_50") (pintype "bidirectional"))
      (node (ref "LED29") (pin "2") (pinfunction "BLUE_2") (pintype "bidirectional"))
    )
    (net (code "58") (name "/N$LEDB30_IC2_PIN44") (class "Default")
      (node (ref "IC2") (pin "44") (pinfunction "OUTB13_44") (pintype "bidirectional"))
      (node (ref "LED30") (pin "2") (pinfunction "BLUE_2") (pintype "bidirectional"))
    )
    (net (code "59") (name "/N$LEDB31_IC2_PIN38") (class "Default")
      (node (ref "IC2") (pin "38") (pinfunction "OUTB10_38") (pintype "bidirectional"))
      (node (ref "LED31") (pin "2") (pinfunction "BLUE_2") (pintype "bidirectional"))
    )
    (net (code "60") (name "/N$LEDB32_IC2_PIN32") (class "Default")
      (node (ref "IC2") (pin "32") (pinfunction "OUTB11_32") (pintype "bidirectional"))
      (node (ref "LED32") (pin "2") (pinfunction "BLUE_2") (pintype "bidirectional"))
    )
    (net (code "61") (name "/N$LEDB33_IC3_PIN4") (class "Default")
      (node (ref "IC3") (pin "4") (pinfunction "OUTB4_4") (pintype "bidirectional"))
      (node (ref "LED33") (pin "2") (pinfunction "BLUE_2") (pintype "bidirectional"))
    )
    (net (code "62") (name "/N$LEDB34_IC3_PIN10") (class "Default")
      (node (ref "IC3") (pin "10") (pinfunction "OUTB5_10") (pintype "bidirectional"))
      (node (ref "LED34") (pin "2") (pinfunction "BLUE_2") (pintype "bidirectional"))
    )
    (net (code "63") (name "/N$LEDB35_IC3_PIN16") (class "Default")
      (node (ref "IC3") (pin "16") (pinfunction "OUTB2_16") (pintype "bidirectional"))
      (node (ref "LED35") (pin "2") (pinfunction "BLUE_2") (pintype "bidirectional"))
    )
    (net (code "64") (name "/N$LEDB36_IC3_PIN22") (class "Default")
      (node (ref "IC3") (pin "22") (pinfunction "OUTB3_22") (pintype "bidirectional"))
      (node (ref "LED36") (pin "2") (pinfunction "BLUE_2") (pintype "bidirectional"))
    )
    (net (code "65") (name "/N$LEDB37_IC3_PIN7") (class "Default")
      (node (ref "IC3") (pin "7") (pinfunction "OUTB0_7") (pintype "bidirectional"))
      (node (ref "LED37") (pin "2") (pinfunction "BLUE_2") (pintype "bidirectional"))
    )
    (net (code "66") (name "/N$LEDB38_IC3_PIN13") (class "Default")
      (node (ref "IC3") (pin "13") (pinfunction "OUTB1_13") (pintype "bidirectional"))
      (node (ref "LED38") (pin "2") (pinfunction "BLUE_2") (pintype "bidirectional"))
    )
    (net (code "67") (name "/N$LEDB39_IC3_PIN19") (class "Default")
      (node (ref "IC3") (pin "19") (pinfunction "OUTB6_19") (pintype "bidirectional"))
      (node (ref "LED39") (pin "2") (pinfunction "BLUE_2") (pintype "bidirectional"))
    )
    (net (code "68") (name "/N$LEDB40_IC3_PIN25") (class "Default")
      (node (ref "IC3") (pin "25") (pinfunction "OUTB7_25") (pintype "bidirectional"))
      (node (ref "LED40") (pin "2") (pinfunction "BLUE_2") (pintype "bidirectional"))
    )
    (net (code "69") (name "/N$LEDB41_IC3_PIN53") (class "Default")
      (node (ref "IC3") (pin "53") (pinfunction "OUTB8_53") (pintype "bidirectional"))
      (node (ref "LED41") (pin "2") (pinfunction "BLUE_2") (pintype "bidirectional"))
    )
    (net (code "70") (name "/N$LEDB42_IC3_PIN47") (class "Default")
      (node (ref "IC3") (pin "47") (pinfunction "OUTB9_47") (pintype "bidirectional"))
      (node (ref "LED42") (pin "2") (pinfunction "BLUE_2") (pintype "bidirectional"))
    )
    (net (code "71") (name "/N$LEDB43_IC3_PIN41") (class "Default")
      (node (ref "IC3") (pin "41") (pinfunction "OUTB14_41") (pintype "bidirectional"))
      (node (ref "LED43") (pin "2") (pinfunction "BLUE_2") (pintype "bidirectional"))
    )
    (net (code "72") (name "/N$LEDB44_IC3_PIN35") (class "Default")
      (node (ref "IC3") (pin "35") (pinfunction "OUTB15_35") (pintype "bidirectional"))
      (node (ref "LED44") (pin "2") (pinfunction "BLUE_2") (pintype "bidirectional"))
    )
    (net (code "73") (name "/N$LEDB45_IC3_PIN50") (class "Default")
      (node (ref "IC3") (pin "50") (pinfunction "OUTB12_50") (pintype "bidirectional"))
      (node (ref "LED45") (pin "2") (pinfunction "BLUE_2") (pintype "bidirectional"))
    )
    (net (code "74") (name "/N$LEDB46_IC3_PIN44") (class "Default")
      (node (ref "IC3") (pin "44") (pinfunction "OUTB13_44") (pintype "bidirectional"))
      (node (ref "LED46") (pin "2") (pinfunction "BLUE_2") (pintype "bidirectional"))
    )
    (net (code "75") (name "/N$LEDB47_IC3_PIN38") (class "Default")
      (node (ref "IC3") (pin "38") (pinfunction "OUTB10_38") (pintype "bidirectional"))
      (node (ref "LED47") (pin "2") (pinfunction "BLUE_2") (pintype "bidirectional"))
    )
    (net (code "76") (name "/N$LEDB48_IC3_PIN32") (class "Default")
      (node (ref "IC3") (pin "32") (pinfunction "OUTB11_32") (pintype "bidirectional"))
      (node (ref "LED48") (pin "2") (pinfunction "BLUE_2") (pintype "bidirectional"))
    )
    (net (code "77") (name "/N$LEDB49_IC4_PIN4") (class "Default")
      (node (ref "IC4") (pin "4") (pinfunction "OUTB4_4") (pintype "bidirectional"))
      (node (ref "LED49") (pin "2") (pinfunction "BLUE_2") (pintype "bidirectional"))
    )
    (net (code "78") (name "/N$LEDB50_IC4_PIN10") (class "Default")
      (node (ref "IC4") (pin "10") (pinfunction "OUTB5_10") (pintype "bidirectional"))
      (node (ref "LED50") (pin "2") (pinfunction "BLUE_2") (pintype "bidirectional"))
    )
    (net (code "79") (name "/N$LEDB51_IC4_PIN16") (class "Default")
      (node (ref "IC4") (pin "16") (pinfunction "OUTB2_16") (pintype "bidirectional"))
      (node (ref "LED51") (pin "2") (pinfunction "BLUE_2") (pintype "bidirectional"))
    )
    (net (code "80") (name "/N$LEDB52_IC4_PIN22") (class "Default")
      (node (ref "IC4") (pin "22") (pinfunction "OUTB3_22") (pintype "bidirectional"))
      (node (ref "LED52") (pin "2") (pinfunction "BLUE_2") (pintype "bidirectional"))
    )
    (net (code "81") (name "/N$LEDB53_IC4_PIN7") (class "Default")
      (node (ref "IC4") (pin "7") (pinfunction "OUTB0_7") (pintype "bidirectional"))
      (node (ref "LED53") (pin "2") (pinfunction "BLUE_2") (pintype "bidirectional"))
    )
    (net (code "82") (name "/N$LEDB54_IC4_PIN13") (class "Default")
      (node (ref "IC4") (pin "13") (pinfunction "OUTB1_13") (pintype "bidirectional"))
      (node (ref "LED54") (pin "2") (pinfunction "BLUE_2") (pintype "bidirectional"))
    )
    (net (code "83") (name "/N$LEDB55_IC4_PIN19") (class "Default")
      (node (ref "IC4") (pin "19") (pinfunction "OUTB6_19") (pintype "bidirectional"))
      (node (ref "LED55") (pin "2") (pinfunction "BLUE_2") (pintype "bidirectional"))
    )
    (net (code "84") (name "/N$LEDB56_IC4_PIN25") (class "Default")
      (node (ref "IC4") (pin "25") (pinfunction "OUTB7_25") (pintype "bidirectional"))
      (node (ref "LED56") (pin "2") (pinfunction "BLUE_2") (pintype "bidirectional"))
    )
    (net (code "85") (name "/N$LEDB57_IC4_PIN53") (class "Default")
      (node (ref "IC4") (pin "53") (pinfunction "OUTB8_53") (pintype "bidirectional"))
      (node (ref "LED57") (pin "2") (pinfunction "BLUE_2") (pintype "bidirectional"))
    )
    (net (code "86") (name "/N$LEDB58_IC4_PIN47") (class "Default")
      (node (ref "IC4") (pin "47") (pinfunction "OUTB9_47") (pintype "bidirectional"))
      (node (ref "LED58") (pin "2") (pinfunction "BLUE_2") (pintype "bidirectional"))
    )
    (net (code "87") (name "/N$LEDB59_IC4_PIN41") (class "Default")
      (node (ref "IC4") (pin "41") (pinfunction "OUTB14_41") (pintype "bidirectional"))
      (node (ref "LED59") (pin "2") (pinfunction "BLUE_2") (pintype "bidirectional"))
    )
    (net (code "88") (name "/N$LEDB60_IC4_PIN35") (class "Default")
      (node (ref "IC4") (pin "35") (pinfunction "OUTB15_35") (pintype "bidirectional"))
      (node (ref "LED60") (pin "2") (pinfunction "BLUE_2") (pintype "bidirectional"))
    )
    (net (code "89") (name "/N$LEDB61_IC4_PIN50") (class "Default")
      (node (ref "IC4") (pin "50") (pinfunction "OUTB12_50") (pintype "bidirectional"))
      (node (ref "LED61") (pin "2") (pinfunction "BLUE_2") (pintype "bidirectional"))
    )
    (net (code "90") (name "/N$LEDB62_IC4_PIN44") (class "Default")
      (node (ref "IC4") (pin "44") (pinfunction "OUTB13_44") (pintype "bidirectional"))
      (node (ref "LED62") (pin "2") (pinfunction "BLUE_2") (pintype "bidirectional"))
    )
    (net (code "91") (name "/N$LEDB63_IC4_PIN38") (class "Default")
      (node (ref "IC4") (pin "38") (pinfunction "OUTB10_38") (pintype "bidirectional"))
      (node (ref "LED63") (pin "2") (pinfunction "BLUE_2") (pintype "bidirectional"))
    )
    (net (code "92") (name "/N$LEDB64_IC4_PIN32") (class "Default")
      (node (ref "IC4") (pin "32") (pinfunction "OUTB11_32") (pintype "bidirectional"))
      (node (ref "LED64") (pin "2") (pinfunction "BLUE_2") (pintype "bidirectional"))
    )
    (net (code "93") (name "/N$LEDB65_IC5_PIN4") (class "Default")
      (node (ref "IC5") (pin "4") (pinfunction "OUTB4_4") (pintype "bidirectional"))
      (node (ref "LED65") (pin "2") (pinfunction "BLUE_2") (pintype "bidirectional"))
    )
    (net (code "94") (name "/N$LEDB66_IC5_PIN10") (class "Default")
      (node (ref "IC5") (pin "10") (pinfunction "OUTB5_10") (pintype "bidirectional"))
      (node (ref "LED66") (pin "2") (pinfunction "BLUE_2") (pintype "bidirectional"))
    )
    (net (code "95") (name "/N$LEDB67_IC5_PIN16") (class "Default")
      (node (ref "IC5") (pin "16") (pinfunction "OUTB2_16") (pintype "bidirectional"))
      (node (ref "LED67") (pin "2") (pinfunction "BLUE_2") (pintype "bidirectional"))
    )
    (net (code "96") (name "/N$LEDB68_IC5_PIN22") (class "Default")
      (node (ref "IC5") (pin "22") (pinfunction "OUTB3_22") (pintype "bidirectional"))
      (node (ref "LED68") (pin "2") (pinfunction "BLUE_2") (pintype "bidirectional"))
    )
    (net (code "97") (name "/N$LEDB69_IC5_PIN7") (class "Default")
      (node (ref "IC5") (pin "7") (pinfunction "OUTB0_7") (pintype "bidirectional"))
      (node (ref "LED69") (pin "2") (pinfunction "BLUE_2") (pintype "bidirectional"))
    )
    (net (code "98") (name "/N$LEDB70_IC5_PIN13") (class "Default")
      (node (ref "IC5") (pin "13") (pinfunction "OUTB1_13") (pintype "bidirectional"))
      (node (ref "LED70") (pin "2") (pinfunction "BLUE_2") (pintype "bidirectional"))
    )
    (net (code "99") (name "/N$LEDB71_IC5_PIN19") (class "Default")
      (node (ref "IC5") (pin "19") (pinfunction "OUTB6_19") (pintype "bidirectional"))
      (node (ref "LED71") (pin "2") (pinfunction "BLUE_2") (pintype "bidirectional"))
    )
    (net (code "100") (name "/N$LEDB72_IC5_PIN25") (class "Default")
      (node (ref "IC5") (pin "25") (pinfunction "OUTB7_25") (pintype "bidirectional"))
      (node (ref "LED72") (pin "2") (pinfunction "BLUE_2") (pintype "bidirectional"))
    )
    (net (code "101") (name "/N$LEDB73_IC5_PIN53") (class "Default")
      (node (ref "IC5") (pin "53") (pinfunction "OUTB8_53") (pintype "bidirectional"))
      (node (ref "LED73") (pin "2") (pinfunction "BLUE_2") (pintype "bidirectional"))
    )
    (net (code "102") (name "/N$LEDB74_IC5_PIN47") (class "Default")
      (node (ref "IC5") (pin "47") (pinfunction "OUTB9_47") (pintype "bidirectional"))
      (node (ref "LED74") (pin "2") (pinfunction "BLUE_2") (pintype "bidirectional"))
    )
    (net (code "103") (name "/N$LEDB75_IC5_PIN41") (class "Default")
      (node (ref "IC5") (pin "41") (pinfunction "OUTB14_41") (pintype "bidirectional"))
      (node (ref "LED75") (pin "2") (pinfunction "BLUE_2") (pintype "bidirectional"))
    )
    (net (code "104") (name "/N$LEDB76_IC5_PIN35") (class "Default")
      (node (ref "IC5") (pin "35") (pinfunction "OUTB15_35") (pintype "bidirectional"))
      (node (ref "LED76") (pin "2") (pinfunction "BLUE_2") (pintype "bidirectional"))
    )
    (net (code "105") (name "/N$LEDB77_IC5_PIN50") (class "Default")
      (node (ref "IC5") (pin "50") (pinfunction "OUTB12_50") (pintype "bidirectional"))
      (node (ref "LED77") (pin "2") (pinfunction "BLUE_2") (pintype "bidirectional"))
    )
    (net (code "106") (name "/N$LEDB78_IC5_PIN44") (class "Default")
      (node (ref "IC5") (pin "44") (pinfunction "OUTB13_44") (pintype "bidirectional"))
      (node (ref "LED78") (pin "2") (pinfunction "BLUE_2") (pintype "bidirectional"))
    )
    (net (code "107") (name "/N$LEDB79_IC5_PIN38") (class "Default")
      (node (ref "IC5") (pin "38") (pinfunction "OUTB10_38") (pintype "bidirectional"))
      (node (ref "LED79") (pin "2") (pinfunction "BLUE_2") (pintype "bidirectional"))
    )
    (net (code "108") (name "/N$LEDB80_IC5_PIN32") (class "Default")
      (node (ref "IC5") (pin "32") (pinfunction "OUTB11_32") (pintype "bidirectional"))
      (node (ref "LED80") (pin "2") (pinfunction "BLUE_2") (pintype "bidirectional"))
    )
    (net (code "109") (name "/N$LEDB81_IC6_PIN4") (class "Default")
      (node (ref "IC6") (pin "4") (pinfunction "OUTB4_4") (pintype "bidirectional"))
      (node (ref "LED81") (pin "2") (pinfunction "BLUE_2") (pintype "bidirectional"))
    )
    (net (code "110") (name "/N$LEDB82_IC6_PIN10") (class "Default")
      (node (ref "IC6") (pin "10") (pinfunction "OUTB5_10") (pintype "bidirectional"))
      (node (ref "LED82") (pin "2") (pinfunction "BLUE_2") (pintype "bidirectional"))
    )
    (net (code "111") (name "/N$LEDB83_IC6_PIN16") (class "Default")
      (node (ref "IC6") (pin "16") (pinfunction "OUTB2_16") (pintype "bidirectional"))
      (node (ref "LED83") (pin "2") (pinfunction "BLUE_2") (pintype "bidirectional"))
    )
    (net (code "112") (name "/N$LEDB84_IC6_PIN22") (class "Default")
      (node (ref "IC6") (pin "22") (pinfunction "OUTB3_22") (pintype "bidirectional"))
      (node (ref "LED84") (pin "2") (pinfunction "BLUE_2") (pintype "bidirectional"))
    )
    (net (code "113") (name "/N$LEDB85_IC6_PIN7") (class "Default")
      (node (ref "IC6") (pin "7") (pinfunction "OUTB0_7") (pintype "bidirectional"))
      (node (ref "LED85") (pin "2") (pinfunction "BLUE_2") (pintype "bidirectional"))
    )
    (net (code "114") (name "/N$LEDB86_IC6_PIN13") (class "Default")
      (node (ref "IC6") (pin "13") (pinfunction "OUTB1_13") (pintype "bidirectional"))
      (node (ref "LED86") (pin "2") (pinfunction "BLUE_2") (pintype "bidirectional"))
    )
    (net (code "115") (name "/N$LEDB87_IC6_PIN19") (class "Default")
      (node (ref "IC6") (pin "19") (pinfunction "OUTB6_19") (pintype "bidirectional"))
      (node (ref "LED87") (pin "2") (pinfunction "BLUE_2") (pintype "bidirectional"))
    )
    (net (code "116") (name "/N$LEDB88_IC6_PIN25") (class "Default")
      (node (ref "IC6") (pin "25") (pinfunction "OUTB7_25") (pintype "bidirectional"))
      (node (ref "LED88") (pin "2") (pinfunction "BLUE_2") (pintype "bidirectional"))
    )
    (net (code "117") (name "/N$LEDB89_IC6_PIN53") (class "Default")
      (node (ref "IC6") (pin "53") (pinfunction "OUTB8_53") (pintype "bidirectional"))
      (node (ref "LED89") (pin "2") (pinfunction "BLUE_2") (pintype "bidirectional"))
    )
    (net (code "118") (name "/N$LEDB90_IC6_PIN47") (class "Default")
      (node (ref "IC6") (pin "47") (pinfunction "OUTB9_47") (pintype "bidirectional"))
      (node (ref "LED90") (pin "2") (pinfunction "BLUE_2") (pintype "bidirectional"))
    )
    (net (code "119") (name "/N$LEDB91_IC6_PIN41") (class "Default")
      (node (ref "IC6") (pin "41") (pinfunction "OUTB14_41") (pintype "bidirectional"))
      (node (ref "LED91") (pin "2") (pinfunction "BLUE_2") (pintype "bidirectional"))
    )
    (net (code "120") (name "/N$LEDB92_IC6_PIN35") (class "Default")
      (node (ref "IC6") (pin "35") (pinfunction "OUTB15_35") (pintype "bidirectional"))
      (node (ref "LED92") (pin "2") (pinfunction "BLUE_2") (pintype "bidirectional"))
    )
    (net (code "121") (name "/N$LEDB93_IC6_PIN50") (class "Default")
      (node (ref "IC6") (pin "50") (pinfunction "OUTB12_50") (pintype "bidirectional"))
      (node (ref "LED93") (pin "2") (pinfunction "BLUE_2") (pintype "bidirectional"))
    )
    (net (code "122") (name "/N$LEDB94_IC6_PIN44") (class "Default")
      (node (ref "IC6") (pin "44") (pinfunction "OUTB13_44") (pintype "bidirectional"))
      (node (ref "LED94") (pin "2") (pinfunction "BLUE_2") (pintype "bidirectional"))
    )
    (net (code "123") (name "/N$LEDB95_IC6_PIN38") (class "Default")
      (node (ref "IC6") (pin "38") (pinfunction "OUTB10_38") (pintype "bidirectional"))
      (node (ref "LED95") (pin "2") (pinfunction "BLUE_2") (pintype "bidirectional"))
    )
    (net (code "124") (name "/N$LEDB96_IC6_PIN32") (class "Default")
      (node (ref "IC6") (pin "32") (pinfunction "OUTB11_32") (pintype "bidirectional"))
      (node (ref "LED96") (pin "2") (pinfunction "BLUE_2") (pintype "bidirectional"))
    )
    (net (code "125") (name "/N$LEDB97_IC7_PIN4") (class "Default")
      (node (ref "IC7") (pin "4") (pinfunction "OUTB4_4") (pintype "bidirectional"))
      (node (ref "LED97") (pin "2") (pinfunction "BLUE_2") (pintype "bidirectional"))
    )
    (net (code "126") (name "/N$LEDB98_IC7_PIN10") (class "Default")
      (node (ref "IC7") (pin "10") (pinfunction "OUTB5_10") (pintype "bidirectional"))
      (node (ref "LED98") (pin "2") (pinfunction "BLUE_2") (pintype "bidirectional"))
    )
    (net (code "127") (name "/N$LEDB99_IC7_PIN16") (class "Default")
      (node (ref "IC7") (pin "16") (pinfunction "OUTB2_16") (pintype "bidirectional"))
      (node (ref "LED99") (pin "2") (pinfunction "BLUE_2") (pintype "bidirectional"))
    )
    (net (code "128") (name "/N$LEDB100_IC7_PIN22") (class "Default")
      (node (ref "IC7") (pin "22") (pinfunction "OUTB3_22") (pintype "bidirectional"))
      (node (ref "LED100") (pin "2") (pinfunction "BLUE_2") (pintype "bidirectional"))
    )
    (net (code "129") (name "/N$LEDB101_IC7_PIN7") (class "Default")
      (node (ref "IC7") (pin "7") (pinfunction "OUTB0_7") (pintype "bidirectional"))
      (node (ref "LED101") (pin "2") (pinfunction "BLUE_2") (pintype "bidirectional"))
    )
    (net (code "130") (name "/N$LEDB102_IC7_PIN13") (class "Default")
      (node (ref "IC7") (pin "13") (pinfunction "OUTB1_13") (pintype "bidirectional"))
      (node (ref "LED102") (pin "2") (pinfunction "BLUE_2") (pintype "bidirectional"))
    )
    (net (code "131") (name "/N$LEDB103_IC7_PIN19") (class "Default")
      (node (ref "IC7") (pin "19") (pinfunction "OUTB6_19") (pintype "bidirectional"))
      (node (ref "LED103") (pin "2") (pinfunction "BLUE_2") (pintype "bidirectional"))
    )
    (net (code "132") (name "/N$LEDB104_IC7_PIN25") (class "Default")
      (node (ref "IC7") (pin "25") (pinfunction "OUTB7_25") (pintype "bidirectional"))
      (node (ref "LED104") (pin "2") (pinfunction "BLUE_2") (pintype "bidirectional"))
    )
    (net (code "133") (name "/N$LEDB105_IC7_PIN53") (class "Default")
      (node (ref "IC7") (pin "53") (pinfunction "OUTB8_53") (pintype "bidirectional"))
      (node (ref "LED105") (pin "2") (pinfunction "BLUE_2") (pintype "bidirectional"))
    )
    (net (code "134") (name "/N$LEDB106_IC7_PIN47") (class "Default")
      (node (ref "IC7") (pin "47") (pinfunction "OUTB9_47") (pintype "bidirectional"))
      (node (ref "LED106") (pin "2") (pinfunction "BLUE_2") (pintype "bidirectional"))
    )
    (net (code "135") (name "/N$LEDB107_IC7_PIN41") (class "Default")
      (node (ref "IC7") (pin "41") (pinfunction "OUTB14_41") (pintype "bidirectional"))
      (node (ref "LED107") (pin "2") (pinfunction "BLUE_2") (pintype "bidirectional"))
    )
    (net (code "136") (name "/N$LEDB108_IC7_PIN35") (class "Default")
      (node (ref "IC7") (pin "35") (pinfunction "OUTB15_35") (pintype "bidirectional"))
      (node (ref "LED108") (pin "2") (pinfunction "BLUE_2") (pintype "bidirectional"))
    )
    (net (code "137") (name "/N$LEDB109_IC7_PIN50") (class "Default")
      (node (ref "IC7") (pin "50") (pinfunction "OUTB12_50") (pintype "bidirectional"))
      (node (ref "LED109") (pin "2") (pinfunction "BLUE_2") (pintype "bidirectional"))
    )
    (net (code "138") (name "/N$LEDB110_IC7_PIN44") (class "Default")
      (node (ref "IC7") (pin "44") (pinfunction "OUTB13_44") (pintype "bidirectional"))
      (node (ref "LED110") (pin "2") (pinfunction "BLUE_2") (pintype "bidirectional"))
    )
    (net (code "139") (name "/N$LEDB111_IC7_PIN38") (class "Default")
      (node (ref "IC7") (pin "38") (pinfunction "OUTB10_38") (pintype "bidirectional"))
      (node (ref "LED111") (pin "2") (pinfunction "BLUE_2") (pintype "bidirectional"))
    )
    (net (code "140") (name "/N$LEDB112_IC7_PIN32") (class "Default")
      (node (ref "IC7") (pin "32") (pinfunction "OUTB11_32") (pintype "bidirectional"))
      (node (ref "LED112") (pin "2") (pinfunction "BLUE_2") (pintype "bidirectional"))
    )
    (net (code "141") (name "/N$LEDB113_IC8_PIN4") (class "Default")
      (node (ref "IC8") (pin "4") (pinfunction "OUTB4_4") (pintype "bidirectional"))
      (node (ref "LED113") (pin "2") (pinfunction "BLUE_2") (pintype "bidirectional"))
    )
    (net (code "142") (name "/N$LEDB114_IC8_PIN10") (class "Default")
      (node (ref "IC8") (pin "10") (pinfunction "OUTB5_10") (pintype "bidirectional"))
      (node (ref "LED114") (pin "2") (pinfunction "BLUE_2") (pintype "bidirectional"))
    )
    (net (code "143") (name "/N$LEDB115_IC8_PIN16") (class "Default")
      (node (ref "IC8") (pin "16") (pinfunction "OUTB2_16") (pintype "bidirectional"))
      (node (ref "LED115") (pin "2") (pinfunction "BLUE_2") (pintype "bidirectional"))
    )
    (net (code "144") (name "/N$LEDB116_IC8_PIN22") (class "Default")
      (node (ref "IC8") (pin "22") (pinfunction "OUTB3_22") (pintype "bidirectional"))
      (node (ref "LED116") (pin "2") (pinfunction "BLUE_2") (pintype "bidirectional"))
    )
    (net (code "145") (name "/N$LEDB117_IC8_PIN7") (class "Default")
      (node (ref "IC8") (pin "7") (pinfunction "OUTB0_7") (pintype "bidirectional"))
      (node (ref "LED117") (pin "2") (pinfunction "BLUE_2") (pintype "bidirectional"))
    )
    (net (code "146") (name "/N$LEDB118_IC8_PIN13") (class "Default")
      (node (ref "IC8") (pin "13") (pinfunction "OUTB1_13") (pintype "bidirectional"))
      (node (ref "LED118") (pin "2") (pinfunction "BLUE_2") (pintype "bidirectional"))
    )
    (net (code "147") (name "/N$LEDB119_IC8_PIN19") (class "Default")
      (node (ref "IC8") (pin "19") (pinfunction "OUTB6_19") (pintype "bidirectional"))
      (node (ref "LED119") (pin "2") (pinfunction "BLUE_2") (pintype "bidirectional"))
    )
    (net (code "148") (name "/N$LEDB120_IC8_PIN25") (class "Default")
      (node (ref "IC8") (pin "25") (pinfunction "OUTB7_25") (pintype "bidirectional"))
      (node (ref "LED120") (pin "2") (pinfunction "BLUE_2") (pintype "bidirectional"))
    )
    (net (code "149") (name "/N$LEDG1_IC1_PIN6") (class "Default")
      (node (ref "IC1") (pin "6") (pinfunction "OUTG4_6") (pintype "bidirectional"))
      (node (ref "LED1") (pin "1") (pinfunction "GREEN_1") (pintype "bidirectional"))
    )
    (net (code "150") (name "/N$LEDG2_IC1_PIN12") (class "Default")
      (node (ref "IC1") (pin "12") (pinfunction "OUTG5_12") (pintype "bidirectional"))
      (node (ref "LED2") (pin "1") (pinfunction "GREEN_1") (pintype "bidirectional"))
    )
    (net (code "151") (name "/N$LEDG3_IC1_PIN18") (class "Default")
      (node (ref "IC1") (pin "18") (pinfunction "OUTG2_18") (pintype "bidirectional"))
      (node (ref "LED3") (pin "1") (pinfunction "GREEN_1") (pintype "bidirectional"))
    )
    (net (code "152") (name "/N$LEDG4_IC1_PIN24") (class "Default")
      (node (ref "IC1") (pin "24") (pinfunction "OUTG3_24") (pintype "bidirectional"))
      (node (ref "LED4") (pin "1") (pinfunction "GREEN_1") (pintype "bidirectional"))
    )
    (net (code "153") (name "/N$LEDG5_IC1_PIN9") (class "Default")
      (node (ref "IC1") (pin "9") (pinfunction "OUTG0_9") (pintype "bidirectional"))
      (node (ref "LED5") (pin "1") (pinfunction "GREEN_1") (pintype "bidirectional"))
    )
    (net (code "154") (name "/N$LEDG6_IC1_PIN15") (class "Default")
      (node (ref "IC1") (pin "15") (pinfunction "OUTG1_15") (pintype "bidirectional"))
      (node (ref "LED6") (pin "1") (pinfunction "GREEN_1") (pintype "bidirectional"))
    )
    (net (code "155") (name "/N$LEDG7_IC1_PIN21") (class "Default")
      (node (ref "IC1") (pin "21") (pinfunction "OUTG6_21") (pintype "bidirectional"))
      (node (ref "LED7") (pin "1") (pinfunction "GREEN_1") (pintype "bidirectional"))
    )
    (net (code "156") (name "/N$LEDG8_IC1_PIN27") (class "Default")
      (node (ref "IC1") (pin "27") (pinfunction "OUTG7_27") (pintype "bidirectional"))
      (node (ref "LED8") (pin "1") (pinfunction "GREEN_1") (pintype "bidirectional"))
    )
    (net (code "157") (name "/N$LEDG9_IC1_PIN51") (class "Default")
      (node (ref "IC1") (pin "51") (pinfunction "OUTG8_51") (pintype "bidirectional"))
      (node (ref "LED9") (pin "1") (pinfunction "GREEN_1") (pintype "bidirectional"))
    )
    (net (code "158") (name "/N$LEDG10_IC1_PIN45") (class "Default")
      (node (ref "IC1") (pin "45") (pinfunction "OUTG9_45") (pintype "bidirectional"))
      (node (ref "LED10") (pin "1") (pinfunction "GREEN_1") (pintype "bidirectional"))
    )
    (net (code "159") (name "/N$LEDG11_IC1_PIN39") (class "Default")
      (node (ref "IC1") (pin "39") (pinfunction "OUTG14_39") (pintype "bidirectional"))
      (node (ref "LED11") (pin "1") (pinfunction "GREEN_1") (pintype "bidirectional"))
    )
    (net (code "160") (name "/N$LEDG12_IC1_PIN33") (class "Default")
      (node (ref "IC1") (pin "33") (pinfunction "OUTG15_33") (pintype "bidirectional"))
      (node (ref "LED12") (pin "1") (pinfunction "GREEN_1") (pintype "bidirectional"))
    )
    (net (code "161") (name "/N$LEDG13_IC1_PIN48") (class "Default")
      (node (ref "IC1") (pin "48") (pinfunction "OUTG12_48") (pintype "bidirectional"))
      (node (ref "LED13") (pin "1") (pinfunction "GREEN_1") (pintype "bidirectional"))
    )
    (net (code "162") (name "/N$LEDG14_IC1_PIN42") (class "Default")
      (node (ref "IC1") (pin "42") (pinfunction "OUTG13_42") (pintype "bidirectional"))
      (node (ref "LED14") (pin "1") (pinfunction "GREEN_1") (pintype "bidirectional"))
    )
    (net (code "163") (name "/N$LEDG15_IC1_PIN36") (class "Default")
      (node (ref "IC1") (pin "36") (pinfunction "OUTG10_36") (pintype "bidirectional"))
      (node (ref "LED15") (pin "1") (pinfunction "GREEN_1") (pintype "bidirectional"))
    )
    (net (code "164") (name "/N$LEDG16_IC1_PIN30") (class "Default")
      (node (ref "IC1") (pin "30") (pinfunction "OUTG11_30") (pintype "bidirectional"))
      (node (ref "LED16") (pin "1") (pinfunction "GREEN_1") (pintype "bidirectional"))
    )
    (net (code "165") (name "/N$LEDG17_IC2_PIN6") (class "Default")
      (node (ref "IC2") (pin "6") (pinfunction "OUTG4_6") (pintype "bidirectional"))
      (node (ref "LED17") (pin "1") (pinfunction "GREEN_1") (pintype "bidirectional"))
    )
    (net (code "166") (name "/N$LEDG18_IC2_PIN12") (class "Default")
      (node (ref "IC2") (pin "12") (pinfunction "OUTG5_12") (pintype "bidirectional"))
      (node (ref "LED18") (pin "1") (pinfunction "GREEN_1") (pintype "bidirectional"))
    )
    (net (code "167") (name "/N$LEDG19_IC2_PIN18") (class "Default")
      (node (ref "IC2") (pin "18") (pinfunction "OUTG2_18") (pintype "bidirectional"))
      (node (ref "LED19") (pin "1") (pinfunction "GREEN_1") (pintype "bidirectional"))
    )
    (net (code "168") (name "/N$LEDG20_IC2_PIN24") (class "Default")
      (node (ref "IC2") (pin "24") (pinfunction "OUTG3_24") (pintype "bidirectional"))
      (node (ref "LED20") (pin "1") (pinfunction "GREEN_1") (pintype "bidirectional"))
    )
    (net (code "169") (name "/N$LEDG21_IC2_PIN9") (class "Default")
      (node (ref "IC2") (pin "9") (pinfunction "OUTG0_9") (pintype "bidirectional"))
      (node (ref "LED21") (pin "1") (pinfunction "GREEN_1") (pintype "bidirectional"))
    )
    (net (code "170") (name "/N$LEDG22_IC2_PIN15") (class "Default")
      (node (ref "IC2") (pin "15") (pinfunction "OUTG1_15") (pintype "bidirectional"))
      (node (ref "LED22") (pin "1") (pinfunction "GREEN_1") (pintype "bidirectional"))
    )
    (net (code "171") (name "/N$LEDG23_IC2_PIN21") (class "Default")
      (node (ref "IC2") (pin "21") (pinfunction "OUTG6_21") (pintype "bidirectional"))
      (node (ref "LED23") (pin "1") (pinfunction "GREEN_1") (pintype "bidirectional"))
    )
    (net (code "172") (name "/N$LEDG24_IC2_PIN27") (class "Default")
      (node (ref "IC2") (pin "27") (pinfunction "OUTG7_27") (pintype "bidirectional"))
      (node (ref "LED24") (pin "1") (pinfunction "GREEN_1") (pintype "bidirectional"))
    )
    (net (code "173") (name "/N$LEDG25_IC2_PIN51") (class "Default")
      (node (ref "IC2") (pin "51") (pinfunction "OUTG8_51") (pintype "bidirectional"))
      (node (ref "LED25") (pin "1") (pinfunction "GREEN_1") (pintype "bidirectional"))
    )
    (net (code "174") (name "/N$LEDG26_IC2_PIN45") (class "Default")
      (node (ref "IC2") (pin "45") (pinfunction "OUTG9_45") (pintype "bidirectional"))
      (node (ref "LED26") (pin "1") (pinfunction "GREEN_1") (pintype "bidirectional"))
    )
    (net (code "175") (name "/N$LEDG27_IC2_PIN39") (class "Default")
      (node (ref "IC2") (pin "39") (pinfunction "OUTG14_39") (pintype "bidirectional"))
      (node (ref "LED27") (pin "1") (pinfunction "GREEN_1") (pintype "bidirectional"))
    )
    (net (code "176") (name "/N$LEDG28_IC2_PIN33") (class "Default")
      (node (ref "IC2") (pin "33") (pinfunction "OUTG15_33") (pintype "bidirectional"))
      (node (ref "LED28") (pin "1") (pinfunction "GREEN_1") (pintype "bidirectional"))
    )
    (net (code "177") (name "/N$LEDG29_IC2_PIN48") (class "Default")
      (node (ref "IC2") (pin "48") (pinfunction "OUTG12_48") (pintype "bidirectional"))
      (node (ref "LED29") (pin "1") (pinfunction "GREEN_1") (pintype "bidirectional"))
    )
    (net (code "178") (name "/N$LEDG30_IC2_PIN42") (class "Default")
      (node (ref "IC2") (pin "42") (pinfunction "OUTG13_42") (pintype "bidirectional"))
      (node (ref "LED30") (pin "1") (pinfunction "GREEN_1") (pintype "bidirectional"))
    )
    (net (code "179") (name "/N$LEDG31_IC2_PIN36") (class "Default")
      (node (ref "IC2") (pin "36") (pinfunction "OUTG10_36") (pintype "bidirectional"))
      (node (ref "LED31") (pin "1") (pinfunction "GREEN_1") (pintype "bidirectional"))
    )
    (net (code "180") (name "/N$LEDG32_IC2_PIN30") (class "Default")
      (node (ref "IC2") (pin "30") (pinfunction "OUTG11_30") (pintype "bidirectional"))
      (node (ref "LED32") (pin "1") (pinfunction "GREEN_1") (pintype "bidirectional"))
    )
    (net (code "181") (name "/N$LEDG33_IC3_PIN6") (class "Default")
      (node (ref "IC3") (pin "6") (pinfunction "OUTG4_6") (pintype "bidirectional"))
      (node (ref "LED33") (pin "1") (pinfunction "GREEN_1") (pintype "bidirectional"))
    )
    (net (code "182") (name "/N$LEDG34_IC3_PIN12") (class "Default")
      (node (ref "IC3") (pin "12") (pinfunction "OUTG5_12") (pintype "bidirectional"))
      (node (ref "LED34") (pin "1") (pinfunction "GREEN_1") (pintype "bidirectional"))
    )
    (net (code "183") (name "/N$LEDG35_IC3_PIN18") (class "Default")
      (node (ref "IC3") (pin "18") (pinfunction "OUTG2_18") (pintype "bidirectional"))
      (node (ref "LED35") (pin "1") (pinfunction "GREEN_1") (pintype "bidirectional"))
    )
    (net (code "184") (name "/N$LEDG36_IC3_PIN24") (class "Default")
      (node (ref "IC3") (pin "24") (pinfunction "OUTG3_24") (pintype "bidirectional"))
      (node (ref "LED36") (pin "1") (pinfunction "GREEN_1") (pintype "bidirectional"))
    )
    (net (code "185") (name "/N$LEDG37_IC3_PIN9") (class "Default")
      (node (ref "IC3") (pin "9") (pinfunction "OUTG0_9") (pintype "bidirectional"))
      (node (ref "LED37") (pin "1") (pinfunction "GREEN_1") (pintype "bidirectional"))
    )
    (net (code "186") (name "/N$LEDG38_IC3_PIN15") (class "Default")
      (node (ref "IC3") (pin "15") (pinfunction "OUTG1_15") (pintype "bidirectional"))
      (node (ref "LED38") (pin "1") (pinfunction "GREEN_1") (pintype "bidirectional"))
    )
    (net (code "187") (name "/N$LEDG39_IC3_PIN21") (class "Default")
      (node (ref "IC3") (pin "21") (pinfunction "OUTG6_21") (pintype "bidirectional"))
      (node (ref "LED39") (pin "1") (pinfunction "GREEN_1") (pintype "bidirectional"))
    )
    (net (code "188") (name "/N$LEDG40_IC3_PIN27") (class "Default")
      (node (ref "IC3") (pin "27") (pinfunction "OUTG7_27") (pintype "bidirectional"))
      (node (ref "LED40") (pin "1") (pinfunction "GREEN_1") (pintype "bidirectional"))
    )
    (net (code "189") (name "/N$LEDG41_IC3_PIN51") (class "Default")
      (node (ref "IC3") (pin "51") (pinfunction "OUTG8_51") (pintype "bidirectional"))
      (node (ref "LED41") (pin "1") (pinfunction "GREEN_1") (pintype "bidirectional"))
    )
    (net (code "190") (name "/N$LEDG42_IC3_PIN45") (class "Default")
      (node (ref "IC3") (pin "45") (pinfunction "OUTG9_45") (pintype "bidirectional"))
      (node (ref "LED42") (pin "1") (pinfunction "GREEN_1") (pintype "bidirectional"))
    )
    (net (code "191") (name "/N$LEDG43_IC3_PIN39") (class "Default")
      (node (ref "IC3") (pin "39") (pinfunction "OUTG14_39") (pintype "bidirectional"))
      (node (ref "LED43") (pin "1") (pinfunction "GREEN_1") (pintype "bidirectional"))
    )
    (net (code "192") (name "/N$LEDG44_IC3_PIN33") (class "Default")
      (node (ref "IC3") (pin "33") (pinfunction "OUTG15_33") (pintype "bidirectional"))
      (node (ref "LED44") (pin "1") (pinfunction "GREEN_1") (pintype "bidirectional"))
    )
    (net (code "193") (name "/N$LEDG45_IC3_PIN48") (class "Default")
      (node (ref "IC3") (pin "48") (pinfunction "OUTG12_48") (pintype "bidirectional"))
      (node (ref "LED45") (pin "1") (pinfunction "GREEN_1") (pintype "bidirectional"))
    )
    (net (code "194") (name "/N$LEDG46_IC3_PIN42") (class "Default")
      (node (ref "IC3") (pin "42") (pinfunction "OUTG13_42") (pintype "bidirectional"))
      (node (ref "LED46") (pin "1") (pinfunction "GREEN_1") (pintype "bidirectional"))
    )
    (net (code "195") (name "/N$LEDG47_IC3_PIN36") (class "Default")
      (node (ref "IC3") (pin "36") (pinfunction "OUTG10_36") (pintype "bidirectional"))
      (node (ref "LED47") (pin "1") (pinfunction "GREEN_1") (pintype "bidirectional"))
    )
    (net (code "196") (name "/N$LEDG48_IC3_PIN30") (class "Default")
      (node (ref "IC3") (pin "30") (pinfunction "OUTG11_30") (pintype "bidirectional"))
      (node (ref "LED48") (pin "1") (pinfunction "GREEN_1") (pintype "bidirectional"))
    )
    (net (code "197") (name "/N$LEDG49_IC4_PIN6") (class "Default")
      (node (ref "IC4") (pin "6") (pinfunction "OUTG4_6") (pintype "bidirectional"))
      (node (ref "LED49") (pin "1") (pinfunction "GREEN_1") (pintype "bidirectional"))
    )
    (net (code "198") (name "/N$LEDG50_IC4_PIN12") (class "Default")
      (node (ref "IC4") (pin "12") (pinfunction "OUTG5_12") (pintype "bidirectional"))
      (node (ref "LED50") (pin "1") (pinfunction "GREEN_1") (pintype "bidirectional"))
    )
    (net (code "199") (name "/N$LEDG51_IC4_PIN18") (class "Default")
      (node (ref "IC4") (pin "18") (pinfunction "OUTG2_18") (pintype "bidirectional"))
      (node (ref "LED51") (pin "1") (pinfunction "GREEN_1") (pintype "bidirectional"))
    )
    (net (code "200") (name "/N$LEDG52_IC4_PIN24") (class "Default")
      (node (ref "IC4") (pin "24") (pinfunction "OUTG3_24") (pintype "bidirectional"))
      (node (ref "LED52") (pin "1") (pinfunction "GREEN_1") (pintype "bidirectional"))
    )
    (net (code "201") (name "/N$LEDG53_IC4_PIN9") (class "Default")
      (node (ref "IC4") (pin "9") (pinfunction "OUTG0_9") (pintype "bidirectional"))
      (node (ref "LED53") (pin "1") (pinfunction "GREEN_1") (pintype "bidirectional"))
    )
    (net (code "202") (name "/N$LEDG54_IC4_PIN15") (class "Default")
      (node (ref "IC4") (pin "15") (pinfunction "OUTG1_15") (pintype "bidirectional"))
      (node (ref "LED54") (pin "1") (pinfunction "GREEN_1") (pintype "bidirectional"))
    )
    (net (code "203") (name "/N$LEDG55_IC4_PIN21") (class "Default")
      (node (ref "IC4") (pin "21") (pinfunction "OUTG6_21") (pintype "bidirectional"))
      (node (ref "LED55") (pin "1") (pinfunction "GREEN_1") (pintype "bidirectional"))
    )
    (net (code "204") (name "/N$LEDG56_IC4_PIN27") (class "Default")
      (node (ref "IC4") (pin "27") (pinfunction "OUTG7_27") (pintype "bidirectional"))
      (node (ref "LED56") (pin "1") (pinfunction "GREEN_1") (pintype "bidirectional"))
    )
    (net (code "205") (name "/N$LEDG57_IC4_PIN51") (class "Default")
      (node (ref "IC4") (pin "51") (pinfunction "OUTG8_51") (pintype "bidirectional"))
      (node (ref "LED57") (pin "1") (pinfunction "GREEN_1") (pintype "bidirectional"))
    )
    (net (code "206") (name "/N$LEDG58_IC4_PIN45") (class "Default")
      (node (ref "IC4") (pin "45") (pinfunction "OUTG9_45") (pintype "bidirectional"))
      (node (ref "LED58") (pin "1") (pinfunction "GREEN_1") (pintype "bidirectional"))
    )
    (net (code "207") (name "/N$LEDG59_IC4_PIN39") (class "Default")
      (node (ref "IC4") (pin "39") (pinfunction "OUTG14_39") (pintype "bidirectional"))
      (node (ref "LED59") (pin "1") (pinfunction "GREEN_1") (pintype "bidirectional"))
    )
    (net (code "208") (name "/N$LEDG60_IC4_PIN33") (class "Default")
      (node (ref "IC4") (pin "33") (pinfunction "OUTG15_33") (pintype "bidirectional"))
      (node (ref "LED60") (pin "1") (pinfunction "GREEN_1") (pintype "bidirectional"))
    )
    (net (code "209") (name "/N$LEDG61_IC4_PIN48") (class "Default")
      (node (ref "IC4") (pin "48") (pinfunction "OUTG12_48") (pintype "bidirectional"))
      (node (ref "LED61") (pin "1") (pinfunction "GREEN_1") (pintype "bidirectional"))
    )
    (net (code "210") (name "/N$LEDG62_IC4_PIN42") (class "Default")
      (node (ref "IC4") (pin "42") (pinfunction "OUTG13_42") (pintype "bidirectional"))
      (node (ref "LED62") (pin "1") (pinfunction "GREEN_1") (pintype "bidirectional"))
    )
    (net (code "211") (name "/N$LEDG63_IC4_PIN36") (class "Default")
      (node (ref "IC4") (pin "36") (pinfunction "OUTG10_36") (pintype "bidirectional"))
      (node (ref "LED63") (pin "1") (pinfunction "GREEN_1") (pintype "bidirectional"))
    )
    (net (code "212") (name "/N$LEDG64_IC4_PIN30") (class "Default")
      (node (ref "IC4") (pin "30") (pinfunction "OUTG11_30") (pintype "bidirectional"))
      (node (ref "LED64") (pin "1") (pinfunction "GREEN_1") (pintype "bidirectional"))
    )
    (net (code "213") (name "/N$LEDG65_IC5_PIN6") (class "Default")
      (node (ref "IC5") (pin "6") (pinfunction "OUTG4_6") (pintype "bidirectional"))
      (node (ref "LED65") (pin "1") (pinfunction "GREEN_1") (pintype "bidirectional"))
    )
    (net (code "214") (name "/N$LEDG66_IC5_PIN12") (class "Default")
      (node (ref "IC5") (pin "12") (pinfunction "OUTG5_12") (pintype "bidirectional"))
      (node (ref "LED66") (pin "1") (pinfunction "GREEN_1") (pintype "bidirectional"))
    )
    (net (code "215") (name "/N$LEDG67_IC5_PIN18") (class "Default")
      (node (ref "IC5") (pin "18") (pinfunction "OUTG2_18") (pintype "bidirectional"))
      (node (ref "LED67") (pin "1") (pinfunction "GREEN_1") (pintype "bidirectional"))
    )
    (net (code "216") (name "/N$LEDG68_IC5_PIN24") (class "Default")
      (node (ref "IC5") (pin "24") (pinfunction "OUTG3_24") (pintype "bidirectional"))
      (node (ref "LED68") (pin "1") (pinfunction "GREEN_1") (pintype "bidirectional"))
    )
    (net (code "217") (name "/N$LEDG69_IC5_PIN9") (class "Default")
      (node (ref "IC5") (pin "9") (pinfunction "OUTG0_9") (pintype "bidirectional"))
      (node (ref "LED69") (pin "1") (pinfunction "GREEN_1") (pintype "bidirectional"))
    )
    (net (code "218") (name "/N$LEDG70_IC5_PIN15") (class "Default")
      (node (ref "IC5") (pin "15") (pinfunction "OUTG1_15") (pintype "bidirectional"))
      (node (ref "LED70") (pin "1") (pinfunction "GREEN_1") (pintype "bidirectional"))
    )
    (net (code "219") (name "/N$LEDG71_IC5_PIN21") (class "Default")
      (node (ref "IC5") (pin "21") (pinfunction "OUTG6_21") (pintype "bidirectional"))
      (node (ref "LED71") (pin "1") (pinfunction "GREEN_1") (pintype "bidirectional"))
    )
    (net (code "220") (name "/N$LEDG72_IC5_PIN27") (class "Default")
      (node (ref "IC5") (pin "27") (pinfunction "OUTG7_27") (pintype "bidirectional"))
      (node (ref "LED72") (pin "1") (pinfunction "GREEN_1") (pintype "bidirectional"))
    )
    (net (code "221") (name "/N$LEDG73_IC5_PIN51") (class "Default")
      (node (ref "IC5") (pin "51") (pinfunction "OUTG8_51") (pintype "bidirectional"))
      (node (ref "LED73") (pin "1") (pinfunction "GREEN_1") (pintype "bidirectional"))
    )
    (net (code "222") (name "/N$LEDG74_IC5_PIN45") (class "Default")
      (node (ref "IC5") (pin "45") (pinfunction "OUTG9_45") (pintype "bidirectional"))
      (node (ref "LED74") (pin "1") (pinfunction "GREEN_1") (pintype "bidirectional"))
    )
    (net (code "223") (name "/N$LEDG75_IC5_PIN39") (class "Default")
      (node (ref "IC5") (pin "39") (pinfunction "OUTG14_39") (pintype "bidirectional"))
      (node (ref "LED75") (pin "1") (pinfunction "GREEN_1") (pintype "bidirectional"))
    )
    (net (code "224") (name "/N$LEDG76_IC5_PIN33") (class "Default")
      (node (ref "IC5") (pin "33") (pinfunction "OUTG15_33") (pintype "bidirectional"))
      (node (ref "LED76") (pin "1") (pinfunction "GREEN_1") (pintype "bidirectional"))
    )
    (net (code "225") (name "/N$LEDG77_IC5_PIN48") (class "Default")
      (node (ref "IC5") (pin "48") (pinfunction "OUTG12_48") (pintype "bidirectional"))
      (node (ref "LED77") (pin "1") (pinfunction "GREEN_1") (pintype "bidirectional"))
    )
    (net (code "226") (name "/N$LEDG78_IC5_PIN42") (class "Default")
      (node (ref "IC5") (pin "42") (pinfunction "OUTG13_42") (pintype "bidirectional"))
      (node (ref "LED78") (pin "1") (pinfunction "GREEN_1") (pintype "bidirectional"))
    )
    (net (code "227") (name "/N$LEDG79_IC5_PIN36") (class "Default")
      (node (ref "IC5") (pin "36") (pinfunction "OUTG10_36") (pintype "bidirectional"))
      (node (ref "LED79") (pin "1") (pinfunction "GREEN_1") (pintype "bidirectional"))
    )
    (net (code "228") (name "/N$LEDG80_IC5_PIN30") (class "Default")
      (node (ref "IC5") (pin "30") (pinfunction "OUTG11_30") (pintype "bidirectional"))
      (node (ref "LED80") (pin "1") (pinfunction "GREEN_1") (pintype "bidirectional"))
    )
    (net (code "229") (name "/N$LEDG81_IC6_PIN6") (class "Default")
      (node (ref "IC6") (pin "6") (pinfunction "OUTG4_6") (pintype "bidirectional"))
      (node (ref "LED81") (pin "1") (pinfunction "GREEN_1") (pintype "bidirectional"))
    )
    (net (code "230") (name "/N$LEDG82_IC6_PIN12") (class "Default")
      (node (ref "IC6") (pin "12") (pinfunction "OUTG5_12") (pintype "bidirectional"))
      (node (ref "LED82") (pin "1") (pinfunction "GREEN_1") (pintype "bidirectional"))
    )
    (net (code "231") (name "/N$LEDG83_IC6_PIN18") (class "Default")
      (node (ref "IC6") (pin "18") (pinfunction "OUTG2_18") (pintype "bidirectional"))
      (node (ref "LED83") (pin "1") (pinfunction "GREEN_1") (pintype "bidirectional"))
    )
    (net (code "232") (name "/N$LEDG84_IC6_PIN24") (class "Default")
      (node (ref "IC6") (pin "24") (pinfunction "OUTG3_24") (pintype "bidirectional"))
      (node (ref "LED84") (pin "1") (pinfunction "GREEN_1") (pintype "bidirectional"))
    )
    (net (code "233") (name "/N$LEDG85_IC6_PIN9") (class "Default")
      (node (ref "IC6") (pin "9") (pinfunction "OUTG0_9") (pintype "bidirectional"))
      (node (ref "LED85") (pin "1") (pinfunction "GREEN_1") (pintype "bidirectional"))
    )
    (net (code "234") (name "/N$LEDG86_IC6_PIN15") (class "Default")
      (node (ref "IC6") (pin "15") (pinfunction "OUTG1_15") (pintype "bidirectional"))
      (node (ref "LED86") (pin "1") (pinfunction "GREEN_1") (pintype "bidirectional"))
    )
    (net (code "235") (name "/N$LEDG87_IC6_PIN21") (class "Default")
      (node (ref "IC6") (pin "21") (pinfunction "OUTG6_21") (pintype "bidirectional"))
      (node (ref "LED87") (pin "1") (pinfunction "GREEN_1") (pintype "bidirectional"))
    )
    (net (code "236") (name "/N$LEDG88_IC6_PIN27") (class "Default")
      (node (ref "IC6") (pin "27") (pinfunction "OUTG7_27") (pintype "bidirectional"))
      (node (ref "LED88") (pin "1") (pinfunction "GREEN_1") (pintype "bidirectional"))
    )
    (net (code "237") (name "/N$LEDG89_IC6_PIN51") (class "Default")
      (node (ref "IC6") (pin "51") (pinfunction "OUTG8_51") (pintype "bidirectional"))
      (node (ref "LED89") (pin "1") (pinfunction "GREEN_1") (pintype "bidirectional"))
    )
    (net (code "238") (name "/N$LEDG90_IC6_PIN45") (class "Default")
      (node (ref "IC6") (pin "45") (pinfunction "OUTG9_45") (pintype "bidirectional"))
      (node (ref "LED90") (pin "1") (pinfunction "GREEN_1") (pintype "bidirectional"))
    )
    (net (code "239") (name "/N$LEDG91_IC6_PIN39") (class "Default")
      (node (ref "IC6") (pin "39") (pinfunction "OUTG14_39") (pintype "bidirectional"))
      (node (ref "LED91") (pin "1") (pinfunction "GREEN_1") (pintype "bidirectional"))
    )
    (net (code "240") (name "/N$LEDG92_IC6_PIN33") (class "Default")
      (node (ref "IC6") (pin "33") (pinfunction "OUTG15_33") (pintype "bidirectional"))
      (node (ref "LED92") (pin "1") (pinfunction "GREEN_1") (pintype "bidirectional"))
    )
    (net (code "241") (name "/N$LEDG93_IC6_PIN48") (class "Default")
      (node (ref "IC6") (pin "48") (pinfunction "OUTG12_48") (pintype "bidirectional"))
      (node (ref "LED93") (pin "1") (pinfunction "GREEN_1") (pintype "bidirectional"))
    )
    (net (code "242") (name "/N$LEDG94_IC6_PIN42") (class "Default")
      (node (ref "IC6") (pin "42") (pinfunction "OUTG13_42") (pintype "bidirectional"))
      (node (ref "LED94") (pin "1") (pinfunction "GREEN_1") (pintype "bidirectional"))
    )
    (net (code "243") (name "/N$LEDG95_IC6_PIN36") (class "Default")
      (node (ref "IC6") (pin "36") (pinfunction "OUTG10_36") (pintype "bidirectional"))
      (node (ref "LED95") (pin "1") (pinfunction "GREEN_1") (pintype "bidirectional"))
    )
    (net (code "244") (name "/N$LEDG96_IC6_PIN30") (class "Default")
      (node (ref "IC6") (pin "30") (pinfunction "OUTG11_30") (pintype "bidirectional"))
      (node (ref "LED96") (pin "1") (pinfunction "GREEN_1") (pintype "bidirectional"))
    )
    (net (code "245") (name "/N$LEDG97_IC7_PIN6") (class "Default")
      (node (ref "IC7") (pin "6") (pinfunction "OUTG4_6") (pintype "bidirectional"))
      (node (ref "LED97") (pin "1") (pinfunction "GREEN_1") (pintype "bidirectional"))
    )
    (net (code "246") (name "/N$LEDG98_IC7_PIN12") (class "Default")
      (node (ref "IC7") (pin "12") (pinfunction "OUTG5_12") (pintype "bidirectional"))
      (node (ref "LED98") (pin "1") (pinfunction "GREEN_1") (pintype "bidirectional"))
    )
    (net (code "247") (name "/N$LEDG99_IC7_PIN18") (class "Default")
      (node (ref "IC7") (pin "18") (pinfunction "OUTG2_18") (pintype "bidirectional"))
      (node (ref "LED99") (pin "1") (pinfunction "GREEN_1") (pintype "bidirectional"))
    )
    (net (code "248") (name "/N$LEDG100_IC7_PIN24") (class "Default")
      (node (ref "IC7") (pin "24") (pinfunction "OUTG3_24") (pintype "bidirectional"))
      (node (ref "LED100") (pin "1") (pinfunction "GREEN_1") (pintype "bidirectional"))
    )
    (net (code "249") (name "/N$LEDG101_IC7_PIN9") (class "Default")
      (node (ref "IC7") (pin "9") (pinfunction "OUTG0_9") (pintype "bidirectional"))
      (node (ref "LED101") (pin "1") (pinfunction "GREEN_1") (pintype "bidirectional"))
    )
    (net (code "250") (name "/N$LEDG102_IC7_PIN15") (class "Default")
      (node (ref "IC7") (pin "15") (pinfunction "OUTG1_15") (pintype "bidirectional"))
      (node (ref "LED102") (pin "1") (pinfunction "GREEN_1") (pintype "bidirectional"))
    )
    (net (code "251") (name "/N$LEDG103_IC7_PIN21") (class "Default")
      (node (ref "IC7") (pin "21") (pinfunction "OUTG6_21") (pintype "bidirectional"))
      (node (ref "LED103") (pin "1") (pinfunction "GREEN_1") (pintype "bidirectional"))
    )
    (net (code "252") (name "/N$LEDG104_IC7_PIN27") (class "Default")
      (node (ref "IC7") (pin "27") (pinfunction "OUTG7_27") (pintype "bidirectional"))
      (node (ref "LED104") (pin "1") (pinfunction "GREEN_1") (pintype "bidirectional"))
    )
    (net (code "253") (name "/N$LEDG105_IC7_PIN51") (class "Default")
      (node (ref "IC7") (pin "51") (pinfunction "OUTG8_51") (pintype "bidirectional"))
      (node (ref "LED105") (pin "1") (pinfunction "GREEN_1") (pintype "bidirectional"))
    )
    (net (code "254") (name "/N$LEDG106_IC7_PIN45") (class "Default")
      (node (ref "IC7") (pin "45") (pinfunction "OUTG9_45") (pintype "bidirectional"))
      (node (ref "LED106") (pin "1") (pinfunction "GREEN_1") (pintype "bidirectional"))
    )
    (net (code "255") (name "/N$LEDG107_IC7_PIN39") (class "Default")
      (node (ref "IC7") (pin "39") (pinfunction "OUTG14_39") (pintype "bidirectional"))
      (node (ref "LED107") (pin "1") (pinfunction "GREEN_1") (pintype "bidirectional"))
    )
    (net (code "256") (name "/N$LEDG108_IC7_PIN33") (class "Default")
      (node (ref "IC7") (pin "33") (pinfunction "OUTG15_33") (pintype "bidirectional"))
      (node (ref "LED108") (pin "1") (pinfunction "GREEN_1") (pintype "bidirectional"))
    )
    (net (code "257") (name "/N$LEDG109_IC7_PIN48") (class "Default")
      (node (ref "IC7") (pin "48") (pinfunction "OUTG12_48") (pintype "bidirectional"))
      (node (ref "LED109") (pin "1") (pinfunction "GREEN_1") (pintype "bidirectional"))
    )
    (net (code "258") (name "/N$LEDG110_IC7_PIN42") (class "Default")
      (node (ref "IC7") (pin "42") (pinfunction "OUTG13_42") (pintype "bidirectional"))
      (node (ref "LED110") (pin "1") (pinfunction "GREEN_1") (pintype "bidirectional"))
    )
    (net (code "259") (name "/N$LEDG111_IC7_PIN36") (class "Default")
      (node (ref "IC7") (pin "36") (pinfunction "OUTG10_36") (pintype "bidirectional"))
      (node (ref "LED111") (pin "1") (pinfunction "GREEN_1") (pintype "bidirectional"))
    )
    (net (code "260") (name "/N$LEDG112_IC7_PIN30") (class "Default")
      (node (ref "IC7") (pin "30") (pinfunction "OUTG11_30") (pintype "bidirectional"))
      (node (ref "LED112") (pin "1") (pinfunction "GREEN_1") (pintype "bidirectional"))
    )
    (net (code "261") (name "/N$LEDG113_IC8_PIN6") (class "Default")
      (node (ref "IC8") (pin "6") (pinfunction "OUTG4_6") (pintype "bidirectional"))
      (node (ref "LED113") (pin "1") (pinfunction "GREEN_1") (pintype "bidirectional"))
    )
    (net (code "262") (name "/N$LEDG114_IC8_PIN12") (class "Default")
      (node (ref "IC8") (pin "12") (pinfunction "OUTG5_12") (pintype "bidirectional"))
      (node (ref "LED114") (pin "1") (pinfunction "GREEN_1") (pintype "bidirectional"))
    )
    (net (code "263") (name "/N$LEDG115_IC8_PIN18") (class "Default")
      (node (ref "IC8") (pin "18") (pinfunction "OUTG2_18") (pintype "bidirectional"))
      (node (ref "LED115") (pin "1") (pinfunction "GREEN_1") (pintype "bidirectional"))
    )
    (net (code "264") (name "/N$LEDG116_IC8_PIN24") (class "Default")
      (node (ref "IC8") (pin "24") (pinfunction "OUTG3_24") (pintype "bidirectional"))
      (node (ref "LED116") (pin "1") (pinfunction "GREEN_1") (pintype "bidirectional"))
    )
    (net (code "265") (name "/N$LEDG117_IC8_PIN9") (class "Default")
      (node (ref "IC8") (pin "9") (pinfunction "OUTG0_9") (pintype "bidirectional"))
      (node (ref "LED117") (pin "1") (pinfunction "GREEN_1") (pintype "bidirectional"))
    )
    (net (code "266") (name "/N$LEDG118_IC8_PIN15") (class "Default")
      (node (ref "IC8") (pin "15") (pinfunction "OUTG1_15") (pintype "bidirectional"))
      (node (ref "LED118") (pin "1") (pinfunction "GREEN_1") (pintype "bidirectional"))
    )
    (net (code "267") (name "/N$LEDG119_IC8_PIN21") (class "Default")
      (node (ref "IC8") (pin "21") (pinfunction "OUTG6_21") (pintype "bidirectional"))
      (node (ref "LED119") (pin "1") (pinfunction "GREEN_1") (pintype "bidirectional"))
    )
    (net (code "268") (name "/N$LEDG120_IC8_PIN27") (class "Default")
      (node (ref "IC8") (pin "27") (pinfunction "OUTG7_27") (pintype "bidirectional"))
      (node (ref "LED120") (pin "1") (pinfunction "GREEN_1") (pintype "bidirectional"))
    )
    (net (code "269") (name "/N$LEDR1_IC1_PIN5") (class "Default")
      (node (ref "IC1") (pin "5") (pinfunction "OUTR4_5") (pintype "bidirectional"))
      (node (ref "LED1") (pin "4") (pinfunction "RED_4") (pintype "bidirectional"))
    )
    (net (code "270") (name "/N$LEDR2_IC1_PIN11") (class "Default")
      (node (ref "IC1") (pin "11") (pinfunction "OUTR5_11") (pintype "bidirectional"))
      (node (ref "LED2") (pin "4") (pinfunction "RED_4") (pintype "bidirectional"))
    )
    (net (code "271") (name "/N$LEDR3_IC1_PIN17") (class "Default")
      (node (ref "IC1") (pin "17") (pinfunction "OUTR2_17") (pintype "bidirectional"))
      (node (ref "LED3") (pin "4") (pinfunction "RED_4") (pintype "bidirectional"))
    )
    (net (code "272") (name "/N$LEDR4_IC1_PIN23") (class "Default")
      (node (ref "IC1") (pin "23") (pinfunction "OUTR3_23") (pintype "bidirectional"))
      (node (ref "LED4") (pin "4") (pinfunction "RED_4") (pintype "bidirectional"))
    )
    (net (code "273") (name "/N$LEDR5_IC1_PIN8") (class "Default")
      (node (ref "IC1") (pin "8") (pinfunction "OUTR0_8") (pintype "bidirectional"))
      (node (ref "LED5") (pin "4") (pinfunction "RED_4") (pintype "bidirectional"))
    )
    (net (code "274") (name "/N$LEDR6_IC1_PIN14") (class "Default")
      (node (ref "IC1") (pin "14") (pinfunction "OUTR1_14") (pintype "bidirectional"))
      (node (ref "LED6") (pin "4") (pinfunction "RED_4") (pintype "bidirectional"))
    )
    (net (code "275") (name "/N$LEDR7_IC1_PIN20") (class "Default")
      (node (ref "IC1") (pin "20") (pinfunction "OUTR6_20") (pintype "bidirectional"))
      (node (ref "LED7") (pin "4") (pinfunction "RED_4") (pintype "bidirectional"))
    )
    (net (code "276") (name "/N$LEDR8_IC1_PIN26") (class "Default")
      (node (ref "IC1") (pin "26") (pinfunction "OUTR7_26") (pintype "bidirectional"))
      (node (ref "LED8") (pin "4") (pinfunction "RED_4") (pintype "bidirectional"))
    )
    (net (code "277") (name "/N$LEDR9_IC1_PIN52") (class "Default")
      (node (ref "IC1") (pin "52") (pinfunction "OUTR8_52") (pintype "bidirectional"))
      (node (ref "LED9") (pin "4") (pinfunction "RED_4") (pintype "bidirectional"))
    )
    (net (code "278") (name "/N$LEDR10_IC1_PIN46") (class "Default")
      (node (ref "IC1") (pin "46") (pinfunction "OUTR9_46") (pintype "bidirectional"))
      (node (ref "LED10") (pin "4") (pinfunction "RED_4") (pintype "bidirectional"))
    )
    (net (code "279") (name "/N$LEDR11_IC1_PIN40") (class "Default")
      (node (ref "IC1") (pin "40") (pinfunction "OUTR14_40") (pintype "bidirectional"))
      (node (ref "LED11") (pin "4") (pinfunction "RED_4") (pintype "bidirectional"))
    )
    (net (code "280") (name "/N$LEDR12_IC1_PIN34") (class "Default")
      (node (ref "IC1") (pin "34") (pinfunction "OUTR15_34") (pintype "bidirectional"))
      (node (ref "LED12") (pin "4") (pinfunction "RED_4") (pintype "bidirectional"))
    )
    (net (code "281") (name "/N$LEDR13_IC1_PIN49") (class "Default")
      (node (ref "IC1") (pin "49") (pinfunction "OUTR12_49") (pintype "bidirectional"))
      (node (ref "LED13") (pin "4") (pinfunction "RED_4") (pintype "bidirectional"))
    )
    (net (code "282") (name "/N$LEDR14_IC1_PIN43") (class "Default")
      (node (ref "IC1") (pin "43") (pinfunction "OUTR13_43") (pintype "bidirectional"))
      (node (ref "LED14") (pin "4") (pinfunction "RED_4") (pintype "bidirectional"))
    )
    (net (code "283") (name "/N$LEDR15_IC1_PIN37") (class "Default")
      (node (ref "IC1") (pin "37") (pinfunction "OUTR10_37") (pintype "bidirectional"))
      (node (ref "LED15") (pin "4") (pinfunction "RED_4") (pintype "bidirectional"))
    )
    (net (code "284") (name "/N$LEDR16_IC1_PIN31") (class "Default")
      (node (ref "IC1") (pin "31") (pinfunction "OUTR11_31") (pintype "bidirectional"))
      (node (ref "LED16") (pin "4") (pinfunction "RED_4") (pintype "bidirectional"))
    )
    (net (code "285") (name "/N$LEDR17_IC2_PIN5") (class "Default")
      (node (ref "IC2") (pin "5") (pinfunction "OUTR4_5") (pintype "bidirectional"))
      (node (ref "LED17") (pin "4") (pinfunction "RED_4") (pintype "bidirectional"))
    )
    (net (code "286") (name "/N$LEDR18_IC2_PIN11") (class "Default")
      (node (ref "IC2") (pin "11") (pinfunction "OUTR5_11") (pintype "bidirectional"))
      (node (ref "LED18") (pin "4") (pinfunction "RED_4") (pintype "bidirectional"))
    )
    (net (code "287") (name "/N$LEDR19_IC2_PIN17") (class "Default")
      (node (ref "IC2") (pin "17") (pinfunction "OUTR2_17") (pintype "bidirectional"))
      (node (ref "LED19") (pin "4") (pinfunction "RED_4") (pintype "bidirectional"))
    )
    (net (code "288") (name "/N$LEDR20_IC2_PIN23") (class "Default")
      (node (ref "IC2") (pin "23") (pinfunction "OUTR3_23") (pintype "bidirectional"))
      (node (ref "LED20") (pin "4") (pinfunction "RED_4") (pintype "bidirectional"))
    )
    (net (code "289") (name "/N$LEDR21_IC2_PIN8") (class "Default")
      (node (ref "IC2") (pin "8") (pinfunction "OUTR0_8") (pintype "bidirectional"))
      (node (ref "LED21") (pin "4") (pinfunction "RED_4") (pintype "bidirectional"))
    )
    (net (code "290") (name "/N$LEDR22_IC2_PIN14") (class "Default")
      (node (ref "IC2") (pin "14") (pinfunction "OUTR1_14") (pintype "bidirectional"))
      (node (ref "LED22") (pin "4") (pinfunction "RED_4") (pintype "bidirectional"))
    )
    (net (code "291") (name "/N$LEDR23_IC2_PIN20") (class "Default")
      (node (ref "IC2") (pin "20") (pinfunction "OUTR6_20") (pintype "bidirectional"))
      (node (ref "LED23") (pin "4") (pinfunction "RED_4") (pintype "bidirectional"))
    )
    (net (code "292") (name "/N$LEDR24_IC2_PIN26") (class "Default")
      (node (ref "IC2") (pin "26") (pinfunction "OUTR7_26") (pintype "bidirectional"))
      (node (ref "LED24") (pin "4") (pinfunction "RED_4") (pintype "bidirectional"))
    )
    (net (code "293") (name "/N$LEDR25_IC2_PIN52") (class "Default")
      (node (ref "IC2") (pin "52") (pinfunction "OUTR8_52") (pintype "bidirectional"))
      (node (ref "LED25") (pin "4") (pinfunction "RED_4") (pintype "bidirectional"))
    )
    (net (code "294") (name "/N$LEDR26_IC2_PIN46") (class "Default")
      (node (ref "IC2") (pin "46") (pinfunction "OUTR9_46") (pintype "bidirectional"))
      (node (ref "LED26") (pin "4") (pinfunction "RED_4") (pintype "bidirectional"))
    )
    (net (code "295") (name "/N$LEDR27_IC2_PIN40") (class "Default")
      (node (ref "IC2") (pin "40") (pinfunction "OUTR14_40") (pintype "bidirectional"))
      (node (ref "LED27") (pin "4") (pinfunction "RED_4") (pintype "bidirectional"))
    )
    (net (code "296") (name "/N$LEDR28_IC2_PIN34") (class "Default")
      (node (ref "IC2") (pin "34") (pinfunction "OUTR15_34") (pintype "bidirectional"))
      (node (ref "LED28") (pin "4") (pinfunction "RED_4") (pintype "bidirectional"))
    )
    (net (code "297") (name "/N$LEDR29_IC2_PIN49") (class "Default")
      (node (ref "IC2") (pin "49") (pinfunction "OUTR12_49") (pintype "bidirectional"))
      (node (ref "LED29") (pin "4") (pinfunction "RED_4") (pintype "bidirectional"))
    )
    (net (code "298") (name "/N$LEDR30_IC2_PIN43") (class "Default")
      (node (ref "IC2") (pin "43") (pinfunction "OUTR13_43") (pintype "bidirectional"))
      (node (ref "LED30") (pin "4") (pinfunction "RED_4") (pintype "bidirectional"))
    )
    (net (code "299") (name "/N$LEDR31_IC2_PIN37") (class "Default")
      (node (ref "IC2") (pin "37") (pinfunction "OUTR10_37") (pintype "bidirectional"))
      (node (ref "LED31") (pin "4") (pinfunction "RED_4") (pintype "bidirectional"))
    )
    (net (code "300") (name "/N$LEDR32_IC2_PIN31") (class "Default")
      (node (ref "IC2") (pin "31") (pinfunction "OUTR11_31") (pintype "bidirectional"))
      (node (ref "LED32") (pin "4") (pinfunction "RED_4") (pintype "bidirectional"))
    )
    (net (code "301") (name "/N$LEDR33_IC3_PIN5") (class "Default")
      (node (ref "IC3") (pin "5") (pinfunction "OUTR4_5") (pintype "bidirectional"))
      (node (ref "LED33") (pin "4") (pinfunction "RED_4") (pintype "bidirectional"))
    )
    (net (code "302") (name "/N$LEDR34_IC3_PIN11") (class "Default")
      (node (ref "IC3") (pin "11") (pinfunction "OUTR5_11") (pintype "bidirectional"))
      (node (ref "LED34") (pin "4") (pinfunction "RED_4") (pintype "bidirectional"))
    )
    (net (code "303") (name "/N$LEDR35_IC3_PIN17") (class "Default")
      (node (ref "IC3") (pin "17") (pinfunction "OUTR2_17") (pintype "bidirectional"))
      (node (ref "LED35") (pin "4") (pinfunction "RED_4") (pintype "bidirectional"))
    )
    (net (code "304") (name "/N$LEDR36_IC3_PIN23") (class "Default")
      (node (ref "IC3") (pin "23") (pinfunction "OUTR3_23") (pintype "bidirectional"))
      (node (ref "LED36") (pin "4") (pinfunction "RED_4") (pintype "bidirectional"))
    )
    (net (code "305") (name "/N$LEDR37_IC3_PIN8") (class "Default")
      (node (ref "IC3") (pin "8") (pinfunction "OUTR0_8") (pintype "bidirectional"))
      (node (ref "LED37") (pin "4") (pinfunction "RED_4") (pintype "bidirectional"))
    )
    (net (code "306") (name "/N$LEDR38_IC3_PIN14") (class "Default")
      (node (ref "IC3") (pin "14") (pinfunction "OUTR1_14") (pintype "bidirectional"))
      (node (ref "LED38") (pin "4") (pinfunction "RED_4") (pintype "bidirectional"))
    )
    (net (code "307") (name "/N$LEDR39_IC3_PIN20") (class "Default")
      (node (ref "IC3") (pin "20") (pinfunction "OUTR6_20") (pintype "bidirectional"))
      (node (ref "LED39") (pin "4") (pinfunction "RED_4") (pintype "bidirectional"))
    )
    (net (code "308") (name "/N$LEDR40_IC3_PIN26") (class "Default")
      (node (ref "IC3") (pin "26") (pinfunction "OUTR7_26") (pintype "bidirectional"))
      (node (ref "LED40") (pin "4") (pinfunction "RED_4") (pintype "bidirectional"))
    )
    (net (code "309") (name "/N$LEDR41_IC3_PIN52") (class "Default")
      (node (ref "IC3") (pin "52") (pinfunction "OUTR8_52") (pintype "bidirectional"))
      (node (ref "LED41") (pin "4") (pinfunction "RED_4") (pintype "bidirectional"))
    )
    (net (code "310") (name "/N$LEDR42_IC3_PIN46") (class "Default")
      (node (ref "IC3") (pin "46") (pinfunction "OUTR9_46") (pintype "bidirectional"))
      (node (ref "LED42") (pin "4") (pinfunction "RED_4") (pintype "bidirectional"))
    )
    (net (code "311") (name "/N$LEDR43_IC3_PIN40") (class "Default")
      (node (ref "IC3") (pin "40") (pinfunction "OUTR14_40") (pintype "bidirectional"))
      (node (ref "LED43") (pin "4") (pinfunction "RED_4") (pintype "bidirectional"))
    )
    (net (code "312") (name "/N$LEDR44_IC3_PIN34") (class "Default")
      (node (ref "IC3") (pin "34") (pinfunction "OUTR15_34") (pintype "bidirectional"))
      (node (ref "LED44") (pin "4") (pinfunction "RED_4") (pintype "bidirectional"))
    )
    (net (code "313") (name "/N$LEDR45_IC3_PIN49") (class "Default")
      (node (ref "IC3") (pin "49") (pinfunction "OUTR12_49") (pintype "bidirectional"))
      (node (ref "LED45") (pin "4") (pinfunction "RED_4") (pintype "bidirectional"))
    )
    (net (code "314") (name "/N$LEDR46_IC3_PIN43") (class "Default")
      (node (ref "IC3") (pin "43") (pinfunction "OUTR13_43") (pintype "bidirectional"))
      (node (ref "LED46") (pin "4") (pinfunction "RED_4") (pintype "bidirectional"))
    )
    (net (code "315") (name "/N$LEDR47_IC3_PIN37") (class "Default")
      (node (ref "IC3") (pin "37") (pinfunction "OUTR10_37") (pintype "bidirectional"))
      (node (ref "LED47") (pin "4") (pinfunction "RED_4") (pintype "bidirectional"))
    )
    (net (code "316") (name "/N$LEDR48_IC3_PIN31") (class "Default")
      (node (ref "IC3") (pin "31") (pinfunction "OUTR11_31") (pintype "bidirectional"))
      (node (ref "LED48") (pin "4") (pinfunction "RED_4") (pintype "bidirectional"))
    )
    (net (code "317") (name "/N$LEDR49_IC4_PIN5") (class "Default")
      (node (ref "IC4") (pin "5") (pinfunction "OUTR4_5") (pintype "bidirectional"))
      (node (ref "LED49") (pin "4") (pinfunction "RED_4") (pintype "bidirectional"))
    )
    (net (code "318") (name "/N$LEDR50_IC4_PIN11") (class "Default")
      (node (ref "IC4") (pin "11") (pinfunction "OUTR5_11") (pintype "bidirectional"))
      (node (ref "LED50") (pin "4") (pinfunction "RED_4") (pintype "bidirectional"))
    )
    (net (code "319") (name "/N$LEDR51_IC4_PIN17") (class "Default")
      (node (ref "IC4") (pin "17") (pinfunction "OUTR2_17") (pintype "bidirectional"))
      (node (ref "LED51") (pin "4") (pinfunction "RED_4") (pintype "bidirectional"))
    )
    (net (code "320") (name "/N$LEDR52_IC4_PIN23") (class "Default")
      (node (ref "IC4") (pin "23") (pinfunction "OUTR3_23") (pintype "bidirectional"))
      (node (ref "LED52") (pin "4") (pinfunction "RED_4") (pintype "bidirectional"))
    )
    (net (code "321") (name "/N$LEDR53_IC4_PIN8") (class "Default")
      (node (ref "IC4") (pin "8") (pinfunction "OUTR0_8") (pintype "bidirectional"))
      (node (ref "LED53") (pin "4") (pinfunction "RED_4") (pintype "bidirectional"))
    )
    (net (code "322") (name "/N$LEDR54_IC4_PIN14") (class "Default")
      (node (ref "IC4") (pin "14") (pinfunction "OUTR1_14") (pintype "bidirectional"))
      (node (ref "LED54") (pin "4") (pinfunction "RED_4") (pintype "bidirectional"))
    )
    (net (code "323") (name "/N$LEDR55_IC4_PIN20") (class "Default")
      (node (ref "IC4") (pin "20") (pinfunction "OUTR6_20") (pintype "bidirectional"))
      (node (ref "LED55") (pin "4") (pinfunction "RED_4") (pintype "bidirectional"))
    )
    (net (code "324") (name "/N$LEDR56_IC4_PIN26") (class "Default")
      (node (ref "IC4") (pin "26") (pinfunction "OUTR7_26") (pintype "bidirectional"))
      (node (ref "LED56") (pin "4") (pinfunction "RED_4") (pintype "bidirectional"))
    )
    (net (code "325") (name "/N$LEDR57_IC4_PIN52") (class "Default")
      (node (ref "IC4") (pin "52") (pinfunction "OUTR8_52") (pintype "bidirectional"))
      (node (ref "LED57") (pin "4") (pinfunction "RED_4") (pintype "bidirectional"))
    )
    (net (code "326") (name "/N$LEDR58_IC4_PIN46") (class "Default")
      (node (ref "IC4") (pin "46") (pinfunction "OUTR9_46") (pintype "bidirectional"))
      (node (ref "LED58") (pin "4") (pinfunction "RED_4") (pintype "bidirectional"))
    )
    (net (code "327") (name "/N$LEDR59_IC4_PIN40") (class "Default")
      (node (ref "IC4") (pin "40") (pinfunction "OUTR14_40") (pintype "bidirectional"))
      (node (ref "LED59") (pin "4") (pinfunction "RED_4") (pintype "bidirectional"))
    )
    (net (code "328") (name "/N$LEDR60_IC4_PIN34") (class "Default")
      (node (ref "IC4") (pin "34") (pinfunction "OUTR15_34") (pintype "bidirectional"))
      (node (ref "LED60") (pin "4") (pinfunction "RED_4") (pintype "bidirectional"))
    )
    (net (code "329") (name "/N$LEDR61_IC4_PIN49") (class "Default")
      (node (ref "IC4") (pin "49") (pinfunction "OUTR12_49") (pintype "bidirectional"))
      (node (ref "LED61") (pin "4") (pinfunction "RED_4") (pintype "bidirectional"))
    )
    (net (code "330") (name "/N$LEDR62_IC4_PIN43") (class "Default")
      (node (ref "IC4") (pin "43") (pinfunction "OUTR13_43") (pintype "bidirectional"))
      (node (ref "LED62") (pin "4") (pinfunction "RED_4") (pintype "bidirectional"))
    )
    (net (code "331") (name "/N$LEDR63_IC4_PIN37") (class "Default")
      (node (ref "IC4") (pin "37") (pinfunction "OUTR10_37") (pintype "bidirectional"))
      (node (ref "LED63") (pin "4") (pinfunction "RED_4") (pintype "bidirectional"))
    )
    (net (code "332") (name "/N$LEDR64_IC4_PIN31") (class "Default")
      (node (ref "IC4") (pin "31") (pinfunction "OUTR11_31") (pintype "bidirectional"))
      (node (ref "LED64") (pin "4") (pinfunction "RED_4") (pintype "bidirectional"))
    )
    (net (code "333") (name "/N$LEDR65_IC5_PIN5") (class "Default")
      (node (ref "IC5") (pin "5") (pinfunction "OUTR4_5") (pintype "bidirectional"))
      (node (ref "LED65") (pin "4") (pinfunction "RED_4") (pintype "bidirectional"))
    )
    (net (code "334") (name "/N$LEDR66_IC5_PIN11") (class "Default")
      (node (ref "IC5") (pin "11") (pinfunction "OUTR5_11") (pintype "bidirectional"))
      (node (ref "LED66") (pin "4") (pinfunction "RED_4") (pintype "bidirectional"))
    )
    (net (code "335") (name "/N$LEDR67_IC5_PIN17") (class "Default")
      (node (ref "IC5") (pin "17") (pinfunction "OUTR2_17") (pintype "bidirectional"))
      (node (ref "LED67") (pin "4") (pinfunction "RED_4") (pintype "bidirectional"))
    )
    (net (code "336") (name "/N$LEDR68_IC5_PIN23") (class "Default")
      (node (ref "IC5") (pin "23") (pinfunction "OUTR3_23") (pintype "bidirectional"))
      (node (ref "LED68") (pin "4") (pinfunction "RED_4") (pintype "bidirectional"))
    )
    (net (code "337") (name "/N$LEDR69_IC5_PIN8") (class "Default")
      (node (ref "IC5") (pin "8") (pinfunction "OUTR0_8") (pintype "bidirectional"))
      (node (ref "LED69") (pin "4") (pinfunction "RED_4") (pintype "bidirectional"))
    )
    (net (code "338") (name "/N$LEDR70_IC5_PIN14") (class "Default")
      (node (ref "IC5") (pin "14") (pinfunction "OUTR1_14") (pintype "bidirectional"))
      (node (ref "LED70") (pin "4") (pinfunction "RED_4") (pintype "bidirectional"))
    )
    (net (code "339") (name "/N$LEDR71_IC5_PIN20") (class "Default")
      (node (ref "IC5") (pin "20") (pinfunction "OUTR6_20") (pintype "bidirectional"))
      (node (ref "LED71") (pin "4") (pinfunction "RED_4") (pintype "bidirectional"))
    )
    (net (code "340") (name "/N$LEDR72_IC5_PIN26") (class "Default")
      (node (ref "IC5") (pin "26") (pinfunction "OUTR7_26") (pintype "bidirectional"))
      (node (ref "LED72") (pin "4") (pinfunction "RED_4") (pintype "bidirectional"))
    )
    (net (code "341") (name "/N$LEDR73_IC5_PIN52") (class "Default")
      (node (ref "IC5") (pin "52") (pinfunction "OUTR8_52") (pintype "bidirectional"))
      (node (ref "LED73") (pin "4") (pinfunction "RED_4") (pintype "bidirectional"))
    )
    (net (code "342") (name "/N$LEDR74_IC5_PIN46") (class "Default")
      (node (ref "IC5") (pin "46") (pinfunction "OUTR9_46") (pintype "bidirectional"))
      (node (ref "LED74") (pin "4") (pinfunction "RED_4") (pintype "bidirectional"))
    )
    (net (code "343") (name "/N$LEDR75_IC5_PIN40") (class "Default")
      (node (ref "IC5") (pin "40") (pinfunction "OUTR14_40") (pintype "bidirectional"))
      (node (ref "LED75") (pin "4") (pinfunction "RED_4") (pintype "bidirectional"))
    )
    (net (code "344") (name "/N$LEDR76_IC5_PIN34") (class "Default")
      (node (ref "IC5") (pin "34") (pinfunction "OUTR15_34") (pintype "bidirectional"))
      (node (ref "LED76") (pin "4") (pinfunction "RED_4") (pintype "bidirectional"))
    )
    (net (code "345") (name "/N$LEDR77_IC5_PIN49") (class "Default")
      (node (ref "IC5") (pin "49") (pinfunction "OUTR12_49") (pintype "bidirectional"))
      (node (ref "LED77") (pin "4") (pinfunction "RED_4") (pintype "bidirectional"))
    )
    (net (code "346") (name "/N$LEDR78_IC5_PIN43") (class "Default")
      (node (ref "IC5") (pin "43") (pinfunction "OUTR13_43") (pintype "bidirectional"))
      (node (ref "LED78") (pin "4") (pinfunction "RED_4") (pintype "bidirectional"))
    )
    (net (code "347") (name "/N$LEDR79_IC5_PIN37") (class "Default")
      (node (ref "IC5") (pin "37") (pinfunction "OUTR10_37") (pintype "bidirectional"))
      (node (ref "LED79") (pin "4") (pinfunction "RED_4") (pintype "bidirectional"))
    )
    (net (code "348") (name "/N$LEDR80_IC5_PIN31") (class "Default")
      (node (ref "IC5") (pin "31") (pinfunction "OUTR11_31") (pintype "bidirectional"))
      (node (ref "LED80") (pin "4") (pinfunction "RED_4") (pintype "bidirectional"))
    )
    (net (code "349") (name "/N$LEDR81_IC6_PIN5") (class "Default")
      (node (ref "IC6") (pin "5") (pinfunction "OUTR4_5") (pintype "bidirectional"))
      (node (ref "LED81") (pin "4") (pinfunction "RED_4") (pintype "bidirectional"))
    )
    (net (code "350") (name "/N$LEDR82_IC6_PIN11") (class "Default")
      (node (ref "IC6") (pin "11") (pinfunction "OUTR5_11") (pintype "bidirectional"))
      (node (ref "LED82") (pin "4") (pinfunction "RED_4") (pintype "bidirectional"))
    )
    (net (code "351") (name "/N$LEDR83_IC6_PIN17") (class "Default")
      (node (ref "IC6") (pin "17") (pinfunction "OUTR2_17") (pintype "bidirectional"))
      (node (ref "LED83") (pin "4") (pinfunction "RED_4") (pintype "bidirectional"))
    )
    (net (code "352") (name "/N$LEDR84_IC6_PIN23") (class "Default")
      (node (ref "IC6") (pin "23") (pinfunction "OUTR3_23") (pintype "bidirectional"))
      (node (ref "LED84") (pin "4") (pinfunction "RED_4") (pintype "bidirectional"))
    )
    (net (code "353") (name "/N$LEDR85_IC6_PIN8") (class "Default")
      (node (ref "IC6") (pin "8") (pinfunction "OUTR0_8") (pintype "bidirectional"))
      (node (ref "LED85") (pin "4") (pinfunction "RED_4") (pintype "bidirectional"))
    )
    (net (code "354") (name "/N$LEDR86_IC6_PIN14") (class "Default")
      (node (ref "IC6") (pin "14") (pinfunction "OUTR1_14") (pintype "bidirectional"))
      (node (ref "LED86") (pin "4") (pinfunction "RED_4") (pintype "bidirectional"))
    )
    (net (code "355") (name "/N$LEDR87_IC6_PIN20") (class "Default")
      (node (ref "IC6") (pin "20") (pinfunction "OUTR6_20") (pintype "bidirectional"))
      (node (ref "LED87") (pin "4") (pinfunction "RED_4") (pintype "bidirectional"))
    )
    (net (code "356") (name "/N$LEDR88_IC6_PIN26") (class "Default")
      (node (ref "IC6") (pin "26") (pinfunction "OUTR7_26") (pintype "bidirectional"))
      (node (ref "LED88") (pin "4") (pinfunction "RED_4") (pintype "bidirectional"))
    )
    (net (code "357") (name "/N$LEDR89_IC6_PIN52") (class "Default")
      (node (ref "IC6") (pin "52") (pinfunction "OUTR8_52") (pintype "bidirectional"))
      (node (ref "LED89") (pin "4") (pinfunction "RED_4") (pintype "bidirectional"))
    )
    (net (code "358") (name "/N$LEDR90_IC6_PIN46") (class "Default")
      (node (ref "IC6") (pin "46") (pinfunction "OUTR9_46") (pintype "bidirectional"))
      (node (ref "LED90") (pin "4") (pinfunction "RED_4") (pintype "bidirectional"))
    )
    (net (code "359") (name "/N$LEDR91_IC6_PIN40") (class "Default")
      (node (ref "IC6") (pin "40") (pinfunction "OUTR14_40") (pintype "bidirectional"))
      (node (ref "LED91") (pin "4") (pinfunction "RED_4") (pintype "bidirectional"))
    )
    (net (code "360") (name "/N$LEDR92_IC6_PIN34") (class "Default")
      (node (ref "IC6") (pin "34") (pinfunction "OUTR15_34") (pintype "bidirectional"))
      (node (ref "LED92") (pin "4") (pinfunction "RED_4") (pintype "bidirectional"))
    )
    (net (code "361") (name "/N$LEDR93_IC6_PIN49") (class "Default")
      (node (ref "IC6") (pin "49") (pinfunction "OUTR12_49") (pintype "bidirectional"))
      (node (ref "LED93") (pin "4") (pinfunction "RED_4") (pintype "bidirectional"))
    )
    (net (code "362") (name "/N$LEDR94_IC6_PIN43") (class "Default")
      (node (ref "IC6") (pin "43") (pinfunction "OUTR13_43") (pintype "bidirectional"))
      (node (ref "LED94") (pin "4") (pinfunction "RED_4") (pintype "bidirectional"))
    )
    (net (code "363") (name "/N$LEDR95_IC6_PIN37") (class "Default")
      (node (ref "IC6") (pin "37") (pinfunction "OUTR10_37") (pintype "bidirectional"))
      (node (ref "LED95") (pin "4") (pinfunction "RED_4") (pintype "bidirectional"))
    )
    (net (code "364") (name "/N$LEDR96_IC6_PIN31") (class "Default")
      (node (ref "IC6") (pin "31") (pinfunction "OUTR11_31") (pintype "bidirectional"))
      (node (ref "LED96") (pin "4") (pinfunction "RED_4") (pintype "bidirectional"))
    )
    (net (code "365") (name "/N$LEDR97_IC7_PIN5") (class "Default")
      (node (ref "IC7") (pin "5") (pinfunction "OUTR4_5") (pintype "bidirectional"))
      (node (ref "LED97") (pin "4") (pinfunction "RED_4") (pintype "bidirectional"))
    )
    (net (code "366") (name "/N$LEDR98_IC7_PIN11") (class "Default")
      (node (ref "IC7") (pin "11") (pinfunction "OUTR5_11") (pintype "bidirectional"))
      (node (ref "LED98") (pin "4") (pinfunction "RED_4") (pintype "bidirectional"))
    )
    (net (code "367") (name "/N$LEDR99_IC7_PIN17") (class "Default")
      (node (ref "IC7") (pin "17") (pinfunction "OUTR2_17") (pintype "bidirectional"))
      (node (ref "LED99") (pin "4") (pinfunction "RED_4") (pintype "bidirectional"))
    )
    (net (code "368") (name "/N$LEDR100_IC7_PIN23") (class "Default")
      (node (ref "IC7") (pin "23") (pinfunction "OUTR3_23") (pintype "bidirectional"))
      (node (ref "LED100") (pin "4") (pinfunction "RED_4") (pintype "bidirectional"))
    )
    (net (code "369") (name "/N$LEDR101_IC7_PIN8") (class "Default")
      (node (ref "IC7") (pin "8") (pinfunction "OUTR0_8") (pintype "bidirectional"))
      (node (ref "LED101") (pin "4") (pinfunction "RED_4") (pintype "bidirectional"))
    )
    (net (code "370") (name "/N$LEDR102_IC7_PIN14") (class "Default")
      (node (ref "IC7") (pin "14") (pinfunction "OUTR1_14") (pintype "bidirectional"))
      (node (ref "LED102") (pin "4") (pinfunction "RED_4") (pintype "bidirectional"))
    )
    (net (code "371") (name "/N$LEDR103_IC7_PIN20") (class "Default")
      (node (ref "IC7") (pin "20") (pinfunction "OUTR6_20") (pintype "bidirectional"))
      (node (ref "LED103") (pin "4") (pinfunction "RED_4") (pintype "bidirectional"))
    )
    (net (code "372") (name "/N$LEDR104_IC7_PIN26") (class "Default")
      (node (ref "IC7") (pin "26") (pinfunction "OUTR7_26") (pintype "bidirectional"))
      (node (ref "LED104") (pin "4") (pinfunction "RED_4") (pintype "bidirectional"))
    )
    (net (code "373") (name "/N$LEDR105_IC7_PIN52") (class "Default")
      (node (ref "IC7") (pin "52") (pinfunction "OUTR8_52") (pintype "bidirectional"))
      (node (ref "LED105") (pin "4") (pinfunction "RED_4") (pintype "bidirectional"))
    )
    (net (code "374") (name "/N$LEDR106_IC7_PIN46") (class "Default")
      (node (ref "IC7") (pin "46") (pinfunction "OUTR9_46") (pintype "bidirectional"))
      (node (ref "LED106") (pin "4") (pinfunction "RED_4") (pintype "bidirectional"))
    )
    (net (code "375") (name "/N$LEDR107_IC7_PIN40") (class "Default")
      (node (ref "IC7") (pin "40") (pinfunction "OUTR14_40") (pintype "bidirectional"))
      (node (ref "LED107") (pin "4") (pinfunction "RED_4") (pintype "bidirectional"))
    )
    (net (code "376") (name "/N$LEDR108_IC7_PIN34") (class "Default")
      (node (ref "IC7") (pin "34") (pinfunction "OUTR15_34") (pintype "bidirectional"))
      (node (ref "LED108") (pin "4") (pinfunction "RED_4") (pintype "bidirectional"))
    )
    (net (code "377") (name "/N$LEDR109_IC7_PIN49") (class "Default")
      (node (ref "IC7") (pin "49") (pinfunction "OUTR12_49") (pintype "bidirectional"))
      (node (ref "LED109") (pin "4") (pinfunction "RED_4") (pintype "bidirectional"))
    )
    (net (code "378") (name "/N$LEDR110_IC7_PIN43") (class "Default")
      (node (ref "IC7") (pin "43") (pinfunction "OUTR13_43") (pintype "bidirectional"))
      (node (ref "LED110") (pin "4") (pinfunction "RED_4") (pintype "bidirectional"))
    )
    (net (code "379") (name "/N$LEDR111_IC7_PIN37") (class "Default")
      (node (ref "IC7") (pin "37") (pinfunction "OUTR10_37") (pintype "bidirectional"))
      (node (ref "LED111") (pin "4") (pinfunction "RED_4") (pintype "bidirectional"))
    )
    (net (code "380") (name "/N$LEDR112_IC7_PIN31") (class "Default")
      (node (ref "IC7") (pin "31") (pinfunction "OUTR11_31") (pintype "bidirectional"))
      (node (ref "LED112") (pin "4") (pinfunction "RED_4") (pintype "bidirectional"))
    )
    (net (code "381") (name "/N$LEDR113_IC8_PIN5") (class "Default")
      (node (ref "IC8") (pin "5") (pinfunction "OUTR4_5") (pintype "bidirectional"))
      (node (ref "LED113") (pin "4") (pinfunction "RED_4") (pintype "bidirectional"))
    )
    (net (code "382") (name "/N$LEDR114_IC8_PIN11") (class "Default")
      (node (ref "IC8") (pin "11") (pinfunction "OUTR5_11") (pintype "bidirectional"))
      (node (ref "LED114") (pin "4") (pinfunction "RED_4") (pintype "bidirectional"))
    )
    (net (code "383") (name "/N$LEDR115_IC8_PIN17") (class "Default")
      (node (ref "IC8") (pin "17") (pinfunction "OUTR2_17") (pintype "bidirectional"))
      (node (ref "LED115") (pin "4") (pinfunction "RED_4") (pintype "bidirectional"))
    )
    (net (code "384") (name "/N$LEDR116_IC8_PIN23") (class "Default")
      (node (ref "IC8") (pin "23") (pinfunction "OUTR3_23") (pintype "bidirectional"))
      (node (ref "LED116") (pin "4") (pinfunction "RED_4") (pintype "bidirectional"))
    )
    (net (code "385") (name "/N$LEDR117_IC8_PIN8") (class "Default")
      (node (ref "IC8") (pin "8") (pinfunction "OUTR0_8") (pintype "bidirectional"))
      (node (ref "LED117") (pin "4") (pinfunction "RED_4") (pintype "bidirectional"))
    )
    (net (code "386") (name "/N$LEDR118_IC8_PIN14") (class "Default")
      (node (ref "IC8") (pin "14") (pinfunction "OUTR1_14") (pintype "bidirectional"))
      (node (ref "LED118") (pin "4") (pinfunction "RED_4") (pintype "bidirectional"))
    )
    (net (code "387") (name "/N$LEDR119_IC8_PIN20") (class "Default")
      (node (ref "IC8") (pin "20") (pinfunction "OUTR6_20") (pintype "bidirectional"))
      (node (ref "LED119") (pin "4") (pinfunction "RED_4") (pintype "bidirectional"))
    )
    (net (code "388") (name "/N$LEDR120_IC8_PIN26") (class "Default")
      (node (ref "IC8") (pin "26") (pinfunction "OUTR7_26") (pintype "bidirectional"))
      (node (ref "LED120") (pin "4") (pinfunction "RED_4") (pintype "bidirectional"))
    )
    (net (code "389") (name "/SCLK") (class "Default")
      (node (ref "IC1") (pin "2") (pinfunction "SCLK_2") (pintype "bidirectional"))
      (node (ref "IC2") (pin "2") (pinfunction "SCLK_2") (pintype "bidirectional"))
      (node (ref "IC3") (pin "2") (pinfunction "SCLK_2") (pintype "bidirectional"))
      (node (ref "IC4") (pin "2") (pinfunction "SCLK_2") (pintype "bidirectional"))
      (node (ref "IC5") (pin "2") (pinfunction "SCLK_2") (pintype "bidirectional"))
      (node (ref "IC6") (pin "2") (pinfunction "SCLK_2") (pintype "bidirectional"))
      (node (ref "IC7") (pin "2") (pinfunction "SCLK_2") (pintype "bidirectional"))
      (node (ref "IC8") (pin "2") (pinfunction "SCLK_2") (pintype "bidirectional"))
      (node (ref "SV1") (pin "7") (pinfunction "7_7") (pintype "passive"))
    )
    (net (code "390") (name "/SIN_1,2") (class "Default")
      (node (ref "IC2") (pin "1") (pinfunction "SIN_1") (pintype "bidirectional"))
      (node (ref "SV1") (pin "2") (pinfunction "2_2") (pintype "passive"))
    )
    (net (code "391") (name "/SIN_3,4") (class "Default")
      (node (ref "IC4") (pin "1") (pinfunction "SIN_1") (pintype "bidirectional"))
      (node (ref "SV1") (pin "3") (pinfunction "3_3") (pintype "passive"))
    )
    (net (code "392") (name "/SIN_5,6") (class "Default")
      (node (ref "IC6") (pin "1") (pinfunction "SIN_1") (pintype "bidirectional"))
      (node (ref "SV1") (pin "4") (pinfunction "4_4") (pintype "passive"))
    )
    (net (code "393") (name "/SIN_7,8") (class "Default")
      (node (ref "IC8") (pin "1") (pinfunction "SIN_1") (pintype "bidirectional"))
      (node (ref "SV1") (pin "5") (pinfunction "5_5") (pintype "passive"))
    )
    (net (code "394") (name "/SOUT1") (class "Default")
      (node (ref "IC1") (pin "28") (pinfunction "SOUT_28") (pintype "bidirectional"))
    )
    (net (code "395") (name "/SOUT2") (class "Default")
      (node (ref "IC1") (pin "1") (pinfunction "SIN_1") (pintype "bidirectional"))
      (node (ref "IC2") (pin "28") (pinfunction "SOUT_28") (pintype "bidirectional"))
    )
    (net (code "396") (name "/SOUT3") (class "Default")
      (node (ref "IC3") (pin "28") (pinfunction "SOUT_28") (pintype "bidirectional"))
    )
    (net (code "397") (name "/SOUT4") (class "Default")
      (node (ref "IC3") (pin "1") (pinfunction "SIN_1") (pintype "bidirectional"))
      (node (ref "IC4") (pin "28") (pinfunction "SOUT_28") (pintype "bidirectional"))
    )
    (net (code "398") (name "/SOUT5") (class "Default")
      (node (ref "IC5") (pin "28") (pinfunction "SOUT_28") (pintype "bidirectional"))
    )
    (net (code "399") (name "/SOUT6") (class "Default")
      (node (ref "IC5") (pin "1") (pinfunction "SIN_1") (pintype "bidirectional"))
      (node (ref "IC6") (pin "28") (pinfunction "SOUT_28") (pintype "bidirectional"))
    )
    (net (code "400") (name "/SOUT7") (class "Default")
      (node (ref "IC7") (pin "28") (pinfunction "SOUT_28") (pintype "bidirectional"))
    )
    (net (code "401") (name "/SOUT8") (class "Default")
      (node (ref "IC7") (pin "1") (pinfunction "SIN_1") (pintype "bidirectional"))
      (node (ref "IC8") (pin "28") (pinfunction "SOUT_28") (pintype "bidirectional"))
    )
    (net (code "402") (name "unconnected-(SV1-Pad1)") (class "Default")
      (node (ref "SV1") (pin "1") (pinfunction "1_1") (pintype "passive"))
    )
  )
)
